# trig3_board_trigger_waveshare_lvds.net
KiCad netlist of a schematic drawn in EAGLE
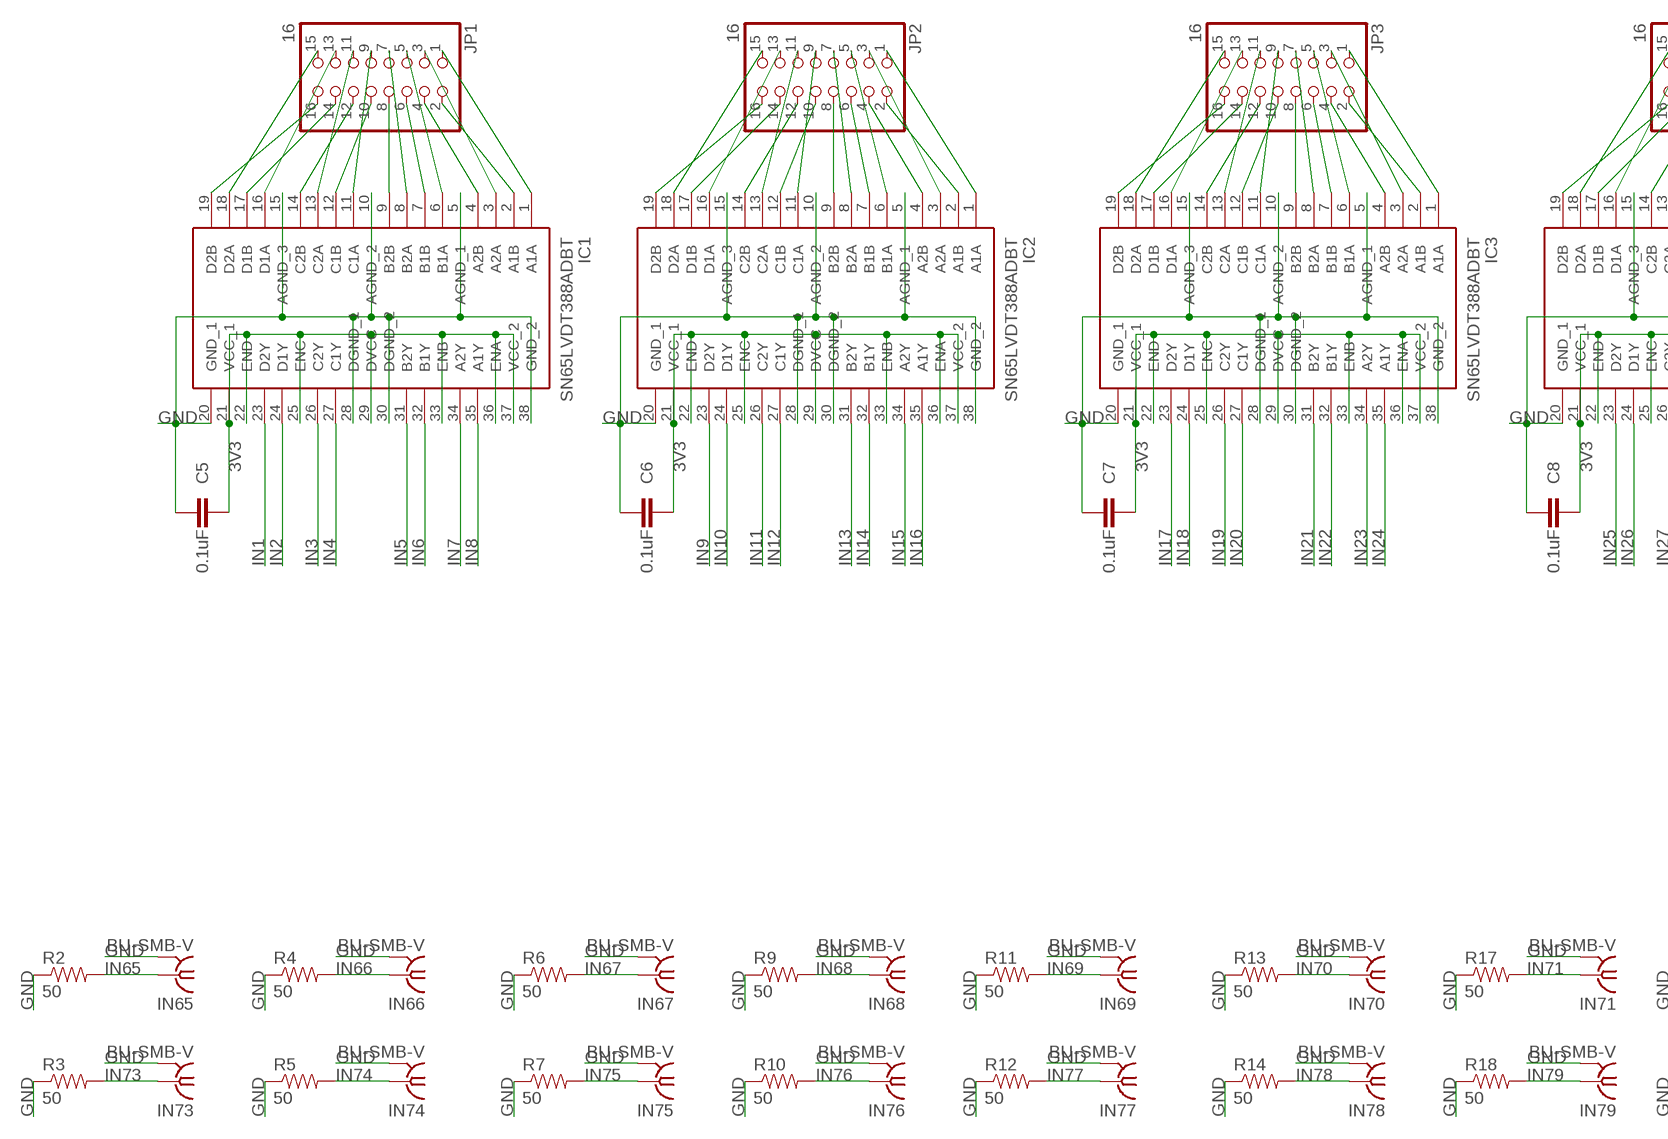
[diagram p0: schematic, sheet 1, part 1 of 3]
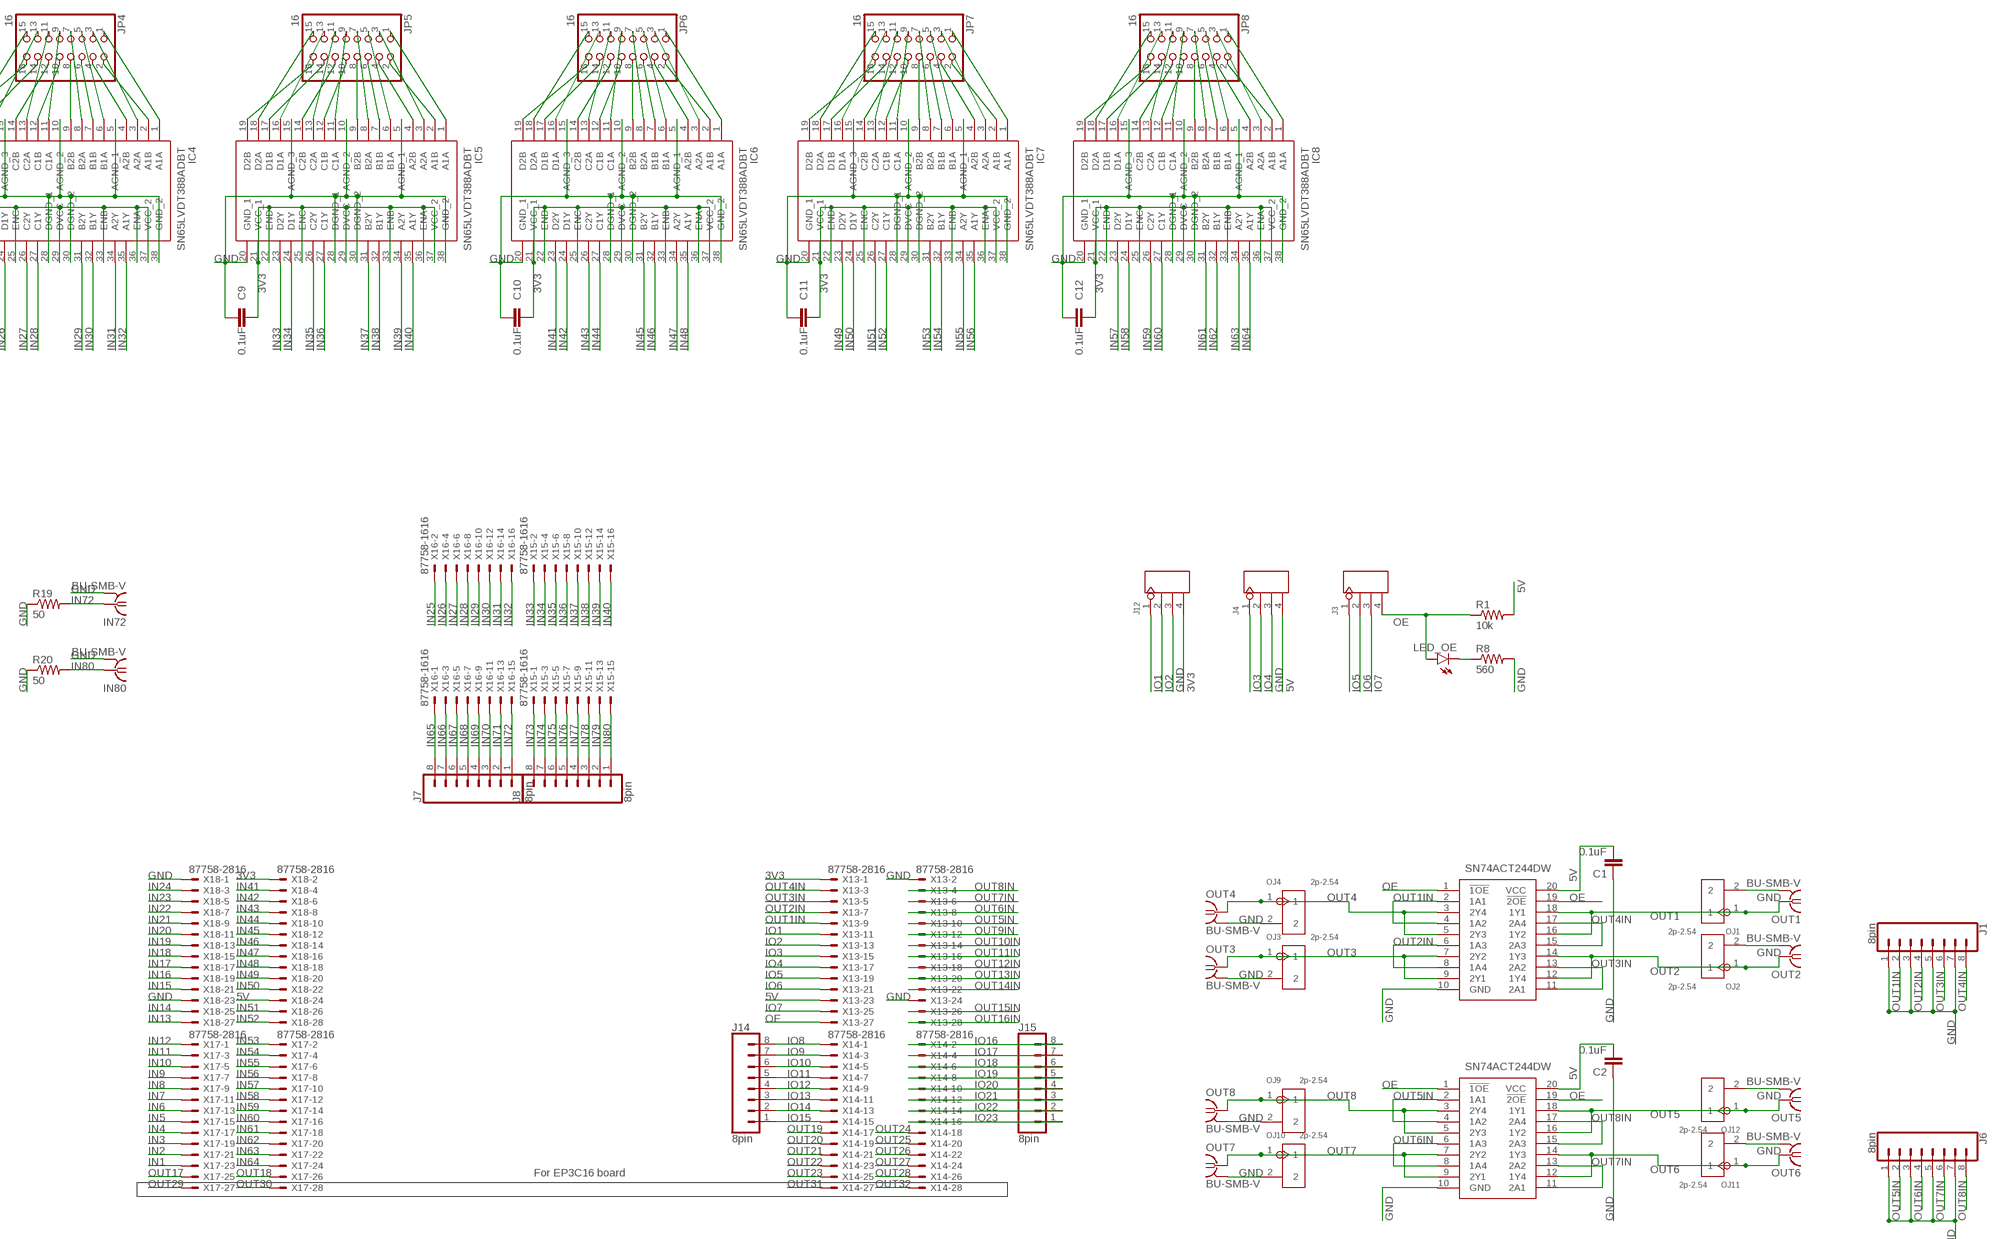
[diagram p1: schematic, sheet 1, part 2 of 3]
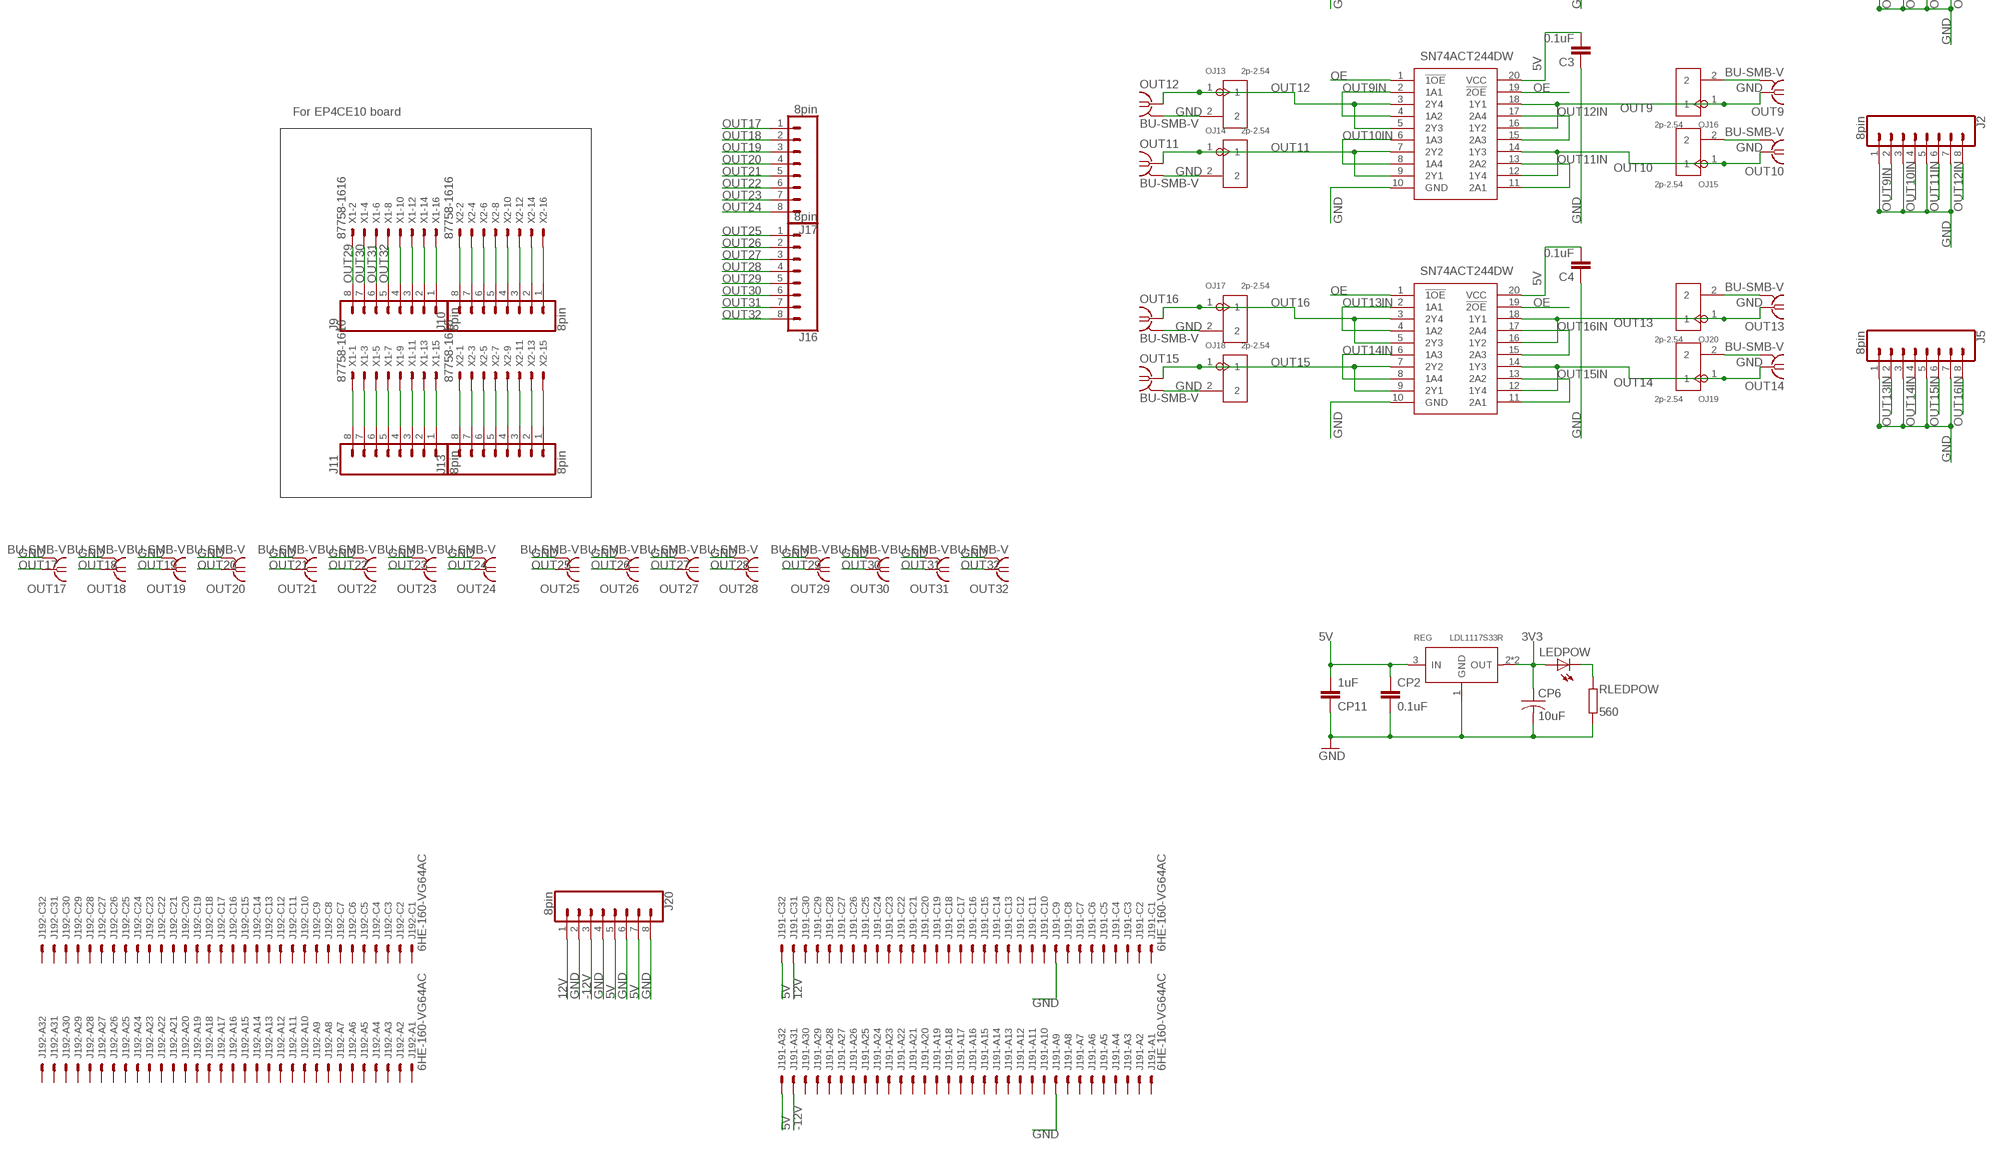
[diagram p2: schematic, sheet 1, part 3 of 3]

(export (version "E")
  (design (tool "Eeschema 10.0.6"))
  (components
    (comp (ref "C1")
      (value "0.1uF")
      (footprint "eagle-import:0805")
      (libsource (lib "eagle-import") (part "CAP0805"))
    )
    (comp (ref "C2")
      (value "0.1uF")
      (footprint "eagle-import:0805")
      (libsource (lib "eagle-import") (part "CAP0805"))
    )
    (comp (ref "C3")
      (value "0.1uF")
      (footprint "eagle-import:0805")
      (libsource (lib "eagle-import") (part "CAP0805"))
    )
    (comp (ref "C4")
      (value "0.1uF")
      (footprint "eagle-import:0805")
      (libsource (lib "eagle-import") (part "CAP0805"))
    )
    (comp (ref "C5")
      (value "0.1uF")
      (footprint "eagle-import:0805")
      (libsource (lib "eagle-import") (part "CAP0805"))
    )
    (comp (ref "C6")
      (value "0.1uF")
      (footprint "eagle-import:0805")
      (libsource (lib "eagle-import") (part "CAP0805"))
    )
    (comp (ref "C7")
      (value "0.1uF")
      (footprint "eagle-import:0805")
      (libsource (lib "eagle-import") (part "CAP0805"))
    )
    (comp (ref "C8")
      (value "0.1uF")
      (footprint "eagle-import:0805")
      (libsource (lib "eagle-import") (part "CAP0805"))
    )
    (comp (ref "C9")
      (value "0.1uF")
      (footprint "eagle-import:0805")
      (libsource (lib "eagle-import") (part "CAP0805"))
    )
    (comp (ref "C10")
      (value "0.1uF")
      (footprint "eagle-import:0805")
      (libsource (lib "eagle-import") (part "CAP0805"))
    )
    (comp (ref "C11")
      (value "0.1uF")
      (footprint "eagle-import:0805")
      (libsource (lib "eagle-import") (part "CAP0805"))
    )
    (comp (ref "C12")
      (value "0.1uF")
      (footprint "eagle-import:0805")
      (libsource (lib "eagle-import") (part "CAP0805"))
    )
    (comp (ref "CP2")
      (value "0.1uF")
      (footprint "eagle-import:C0805K")
      (fields (field (name "MPN") "MF-CAP-0805-0.1uF"))
      (libsource (lib "eagle-import") (part "C-EUC0805K"))
    )
    (comp (ref "CP6")
      (value "10uF")
      (footprint "eagle-import:C1206")
      (fields (field (name "MPN") "MF-CAP-1206-10uF"))
      (libsource (lib "eagle-import") (part "C-USC1206"))
    )
    (comp (ref "CP11")
      (value "1uF")
      (footprint "eagle-import:C0805K")
      (fields (field (name "MPN") "MF-CAP-0805-1uF"))
      (libsource (lib "eagle-import") (part "C-EUC0805K"))
    )
    (comp (ref "IC1")
      (value "SN65LVDT388ADBT")
      (footprint "eagle-import:SOP50P640X120-38N")
      (fields (field (name "MOUSER_PART_NUMBER") "595-SN65LVDT388ADBT"))
      (libsource (lib "eagle-import") (part "SN65LVDT388ADBT"))
    )
    (comp (ref "IC2")
      (value "SN65LVDT388ADBT")
      (footprint "eagle-import:SOP50P640X120-38N")
      (fields (field (name "MOUSER_PART_NUMBER") "595-SN65LVDT388ADBT"))
      (libsource (lib "eagle-import") (part "SN65LVDT388ADBT"))
    )
    (comp (ref "IC3")
      (value "SN65LVDT388ADBT")
      (footprint "eagle-import:SOP50P640X120-38N")
      (fields (field (name "MOUSER_PART_NUMBER") "595-SN65LVDT388ADBT"))
      (libsource (lib "eagle-import") (part "SN65LVDT388ADBT"))
    )
    (comp (ref "IC4")
      (value "SN65LVDT388ADBT")
      (footprint "eagle-import:SOP50P640X120-38N")
      (fields (field (name "MOUSER_PART_NUMBER") "595-SN65LVDT388ADBT"))
      (libsource (lib "eagle-import") (part "SN65LVDT388ADBT"))
    )
    (comp (ref "IC5")
      (value "SN65LVDT388ADBT")
      (footprint "eagle-import:SOP50P640X120-38N")
      (fields (field (name "MOUSER_PART_NUMBER") "595-SN65LVDT388ADBT"))
      (libsource (lib "eagle-import") (part "SN65LVDT388ADBT"))
    )
    (comp (ref "IC6")
      (value "SN65LVDT388ADBT")
      (footprint "eagle-import:SOP50P640X120-38N")
      (fields (field (name "MOUSER_PART_NUMBER") "595-SN65LVDT388ADBT"))
      (libsource (lib "eagle-import") (part "SN65LVDT388ADBT"))
    )
    (comp (ref "IC7")
      (value "SN65LVDT388ADBT")
      (footprint "eagle-import:SOP50P640X120-38N")
      (fields (field (name "MOUSER_PART_NUMBER") "595-SN65LVDT388ADBT"))
      (libsource (lib "eagle-import") (part "SN65LVDT388ADBT"))
    )
    (comp (ref "IC8")
      (value "SN65LVDT388ADBT")
      (footprint "eagle-import:SOP50P640X120-38N")
      (fields (field (name "MOUSER_PART_NUMBER") "595-SN65LVDT388ADBT"))
      (libsource (lib "eagle-import") (part "SN65LVDT388ADBT"))
    )
    (comp (ref "IN65")
      (value "BU-SMB-V")
      (footprint "eagle-import:BU-SMB-V")
      (libsource (lib "eagle-import") (part "BU-SMB-V"))
    )
    (comp (ref "IN66")
      (value "BU-SMB-V")
      (footprint "eagle-import:BU-SMB-V")
      (libsource (lib "eagle-import") (part "BU-SMB-V"))
    )
    (comp (ref "IN67")
      (value "BU-SMB-V")
      (footprint "eagle-import:BU-SMB-V")
      (libsource (lib "eagle-import") (part "BU-SMB-V"))
    )
    (comp (ref "IN68")
      (value "BU-SMB-V")
      (footprint "eagle-import:BU-SMB-V")
      (libsource (lib "eagle-import") (part "BU-SMB-V"))
    )
    (comp (ref "IN69")
      (value "BU-SMB-V")
      (footprint "eagle-import:BU-SMB-V")
      (libsource (lib "eagle-import") (part "BU-SMB-V"))
    )
    (comp (ref "IN70")
      (value "BU-SMB-V")
      (footprint "eagle-import:BU-SMB-V")
      (libsource (lib "eagle-import") (part "BU-SMB-V"))
    )
    (comp (ref "IN71")
      (value "BU-SMB-V")
      (footprint "eagle-import:BU-SMB-V")
      (libsource (lib "eagle-import") (part "BU-SMB-V"))
    )
    (comp (ref "IN72")
      (value "BU-SMB-V")
      (footprint "eagle-import:BU-SMB-V")
      (libsource (lib "eagle-import") (part "BU-SMB-V"))
    )
    (comp (ref "IN73")
      (value "BU-SMB-V")
      (footprint "eagle-import:BU-SMB-V")
      (libsource (lib "eagle-import") (part "BU-SMB-V"))
    )
    (comp (ref "IN74")
      (value "BU-SMB-V")
      (footprint "eagle-import:BU-SMB-V")
      (libsource (lib "eagle-import") (part "BU-SMB-V"))
    )
    (comp (ref "IN75")
      (value "BU-SMB-V")
      (footprint "eagle-import:BU-SMB-V")
      (libsource (lib "eagle-import") (part "BU-SMB-V"))
    )
    (comp (ref "IN76")
      (value "BU-SMB-V")
      (footprint "eagle-import:BU-SMB-V")
      (libsource (lib "eagle-import") (part "BU-SMB-V"))
    )
    (comp (ref "IN77")
      (value "BU-SMB-V")
      (footprint "eagle-import:BU-SMB-V")
      (libsource (lib "eagle-import") (part "BU-SMB-V"))
    )
    (comp (ref "IN78")
      (value "BU-SMB-V")
      (footprint "eagle-import:BU-SMB-V")
      (libsource (lib "eagle-import") (part "BU-SMB-V"))
    )
    (comp (ref "IN79")
      (value "BU-SMB-V")
      (footprint "eagle-import:BU-SMB-V")
      (libsource (lib "eagle-import") (part "BU-SMB-V"))
    )
    (comp (ref "IN80")
      (value "BU-SMB-V")
      (footprint "eagle-import:BU-SMB-V")
      (libsource (lib "eagle-import") (part "BU-SMB-V"))
    )
    (comp (ref "J1")
      (value "8pin")
      (footprint "eagle-import:1X08")
      (libsource (lib "eagle-import") (part "CONN_08{dblquote}"))
    )
    (comp (ref "J2")
      (value "8pin")
      (footprint "eagle-import:1X08")
      (libsource (lib "eagle-import") (part "CONN_08{dblquote}"))
    )
    (comp (ref "J3")
      (value "4p-2.54")
      (footprint "eagle-import:H4-2.54")
      (fields (field (name "MPN") "F185-1104A1BSYA1"))
      (libsource (lib "eagle-import") (part "DIP-BLACK-FEMALE-HEADER-VERT(4P-2.54)"))
    )
    (comp (ref "J4")
      (value "4p-2.54")
      (footprint "eagle-import:H4-2.54")
      (fields (field (name "MPN") "F185-1104A1BSYA1"))
      (libsource (lib "eagle-import") (part "DIP-BLACK-FEMALE-HEADER-VERT(4P-2.54)"))
    )
    (comp (ref "J5")
      (value "8pin")
      (footprint "eagle-import:1X08")
      (libsource (lib "eagle-import") (part "CONN_08{dblquote}"))
    )
    (comp (ref "J6")
      (value "8pin")
      (footprint "eagle-import:1X08")
      (libsource (lib "eagle-import") (part "CONN_08{dblquote}"))
    )
    (comp (ref "J7")
      (value "8pin")
      (footprint "eagle-import:1X08")
      (libsource (lib "eagle-import") (part "CONN_08{dblquote}"))
    )
    (comp (ref "J8")
      (value "8pin")
      (footprint "eagle-import:1X08")
      (libsource (lib "eagle-import") (part "CONN_08{dblquote}"))
    )
    (comp (ref "J9")
      (value "8pin")
      (footprint "eagle-import:1X08")
      (libsource (lib "eagle-import") (part "CONN_08{dblquote}"))
    )
    (comp (ref "J10")
      (value "8pin")
      (footprint "eagle-import:1X08")
      (libsource (lib "eagle-import") (part "CONN_08{dblquote}"))
    )
    (comp (ref "J11")
      (value "8pin")
      (footprint "eagle-import:1X08")
      (libsource (lib "eagle-import") (part "CONN_08{dblquote}"))
    )
    (comp (ref "J12")
      (value "4p-2.54")
      (footprint "eagle-import:H4-2.54")
      (fields (field (name "MPN") "F185-1104A1BSYA1"))
      (libsource (lib "eagle-import") (part "DIP-BLACK-FEMALE-HEADER-VERT(4P-2.54)"))
    )
    (comp (ref "J13")
      (value "8pin")
      (footprint "eagle-import:1X08")
      (libsource (lib "eagle-import") (part "CONN_08{dblquote}"))
    )
    (comp (ref "J14")
      (value "8pin")
      (footprint "eagle-import:1X08")
      (libsource (lib "eagle-import") (part "CONN_08{dblquote}"))
    )
    (comp (ref "J15")
      (value "8pin")
      (footprint "eagle-import:1X08")
      (libsource (lib "eagle-import") (part "CONN_08{dblquote}"))
    )
    (comp (ref "J16")
      (value "8pin")
      (footprint "eagle-import:1X08")
      (libsource (lib "eagle-import") (part "CONN_08{dblquote}"))
    )
    (comp (ref "J17")
      (value "8pin")
      (footprint "eagle-import:1X08")
      (libsource (lib "eagle-import") (part "CONN_08{dblquote}"))
    )
    (comp (ref "J19")
      (value "6HE-160-VG64AC")
      (footprint "eagle-import:6HE_160-VG64AC")
      (libsource (lib "eagle-import") (part "6HE-?-VG64AC160"))
    )
    (comp (ref "J20")
      (value "8pin")
      (footprint "eagle-import:1X08")
      (libsource (lib "eagle-import") (part "CONN_08{dblquote}"))
    )
    (comp (ref "JP1")
      (value "16")
      (footprint "eagle-import:2X08_90")
      (libsource (lib "eagle-import") (part "PINHD-2X8/90"))
    )
    (comp (ref "JP2")
      (value "16")
      (footprint "eagle-import:2X08_90")
      (libsource (lib "eagle-import") (part "PINHD-2X8/90"))
    )
    (comp (ref "JP3")
      (value "16")
      (footprint "eagle-import:2X08_90")
      (libsource (lib "eagle-import") (part "PINHD-2X8/90"))
    )
    (comp (ref "JP4")
      (value "16")
      (footprint "eagle-import:2X08_90")
      (libsource (lib "eagle-import") (part "PINHD-2X8/90"))
    )
    (comp (ref "JP5")
      (value "16")
      (footprint "eagle-import:2X08_90")
      (libsource (lib "eagle-import") (part "PINHD-2X8/90"))
    )
    (comp (ref "JP6")
      (value "16")
      (footprint "eagle-import:2X08_90")
      (libsource (lib "eagle-import") (part "PINHD-2X8/90"))
    )
    (comp (ref "JP7")
      (value "16")
      (footprint "eagle-import:2X08_90")
      (libsource (lib "eagle-import") (part "PINHD-2X8/90"))
    )
    (comp (ref "JP8")
      (value "16")
      (footprint "eagle-import:2X08_90")
      (libsource (lib "eagle-import") (part "PINHD-2X8/90"))
    )
    (comp (ref "LEDPOW")
      (value "MF-LED-0805-RED")
      (footprint "eagle-import:SML0805")
      (libsource (lib "eagle-import") (part "LEDSML0805"))
    )
    (comp (ref "LED_OE")
      (value "OutputEn")
      (footprint "eagle-import:CHIP-LED0805")
      (libsource (lib "eagle-import") (part "led_259_LEDCHIP-LED0805"))
    )
    (comp (ref "OJ1")
      (value "2p-2.54")
      (footprint "eagle-import:H2-2.54")
      (fields (field (name "MPN") "P125-1102A0BS116A1"))
      (libsource (lib "eagle-import") (part "DIP-BLACK-MALE-HEADER-VERT(2P-2.54)"))
    )
    (comp (ref "OJ2")
      (value "2p-2.54")
      (footprint "eagle-import:H2-2.54")
      (fields (field (name "MPN") "P125-1102A0BS116A1"))
      (libsource (lib "eagle-import") (part "DIP-BLACK-MALE-HEADER-VERT(2P-2.54)"))
    )
    (comp (ref "OJ3")
      (value "2p-2.54")
      (footprint "eagle-import:H2-2.54")
      (fields (field (name "MPN") "P125-1102A0BS116A1"))
      (libsource (lib "eagle-import") (part "DIP-BLACK-MALE-HEADER-VERT(2P-2.54)"))
    )
    (comp (ref "OJ4")
      (value "2p-2.54")
      (footprint "eagle-import:H2-2.54")
      (fields (field (name "MPN") "P125-1102A0BS116A1"))
      (libsource (lib "eagle-import") (part "DIP-BLACK-MALE-HEADER-VERT(2P-2.54)"))
    )
    (comp (ref "OJ9")
      (value "2p-2.54")
      (footprint "eagle-import:H2-2.54")
      (fields (field (name "MPN") "P125-1102A0BS116A1"))
      (libsource (lib "eagle-import") (part "DIP-BLACK-MALE-HEADER-VERT(2P-2.54)"))
    )
    (comp (ref "OJ10")
      (value "2p-2.54")
      (footprint "eagle-import:H2-2.54")
      (fields (field (name "MPN") "P125-1102A0BS116A1"))
      (libsource (lib "eagle-import") (part "DIP-BLACK-MALE-HEADER-VERT(2P-2.54)"))
    )
    (comp (ref "OJ11")
      (value "2p-2.54")
      (footprint "eagle-import:H2-2.54")
      (fields (field (name "MPN") "P125-1102A0BS116A1"))
      (libsource (lib "eagle-import") (part "DIP-BLACK-MALE-HEADER-VERT(2P-2.54)"))
    )
    (comp (ref "OJ12")
      (value "2p-2.54")
      (footprint "eagle-import:H2-2.54")
      (fields (field (name "MPN") "P125-1102A0BS116A1"))
      (libsource (lib "eagle-import") (part "DIP-BLACK-MALE-HEADER-VERT(2P-2.54)"))
    )
    (comp (ref "OJ13")
      (value "2p-2.54")
      (footprint "eagle-import:H2-2.54")
      (fields (field (name "MPN") "P125-1102A0BS116A1"))
      (libsource (lib "eagle-import") (part "DIP-BLACK-MALE-HEADER-VERT(2P-2.54)"))
    )
    (comp (ref "OJ14")
      (value "2p-2.54")
      (footprint "eagle-import:H2-2.54")
      (fields (field (name "MPN") "P125-1102A0BS116A1"))
      (libsource (lib "eagle-import") (part "DIP-BLACK-MALE-HEADER-VERT(2P-2.54)"))
    )
    (comp (ref "OJ15")
      (value "2p-2.54")
      (footprint "eagle-import:H2-2.54")
      (fields (field (name "MPN") "P125-1102A0BS116A1"))
      (libsource (lib "eagle-import") (part "DIP-BLACK-MALE-HEADER-VERT(2P-2.54)"))
    )
    (comp (ref "OJ16")
      (value "2p-2.54")
      (footprint "eagle-import:H2-2.54")
      (fields (field (name "MPN") "P125-1102A0BS116A1"))
      (libsource (lib "eagle-import") (part "DIP-BLACK-MALE-HEADER-VERT(2P-2.54)"))
    )
    (comp (ref "OJ17")
      (value "2p-2.54")
      (footprint "eagle-import:H2-2.54")
      (fields (field (name "MPN") "P125-1102A0BS116A1"))
      (libsource (lib "eagle-import") (part "DIP-BLACK-MALE-HEADER-VERT(2P-2.54)"))
    )
    (comp (ref "OJ18")
      (value "2p-2.54")
      (footprint "eagle-import:H2-2.54")
      (fields (field (name "MPN") "P125-1102A0BS116A1"))
      (libsource (lib "eagle-import") (part "DIP-BLACK-MALE-HEADER-VERT(2P-2.54)"))
    )
    (comp (ref "OJ19")
      (value "2p-2.54")
      (footprint "eagle-import:H2-2.54")
      (fields (field (name "MPN") "P125-1102A0BS116A1"))
      (libsource (lib "eagle-import") (part "DIP-BLACK-MALE-HEADER-VERT(2P-2.54)"))
    )
    (comp (ref "OJ20")
      (value "2p-2.54")
      (footprint "eagle-import:H2-2.54")
      (fields (field (name "MPN") "P125-1102A0BS116A1"))
      (libsource (lib "eagle-import") (part "DIP-BLACK-MALE-HEADER-VERT(2P-2.54)"))
    )
    (comp (ref "OUT1")
      (value "BU-SMB-V")
      (footprint "eagle-import:BU-SMB-V")
      (libsource (lib "eagle-import") (part "BU-SMB-V"))
    )
    (comp (ref "OUT2")
      (value "BU-SMB-V")
      (footprint "eagle-import:BU-SMB-V")
      (libsource (lib "eagle-import") (part "BU-SMB-V"))
    )
    (comp (ref "OUT3")
      (value "BU-SMB-V")
      (footprint "eagle-import:BU-SMB-V")
      (libsource (lib "eagle-import") (part "BU-SMB-V"))
    )
    (comp (ref "OUT4")
      (value "BU-SMB-V")
      (footprint "eagle-import:BU-SMB-V")
      (libsource (lib "eagle-import") (part "BU-SMB-V"))
    )
    (comp (ref "OUT5")
      (value "BU-SMB-V")
      (footprint "eagle-import:BU-SMB-V")
      (libsource (lib "eagle-import") (part "BU-SMB-V"))
    )
    (comp (ref "OUT6")
      (value "BU-SMB-V")
      (footprint "eagle-import:BU-SMB-V")
      (libsource (lib "eagle-import") (part "BU-SMB-V"))
    )
    (comp (ref "OUT7")
      (value "BU-SMB-V")
      (footprint "eagle-import:BU-SMB-V")
      (libsource (lib "eagle-import") (part "BU-SMB-V"))
    )
    (comp (ref "OUT8")
      (value "BU-SMB-V")
      (footprint "eagle-import:BU-SMB-V")
      (libsource (lib "eagle-import") (part "BU-SMB-V"))
    )
    (comp (ref "OUT9")
      (value "BU-SMB-V")
      (footprint "eagle-import:BU-SMB-V")
      (libsource (lib "eagle-import") (part "BU-SMB-V"))
    )
    (comp (ref "OUT10")
      (value "BU-SMB-V")
      (footprint "eagle-import:BU-SMB-V")
      (libsource (lib "eagle-import") (part "BU-SMB-V"))
    )
    (comp (ref "OUT11")
      (value "BU-SMB-V")
      (footprint "eagle-import:BU-SMB-V")
      (libsource (lib "eagle-import") (part "BU-SMB-V"))
    )
    (comp (ref "OUT12")
      (value "BU-SMB-V")
      (footprint "eagle-import:BU-SMB-V")
      (libsource (lib "eagle-import") (part "BU-SMB-V"))
    )
    (comp (ref "OUT13")
      (value "BU-SMB-V")
      (footprint "eagle-import:BU-SMB-V")
      (libsource (lib "eagle-import") (part "BU-SMB-V"))
    )
    (comp (ref "OUT14")
      (value "BU-SMB-V")
      (footprint "eagle-import:BU-SMB-V")
      (libsource (lib "eagle-import") (part "BU-SMB-V"))
    )
    (comp (ref "OUT15")
      (value "BU-SMB-V")
      (footprint "eagle-import:BU-SMB-V")
      (libsource (lib "eagle-import") (part "BU-SMB-V"))
    )
    (comp (ref "OUT16")
      (value "BU-SMB-V")
      (footprint "eagle-import:BU-SMB-V")
      (libsource (lib "eagle-import") (part "BU-SMB-V"))
    )
    (comp (ref "OUT17")
      (value "BU-SMB-V")
      (footprint "eagle-import:BU-SMB-V")
      (libsource (lib "eagle-import") (part "BU-SMB-V"))
    )
    (comp (ref "OUT18")
      (value "BU-SMB-V")
      (footprint "eagle-import:BU-SMB-V")
      (libsource (lib "eagle-import") (part "BU-SMB-V"))
    )
    (comp (ref "OUT19")
      (value "BU-SMB-V")
      (footprint "eagle-import:BU-SMB-V")
      (libsource (lib "eagle-import") (part "BU-SMB-V"))
    )
    (comp (ref "OUT20")
      (value "BU-SMB-V")
      (footprint "eagle-import:BU-SMB-V")
      (libsource (lib "eagle-import") (part "BU-SMB-V"))
    )
    (comp (ref "OUT21")
      (value "BU-SMB-V")
      (footprint "eagle-import:BU-SMB-V")
      (libsource (lib "eagle-import") (part "BU-SMB-V"))
    )
    (comp (ref "OUT22")
      (value "BU-SMB-V")
      (footprint "eagle-import:BU-SMB-V")
      (libsource (lib "eagle-import") (part "BU-SMB-V"))
    )
    (comp (ref "OUT23")
      (value "BU-SMB-V")
      (footprint "eagle-import:BU-SMB-V")
      (libsource (lib "eagle-import") (part "BU-SMB-V"))
    )
    (comp (ref "OUT24")
      (value "BU-SMB-V")
      (footprint "eagle-import:BU-SMB-V")
      (libsource (lib "eagle-import") (part "BU-SMB-V"))
    )
    (comp (ref "OUT25")
      (value "BU-SMB-V")
      (footprint "eagle-import:BU-SMB-V")
      (libsource (lib "eagle-import") (part "BU-SMB-V"))
    )
    (comp (ref "OUT26")
      (value "BU-SMB-V")
      (footprint "eagle-import:BU-SMB-V")
      (libsource (lib "eagle-import") (part "BU-SMB-V"))
    )
    (comp (ref "OUT27")
      (value "BU-SMB-V")
      (footprint "eagle-import:BU-SMB-V")
      (libsource (lib "eagle-import") (part "BU-SMB-V"))
    )
    (comp (ref "OUT28")
      (value "BU-SMB-V")
      (footprint "eagle-import:BU-SMB-V")
      (libsource (lib "eagle-import") (part "BU-SMB-V"))
    )
    (comp (ref "OUT29")
      (value "BU-SMB-V")
      (footprint "eagle-import:BU-SMB-V")
      (libsource (lib "eagle-import") (part "BU-SMB-V"))
    )
    (comp (ref "OUT30")
      (value "BU-SMB-V")
      (footprint "eagle-import:BU-SMB-V")
      (libsource (lib "eagle-import") (part "BU-SMB-V"))
    )
    (comp (ref "OUT31")
      (value "BU-SMB-V")
      (footprint "eagle-import:BU-SMB-V")
      (libsource (lib "eagle-import") (part "BU-SMB-V"))
    )
    (comp (ref "OUT32")
      (value "BU-SMB-V")
      (footprint "eagle-import:BU-SMB-V")
      (libsource (lib "eagle-import") (part "BU-SMB-V"))
    )
    (comp (ref "R1")
      (value "10k")
      (footprint "eagle-import:R0805")
      (libsource (lib "eagle-import") (part "R-US_R0805"))
    )
    (comp (ref "R2")
      (value "50")
      (footprint "eagle-import:AXIAL-0.3")
      (libsource (lib "eagle-import") (part "RESISTORAXIAL-0.3"))
    )
    (comp (ref "R3")
      (value "50")
      (footprint "eagle-import:AXIAL-0.3")
      (libsource (lib "eagle-import") (part "RESISTORAXIAL-0.3"))
    )
    (comp (ref "R4")
      (value "50")
      (footprint "eagle-import:AXIAL-0.3")
      (libsource (lib "eagle-import") (part "RESISTORAXIAL-0.3"))
    )
    (comp (ref "R5")
      (value "50")
      (footprint "eagle-import:AXIAL-0.3")
      (libsource (lib "eagle-import") (part "RESISTORAXIAL-0.3"))
    )
    (comp (ref "R6")
      (value "50")
      (footprint "eagle-import:AXIAL-0.3")
      (libsource (lib "eagle-import") (part "RESISTORAXIAL-0.3"))
    )
    (comp (ref "R7")
      (value "50")
      (footprint "eagle-import:AXIAL-0.3")
      (libsource (lib "eagle-import") (part "RESISTORAXIAL-0.3"))
    )
    (comp (ref "R8")
      (value "560")
      (footprint "eagle-import:R0805")
      (libsource (lib "eagle-import") (part "R-US_R0805"))
    )
    (comp (ref "R9")
      (value "50")
      (footprint "eagle-import:AXIAL-0.3")
      (libsource (lib "eagle-import") (part "RESISTORAXIAL-0.3"))
    )
    (comp (ref "R10")
      (value "50")
      (footprint "eagle-import:AXIAL-0.3")
      (libsource (lib "eagle-import") (part "RESISTORAXIAL-0.3"))
    )
    (comp (ref "R11")
      (value "50")
      (footprint "eagle-import:AXIAL-0.3")
      (libsource (lib "eagle-import") (part "RESISTORAXIAL-0.3"))
    )
    (comp (ref "R12")
      (value "50")
      (footprint "eagle-import:AXIAL-0.3")
      (libsource (lib "eagle-import") (part "RESISTORAXIAL-0.3"))
    )
    (comp (ref "R13")
      (value "50")
      (footprint "eagle-import:AXIAL-0.3")
      (libsource (lib "eagle-import") (part "RESISTORAXIAL-0.3"))
    )
    (comp (ref "R14")
      (value "50")
      (footprint "eagle-import:AXIAL-0.3")
      (libsource (lib "eagle-import") (part "RESISTORAXIAL-0.3"))
    )
    (comp (ref "R17")
      (value "50")
      (footprint "eagle-import:AXIAL-0.3")
      (libsource (lib "eagle-import") (part "RESISTORAXIAL-0.3"))
    )
    (comp (ref "R18")
      (value "50")
      (footprint "eagle-import:AXIAL-0.3")
      (libsource (lib "eagle-import") (part "RESISTORAXIAL-0.3"))
    )
    (comp (ref "R19")
      (value "50")
      (footprint "eagle-import:AXIAL-0.3")
      (libsource (lib "eagle-import") (part "RESISTORAXIAL-0.3"))
    )
    (comp (ref "R20")
      (value "50")
      (footprint "eagle-import:AXIAL-0.3")
      (libsource (lib "eagle-import") (part "RESISTORAXIAL-0.3"))
    )
    (comp (ref "REG")
      (value "LDL1117S33R")
      (footprint "eagle-import:SOT-223")
      (fields (field (name "MPN") "CJT1117-3.3") (field (name "MPN_1") "LDL1117S33R"))
      (libsource (lib "eagle-import") (part "PMIC-CJT1117-3.3(SOT223)"))
    )
    (comp (ref "RLEDPOW")
      (value "560")
      (footprint "eagle-import:R0805")
      (fields (field (name "MPN") "MF-RES-0805-560"))
      (libsource (lib "eagle-import") (part "R-EU_R0805"))
    )
    (comp (ref "VSLUE")
      (value "SN74ACT244DW")
      (footprint "eagle-import:SOIC127P1030X265-20N")
      (fields (field (name "RS_PART_NUMBER") "4363169"))
      (libsource (lib "eagle-import") (part "SN74ACT244DW"))
    )
    (comp (ref "VSLUE2")
      (value "SN74ACT244DW")
      (footprint "eagle-import:SOIC127P1030X265-20N")
      (fields (field (name "RS_PART_NUMBER") "4363169"))
      (libsource (lib "eagle-import") (part "SN74ACT244DW"))
    )
    (comp (ref "VSLUE3")
      (value "SN74ACT244DW")
      (footprint "eagle-import:SOIC127P1030X265-20N")
      (fields (field (name "RS_PART_NUMBER") "4363169"))
      (libsource (lib "eagle-import") (part "SN74ACT244DW"))
    )
    (comp (ref "VSLUE4")
      (value "SN74ACT244DW")
      (footprint "eagle-import:SOIC127P1030X265-20N")
      (fields (field (name "RS_PART_NUMBER") "4363169"))
      (libsource (lib "eagle-import") (part "SN74ACT244DW"))
    )
    (comp (ref "X1")
      (value "87758-1616")
      (footprint "eagle-import:87758-1616")
      (fields (field (name "MF") "MOLEX"))
      (libsource (lib "eagle-import") (part "87758-1616"))
    )
    (comp (ref "X2")
      (value "87758-1616")
      (footprint "eagle-import:87758-1616")
      (fields (field (name "MF") "MOLEX"))
      (libsource (lib "eagle-import") (part "87758-1616"))
    )
    (comp (ref "X13")
      (value "87758-2816")
      (footprint "eagle-import:87758-2816")
      (fields (field (name "MF") "MOLEX"))
      (libsource (lib "eagle-import") (part "87758-2816"))
    )
    (comp (ref "X14")
      (value "87758-2816")
      (footprint "eagle-import:87758-2816")
      (fields (field (name "MF") "MOLEX"))
      (libsource (lib "eagle-import") (part "87758-2816"))
    )
    (comp (ref "X15")
      (value "87758-1616")
      (footprint "eagle-import:87758-1616")
      (fields (field (name "MF") "MOLEX"))
      (libsource (lib "eagle-import") (part "87758-1616"))
    )
    (comp (ref "X16")
      (value "87758-1616")
      (footprint "eagle-import:87758-1616")
      (fields (field (name "MF") "MOLEX"))
      (libsource (lib "eagle-import") (part "87758-1616"))
    )
    (comp (ref "X17")
      (value "87758-2816")
      (footprint "eagle-import:87758-2816")
      (fields (field (name "MF") "MOLEX"))
      (libsource (lib "eagle-import") (part "87758-2816"))
    )
    (comp (ref "X18")
      (value "87758-2816")
      (footprint "eagle-import:87758-2816")
      (fields (field (name "MF") "MOLEX"))
      (libsource (lib "eagle-import") (part "87758-2816"))
    )
  )
  (nets
    (net (code "1") (name "/-12V") (class "Default")
      (node (ref "J19") (pin "1-A31") (pinfunction "MS_1-A31") (pintype "passive"))
      (node (ref "J20") (pin "3") (pinfunction "3_3") (pintype "passive"))
    )
    (net (code "2") (name "/3V3") (class "Default")
      (node (ref "C10") (pin "2") (pinfunction "2_2") (pintype "passive"))
      (node (ref "C11") (pin "2") (pinfunction "2_2") (pintype "passive"))
      (node (ref "C12") (pin "2") (pinfunction "2_2") (pintype "passive"))
      (node (ref "C5") (pin "2") (pinfunction "2_2") (pintype "passive"))
      (node (ref "C6") (pin "2") (pinfunction "2_2") (pintype "passive"))
      (node (ref "C7") (pin "2") (pinfunction "2_2") (pintype "passive"))
      (node (ref "C8") (pin "2") (pinfunction "2_2") (pintype "passive"))
      (node (ref "C9") (pin "2") (pinfunction "2_2") (pintype "passive"))
      (node (ref "CP6") (pin "1") (pinfunction "1_1") (pintype "passive"))
      (node (ref "IC1") (pin "21") (pinfunction "VCC_1_21") (pintype "bidirectional"))
      (node (ref "IC1") (pin "22") (pinfunction "END_22") (pintype "bidirectional"))
      (node (ref "IC1") (pin "25") (pinfunction "ENC_25") (pintype "bidirectional"))
      (node (ref "IC1") (pin "29") (pinfunction "DVCC_29") (pintype "bidirectional"))
      (node (ref "IC1") (pin "33") (pinfunction "ENB_33") (pintype "bidirectional"))
      (node (ref "IC1") (pin "36") (pinfunction "ENA_36") (pintype "bidirectional"))
      (node (ref "IC1") (pin "37") (pinfunction "VCC_2_37") (pintype "bidirectional"))
      (node (ref "IC2") (pin "21") (pinfunction "VCC_1_21") (pintype "bidirectional"))
      (node (ref "IC2") (pin "22") (pinfunction "END_22") (pintype "bidirectional"))
      (node (ref "IC2") (pin "25") (pinfunction "ENC_25") (pintype "bidirectional"))
      (node (ref "IC2") (pin "29") (pinfunction "DVCC_29") (pintype "bidirectional"))
      (node (ref "IC2") (pin "33") (pinfunction "ENB_33") (pintype "bidirectional"))
      (node (ref "IC2") (pin "36") (pinfunction "ENA_36") (pintype "bidirectional"))
      (node (ref "IC2") (pin "37") (pinfunction "VCC_2_37") (pintype "bidirectional"))
      (node (ref "IC3") (pin "21") (pinfunction "VCC_1_21") (pintype "bidirectional"))
      (node (ref "IC3") (pin "22") (pinfunction "END_22") (pintype "bidirectional"))
      (node (ref "IC3") (pin "25") (pinfunction "ENC_25") (pintype "bidirectional"))
      (node (ref "IC3") (pin "29") (pinfunction "DVCC_29") (pintype "bidirectional"))
      (node (ref "IC3") (pin "33") (pinfunction "ENB_33") (pintype "bidirectional"))
      (node (ref "IC3") (pin "36") (pinfunction "ENA_36") (pintype "bidirectional"))
      (node (ref "IC3") (pin "37") (pinfunction "VCC_2_37") (pintype "bidirectional"))
      (node (ref "IC4") (pin "21") (pinfunction "VCC_1_21") (pintype "bidirectional"))
      (node (ref "IC4") (pin "22") (pinfunction "END_22") (pintype "bidirectional"))
      (node (ref "IC4") (pin "25") (pinfunction "ENC_25") (pintype "bidirectional"))
      (node (ref "IC4") (pin "29") (pinfunction "DVCC_29") (pintype "bidirectional"))
      (node (ref "IC4") (pin "33") (pinfunction "ENB_33") (pintype "bidirectional"))
      (node (ref "IC4") (pin "36") (pinfunction "ENA_36") (pintype "bidirectional"))
      (node (ref "IC4") (pin "37") (pinfunction "VCC_2_37") (pintype "bidirectional"))
      (node (ref "IC5") (pin "21") (pinfunction "VCC_1_21") (pintype "bidirectional"))
      (node (ref "IC5") (pin "22") (pinfunction "END_22") (pintype "bidirectional"))
      (node (ref "IC5") (pin "25") (pinfunction "ENC_25") (pintype "bidirectional"))
      (node (ref "IC5") (pin "29") (pinfunction "DVCC_29") (pintype "bidirectional"))
      (node (ref "IC5") (pin "33") (pinfunction "ENB_33") (pintype "bidirectional"))
      (node (ref "IC5") (pin "36") (pinfunction "ENA_36") (pintype "bidirectional"))
      (node (ref "IC5") (pin "37") (pinfunction "VCC_2_37") (pintype "bidirectional"))
      (node (ref "IC6") (pin "21") (pinfunction "VCC_1_21") (pintype "bidirectional"))
      (node (ref "IC6") (pin "22") (pinfunction "END_22") (pintype "bidirectional"))
      (node (ref "IC6") (pin "25") (pinfunction "ENC_25") (pintype "bidirectional"))
      (node (ref "IC6") (pin "29") (pinfunction "DVCC_29") (pintype "bidirectional"))
      (node (ref "IC6") (pin "33") (pinfunction "ENB_33") (pintype "bidirectional"))
      (node (ref "IC6") (pin "36") (pinfunction "ENA_36") (pintype "bidirectional"))
      (node (ref "IC6") (pin "37") (pinfunction "VCC_2_37") (pintype "bidirectional"))
      (node (ref "IC7") (pin "21") (pinfunction "VCC_1_21") (pintype "bidirectional"))
      (node (ref "IC7") (pin "22") (pinfunction "END_22") (pintype "bidirectional"))
      (node (ref "IC7") (pin "25") (pinfunction "ENC_25") (pintype "bidirectional"))
      (node (ref "IC7") (pin "29") (pinfunction "DVCC_29") (pintype "bidirectional"))
      (node (ref "IC7") (pin "33") (pinfunction "ENB_33") (pintype "bidirectional"))
      (node (ref "IC7") (pin "36") (pinfunction "ENA_36") (pintype "bidirectional"))
      (node (ref "IC7") (pin "37") (pinfunction "VCC_2_37") (pintype "bidirectional"))
      (node (ref "IC8") (pin "21") (pinfunction "VCC_1_21") (pintype "bidirectional"))
      (node (ref "IC8") (pin "22") (pinfunction "END_22") (pintype "bidirectional"))
      (node (ref "IC8") (pin "25") (pinfunction "ENC_25") (pintype "bidirectional"))
      (node (ref "IC8") (pin "29") (pinfunction "DVCC_29") (pintype "bidirectional"))
      (node (ref "IC8") (pin "33") (pinfunction "ENB_33") (pintype "bidirectional"))
      (node (ref "IC8") (pin "36") (pinfunction "ENA_36") (pintype "bidirectional"))
      (node (ref "IC8") (pin "37") (pinfunction "VCC_2_37") (pintype "bidirectional"))
      (node (ref "J12") (pin "4") (pinfunction "P$4_4") (pintype "bidirectional"))
      (node (ref "LEDPOW") (pin "A") (pinfunction "A_A") (pintype "passive"))
      (node (ref "REG") (pin "2") (pinfunction "OUT_2") (pintype "bidirectional"))
      (node (ref "REG") (pin "TER") (pinfunction "OUT_TER") (pintype "bidirectional"))
      (node (ref "X13") (pin "1") (pinfunction "S_1") (pintype "passive"))
      (node (ref "X18") (pin "2") (pinfunction "S_2") (pintype "passive"))
    )
    (net (code "3") (name "/5V") (class "Default")
      (node (ref "C1") (pin "2") (pinfunction "2_2") (pintype "passive"))
      (node (ref "C2") (pin "2") (pinfunction "2_2") (pintype "passive"))
      (node (ref "C3") (pin "2") (pinfunction "2_2") (pintype "passive"))
      (node (ref "C4") (pin "2") (pinfunction "2_2") (pintype "passive"))
      (node (ref "CP11") (pin "2") (pinfunction "2_2") (pintype "passive"))
      (node (ref "CP2") (pin "1") (pinfunction "1_1") (pintype "passive"))
      (node (ref "J19") (pin "1-A32") (pinfunction "MS_1-A32") (pintype "passive"))
      (node (ref "J19") (pin "1-C32") (pinfunction "MS_1-C32") (pintype "passive"))
      (node (ref "J20") (pin "5") (pinfunction "5_5") (pintype "passive"))
      (node (ref "J20") (pin "7") (pinfunction "7_7") (pintype "passive"))
      (node (ref "J4") (pin "4") (pinfunction "P$4_4") (pintype "bidirectional"))
      (node (ref "R1") (pin "2") (pinfunction "2_2") (pintype "passive"))
      (node (ref "REG") (pin "3") (pinfunction "IN_3") (pintype "bidirectional"))
      (node (ref "VSLUE") (pin "20") (pinfunction "VCC_20") (pintype "power_in"))
      (node (ref "VSLUE2") (pin "20") (pinfunction "VCC_20") (pintype "power_in"))
      (node (ref "VSLUE3") (pin "20") (pinfunction "VCC_20") (pintype "power_in"))
      (node (ref "VSLUE4") (pin "20") (pinfunction "VCC_20") (pintype "power_in"))
      (node (ref "X13") (pin "23") (pinfunction "S_23") (pintype "passive"))
      (node (ref "X18") (pin "24") (pinfunction "S_24") (pintype "passive"))
    )
    (net (code "4") (name "/12V") (class "Default")
      (node (ref "J19") (pin "1-C31") (pinfunction "MS_1-C31") (pintype "passive"))
      (node (ref "J20") (pin "1") (pinfunction "1_1") (pintype "passive"))
    )
    (net (code "5") (name "/IN1") (class "Default")
      (node (ref "IC1") (pin "23") (pinfunction "D2Y_23") (pintype "bidirectional"))
      (node (ref "X17") (pin "23") (pinfunction "S_23") (pintype "passive"))
    )
    (net (code "6") (name "/IN2") (class "Default")
      (node (ref "IC1") (pin "24") (pinfunction "D1Y_24") (pintype "bidirectional"))
      (node (ref "X17") (pin "21") (pinfunction "S_21") (pintype "passive"))
    )
    (net (code "7") (name "/IN3") (class "Default")
      (node (ref "IC1") (pin "26") (pinfunction "C2Y_26") (pintype "bidirectional"))
      (node (ref "X17") (pin "19") (pinfunction "S_19") (pintype "passive"))
    )
    (net (code "8") (name "/IN4") (class "Default")
      (node (ref "IC1") (pin "27") (pinfunction "C1Y_27") (pintype "bidirectional"))
      (node (ref "X17") (pin "17") (pinfunction "S_17") (pintype "passive"))
    )
    (net (code "9") (name "/IN5") (class "Default")
      (node (ref "IC1") (pin "31") (pinfunction "B2Y_31") (pintype "bidirectional"))
      (node (ref "X17") (pin "15") (pinfunction "S_15") (pintype "passive"))
    )
    (net (code "10") (name "/IN6") (class "Default")
      (node (ref "IC1") (pin "32") (pinfunction "B1Y_32") (pintype "bidirectional"))
      (node (ref "X17") (pin "13") (pinfunction "S_13") (pintype "passive"))
    )
    (net (code "11") (name "/IN7") (class "Default")
      (node (ref "IC1") (pin "34") (pinfunction "A2Y_34") (pintype "bidirectional"))
      (node (ref "X17") (pin "11") (pinfunction "S_11") (pintype "passive"))
    )
    (net (code "12") (name "/IN8") (class "Default")
      (node (ref "IC1") (pin "35") (pinfunction "A1Y_35") (pintype "bidirectional"))
      (node (ref "X17") (pin "9") (pinfunction "S_9") (pintype "passive"))
    )
    (net (code "13") (name "/IN9") (class "Default")
      (node (ref "IC2") (pin "23") (pinfunction "D2Y_23") (pintype "bidirectional"))
      (node (ref "X17") (pin "7") (pinfunction "S_7") (pintype "passive"))
    )
    (net (code "14") (name "/IN10") (class "Default")
      (node (ref "IC2") (pin "24") (pinfunction "D1Y_24") (pintype "bidirectional"))
      (node (ref "X17") (pin "5") (pinfunction "S_5") (pintype "passive"))
    )
    (net (code "15") (name "/IN11") (class "Default")
      (node (ref "IC2") (pin "26") (pinfunction "C2Y_26") (pintype "bidirectional"))
      (node (ref "X17") (pin "3") (pinfunction "S_3") (pintype "passive"))
    )
    (net (code "16") (name "/IN12") (class "Default")
      (node (ref "IC2") (pin "27") (pinfunction "C1Y_27") (pintype "bidirectional"))
      (node (ref "X17") (pin "1") (pinfunction "S_1") (pintype "passive"))
    )
    (net (code "17") (name "/IN13") (class "Default")
      (node (ref "IC2") (pin "31") (pinfunction "B2Y_31") (pintype "bidirectional"))
      (node (ref "X18") (pin "27") (pinfunction "S_27") (pintype "passive"))
    )
    (net (code "18") (name "/IN14") (class "Default")
      (node (ref "IC2") (pin "32") (pinfunction "B1Y_32") (pintype "bidirectional"))
      (node (ref "X18") (pin "25") (pinfunction "S_25") (pintype "passive"))
    )
    (net (code "19") (name "/IN15") (class "Default")
      (node (ref "IC2") (pin "34") (pinfunction "A2Y_34") (pintype "bidirectional"))
      (node (ref "X18") (pin "21") (pinfunction "S_21") (pintype "passive"))
    )
    (net (code "20") (name "/IN16") (class "Default")
      (node (ref "IC2") (pin "35") (pinfunction "A1Y_35") (pintype "bidirectional"))
      (node (ref "X18") (pin "19") (pinfunction "S_19") (pintype "passive"))
    )
    (net (code "21") (name "/IN17") (class "Default")
      (node (ref "IC3") (pin "23") (pinfunction "D2Y_23") (pintype "bidirectional"))
      (node (ref "X18") (pin "17") (pinfunction "S_17") (pintype "passive"))
    )
    (net (code "22") (name "/IN18") (class "Default")
      (node (ref "IC3") (pin "24") (pinfunction "D1Y_24") (pintype "bidirectional"))
      (node (ref "X18") (pin "15") (pinfunction "S_15") (pintype "passive"))
    )
    (net (code "23") (name "/IN19") (class "Default")
      (node (ref "IC3") (pin "26") (pinfunction "C2Y_26") (pintype "bidirectional"))
      (node (ref "X18") (pin "13") (pinfunction "S_13") (pintype "passive"))
    )
    (net (code "24") (name "/IN20") (class "Default")
      (node (ref "IC3") (pin "27") (pinfunction "C1Y_27") (pintype "bidirectional"))
      (node (ref "X18") (pin "11") (pinfunction "S_11") (pintype "passive"))
    )
    (net (code "25") (name "/IN21") (class "Default")
      (node (ref "IC3") (pin "31") (pinfunction "B2Y_31") (pintype "bidirectional"))
      (node (ref "X18") (pin "9") (pinfunction "S_9") (pintype "passive"))
    )
    (net (code "26") (name "/IN22") (class "Default")
      (node (ref "IC3") (pin "32") (pinfunction "B1Y_32") (pintype "bidirectional"))
      (node (ref "X18") (pin "7") (pinfunction "S_7") (pintype "passive"))
    )
    (net (code "27") (name "/IN23") (class "Default")
      (node (ref "IC3") (pin "34") (pinfunction "A2Y_34") (pintype "bidirectional"))
      (node (ref "X18") (pin "5") (pinfunction "S_5") (pintype "passive"))
    )
    (net (code "28") (name "/IN24") (class "Default")
      (node (ref "IC3") (pin "35") (pinfunction "A1Y_35") (pintype "bidirectional"))
      (node (ref "X18") (pin "3") (pinfunction "S_3") (pintype "passive"))
    )
    (net (code "29") (name "/IN25") (class "Default")
      (node (ref "IC4") (pin "23") (pinfunction "D2Y_23") (pintype "bidirectional"))
      (node (ref "X16") (pin "2") (pinfunction "S_2") (pintype "passive"))
    )
    (net (code "30") (name "/IN26") (class "Default")
      (node (ref "IC4") (pin "24") (pinfunction "D1Y_24") (pintype "bidirectional"))
      (node (ref "X16") (pin "4") (pinfunction "S_4") (pintype "passive"))
    )
    (net (code "31") (name "/IN27") (class "Default")
      (node (ref "IC4") (pin "26") (pinfunction "C2Y_26") (pintype "bidirectional"))
      (node (ref "X16") (pin "6") (pinfunction "S_6") (pintype "passive"))
    )
    (net (code "32") (name "/IN28") (class "Default")
      (node (ref "IC4") (pin "27") (pinfunction "C1Y_27") (pintype "bidirectional"))
      (node (ref "X16") (pin "8") (pinfunction "S_8") (pintype "passive"))
    )
    (net (code "33") (name "/IN29") (class "Default")
      (node (ref "IC4") (pin "31") (pinfunction "B2Y_31") (pintype "bidirectional"))
      (node (ref "X16") (pin "10") (pinfunction "S_10") (pintype "passive"))
    )
    (net (code "34") (name "/IN30") (class "Default")
      (node (ref "IC4") (pin "32") (pinfunction "B1Y_32") (pintype "bidirectional"))
      (node (ref "X16") (pin "12") (pinfunction "S_12") (pintype "passive"))
    )
    (net (code "35") (name "/IN31") (class "Default")
      (node (ref "IC4") (pin "34") (pinfunction "A2Y_34") (pintype "bidirectional"))
      (node (ref "X16") (pin "14") (pinfunction "S_14") (pintype "passive"))
    )
    (net (code "36") (name "/IN32") (class "Default")
      (node (ref "IC4") (pin "35") (pinfunction "A1Y_35") (pintype "bidirectional"))
      (node (ref "X16") (pin "16") (pinfunction "S_16") (pintype "passive"))
    )
    (net (code "37") (name "/IN33") (class "Default")
      (node (ref "IC5") (pin "23") (pinfunction "D2Y_23") (pintype "bidirectional"))
      (node (ref "X15") (pin "2") (pinfunction "S_2") (pintype "passive"))
    )
    (net (code "38") (name "/IN34") (class "Default")
      (node (ref "IC5") (pin "24") (pinfunction "D1Y_24") (pintype "bidirectional"))
      (node (ref "X15") (pin "4") (pinfunction "S_4") (pintype "passive"))
    )
    (net (code "39") (name "/IN35") (class "Default")
      (node (ref "IC5") (pin "26") (pinfunction "C2Y_26") (pintype "bidirectional"))
      (node (ref "X15") (pin "6") (pinfunction "S_6") (pintype "passive"))
    )
    (net (code "40") (name "/IN36") (class "Default")
      (node (ref "IC5") (pin "27") (pinfunction "C1Y_27") (pintype "bidirectional"))
      (node (ref "X15") (pin "8") (pinfunction "S_8") (pintype "passive"))
    )
    (net (code "41") (name "/IN37") (class "Default")
      (node (ref "IC5") (pin "31") (pinfunction "B2Y_31") (pintype "bidirectional"))
      (node (ref "X15") (pin "10") (pinfunction "S_10") (pintype "passive"))
    )
    (net (code "42") (name "/IN38") (class "Default")
      (node (ref "IC5") (pin "32") (pinfunction "B1Y_32") (pintype "bidirectional"))
      (node (ref "X15") (pin "12") (pinfunction "S_12") (pintype "passive"))
    )
    (net (code "43") (name "/IN39") (class "Default")
      (node (ref "IC5") (pin "34") (pinfunction "A2Y_34") (pintype "bidirectional"))
      (node (ref "X15") (pin "14") (pinfunction "S_14") (pintype "passive"))
    )
    (net (code "44") (name "/IN40") (class "Default")
      (node (ref "IC5") (pin "35") (pinfunction "A1Y_35") (pintype "bidirectional"))
      (node (ref "X15") (pin "16") (pinfunction "S_16") (pintype "passive"))
    )
    (net (code "45") (name "/IN41") (class "Default")
      (node (ref "IC6") (pin "23") (pinfunction "D2Y_23") (pintype "bidirectional"))
      (node (ref "X18") (pin "4") (pinfunction "S_4") (pintype "passive"))
    )
    (net (code "46") (name "/IN42") (class "Default")
      (node (ref "IC6") (pin "24") (pinfunction "D1Y_24") (pintype "bidirectional"))
      (node (ref "X18") (pin "6") (pinfunction "S_6") (pintype "passive"))
    )
    (net (code "47") (name "/IN43") (class "Default")
      (node (ref "IC6") (pin "26") (pinfunction "C2Y_26") (pintype "bidirectional"))
      (node (ref "X18") (pin "8") (pinfunction "S_8") (pintype "passive"))
    )
    (net (code "48") (name "/IN44") (class "Default")
      (node (ref "IC6") (pin "27") (pinfunction "C1Y_27") (pintype "bidirectional"))
      (node (ref "X18") (pin "10") (pinfunction "S_10") (pintype "passive"))
    )
    (net (code "49") (name "/IN45") (class "Default")
      (node (ref "IC6") (pin "31") (pinfunction "B2Y_31") (pintype "bidirectional"))
      (node (ref "X18") (pin "12") (pinfunction "S_12") (pintype "passive"))
    )
    (net (code "50") (name "/IN46") (class "Default")
      (node (ref "IC6") (pin "32") (pinfunction "B1Y_32") (pintype "bidirectional"))
      (node (ref "X18") (pin "14") (pinfunction "S_14") (pintype "passive"))
    )
    (net (code "51") (name "/IN47") (class "Default")
      (node (ref "IC6") (pin "34") (pinfunction "A2Y_34") (pintype "bidirectional"))
      (node (ref "X18") (pin "16") (pinfunction "S_16") (pintype "passive"))
    )
    (net (code "52") (name "/IN48") (class "Default")
      (node (ref "IC6") (pin "35") (pinfunction "A1Y_35") (pintype "bidirectional"))
      (node (ref "X18") (pin "18") (pinfunction "S_18") (pintype "passive"))
    )
    (net (code "53") (name "/IN49") (class "Default")
      (node (ref "IC7") (pin "23") (pinfunction "D2Y_23") (pintype "bidirectional"))
      (node (ref "X18") (pin "20") (pinfunction "S_20") (pintype "passive"))
    )
    (net (code "54") (name "/IN50") (class "Default")
      (node (ref "IC7") (pin "24") (pinfunction "D1Y_24") (pintype "bidirectional"))
      (node (ref "X18") (pin "22") (pinfunction "S_22") (pintype "passive"))
    )
    (net (code "55") (name "/IN51") (class "Default")
      (node (ref "IC7") (pin "26") (pinfunction "C2Y_26") (pintype "bidirectional"))
      (node (ref "X18") (pin "26") (pinfunction "S_26") (pintype "passive"))
    )
    (net (code "56") (name "/IN52") (class "Default")
      (node (ref "IC7") (pin "27") (pinfunction "C1Y_27") (pintype "bidirectional"))
      (node (ref "X18") (pin "28") (pinfunction "S_28") (pintype "passive"))
    )
    (net (code "57") (name "/IN53") (class "Default")
      (node (ref "IC7") (pin "31") (pinfunction "B2Y_31") (pintype "bidirectional"))
      (node (ref "X17") (pin "2") (pinfunction "S_2") (pintype "passive"))
    )
    (net (code "58") (name "/IN54") (class "Default")
      (node (ref "IC7") (pin "32") (pinfunction "B1Y_32") (pintype "bidirectional"))
      (node (ref "X17") (pin "4") (pinfunction "S_4") (pintype "passive"))
    )
    (net (code "59") (name "/IN55") (class "Default")
      (node (ref "IC7") (pin "34") (pinfunction "A2Y_34") (pintype "bidirectional"))
      (node (ref "X17") (pin "6") (pinfunction "S_6") (pintype "passive"))
    )
    (net (code "60") (name "/IN56") (class "Default")
      (node (ref "IC7") (pin "35") (pinfunction "A1Y_35") (pintype "bidirectional"))
      (node (ref "X17") (pin "8") (pinfunction "S_8") (pintype "passive"))
    )
    (net (code "61") (name "/IN57") (class "Default")
      (node (ref "IC8") (pin "23") (pinfunction "D2Y_23") (pintype "bidirectional"))
      (node (ref "X17") (pin "10") (pinfunction "S_10") (pintype "passive"))
    )
    (net (code "62") (name "/IN58") (class "Default")
      (node (ref "IC8") (pin "24") (pinfunction "D1Y_24") (pintype "bidirectional"))
      (node (ref "X17") (pin "12") (pinfunction "S_12") (pintype "passive"))
    )
    (net (code "63") (name "/IN59") (class "Default")
      (node (ref "IC8") (pin "26") (pinfunction "C2Y_26") (pintype "bidirectional"))
      (node (ref "X17") (pin "14") (pinfunction "S_14") (pintype "passive"))
    )
    (net (code "64") (name "/IN60") (class "Default")
      (node (ref "IC8") (pin "27") (pinfunction "C1Y_27") (pintype "bidirectional"))
      (node (ref "X17") (pin "16") (pinfunction "S_16") (pintype "passive"))
    )
    (net (code "65") (name "/IN61") (class "Default")
      (node (ref "IC8") (pin "31") (pinfunction "B2Y_31") (pintype "bidirectional"))
      (node (ref "X17") (pin "18") (pinfunction "S_18") (pintype "passive"))
    )
    (net (code "66") (name "/IN62") (class "Default")
      (node (ref "IC8") (pin "32") (pinfunction "B1Y_32") (pintype "bidirectional"))
      (node (ref "X17") (pin "20") (pinfunction "S_20") (pintype "passive"))
    )
    (net (code "67") (name "/IN63") (class "Default")
      (node (ref "IC8") (pin "34") (pinfunction "A2Y_34") (pintype "bidirectional"))
      (node (ref "X17") (pin "22") (pinfunction "S_22") (pintype "passive"))
    )
    (net (code "68") (name "/IN64") (class "Default")
      (node (ref "IC8") (pin "35") (pinfunction "A1Y_35") (pintype "bidirectional"))
      (node (ref "X17") (pin "24") (pinfunction "S_24") (pintype "passive"))
    )
    (net (code "69") (name "/IN65") (class "Default")
      (node (ref "IN65") (pin "1") (pinfunction "1_1") (pintype "passive"))
      (node (ref "J7") (pin "8") (pinfunction "8_8") (pintype "passive"))
      (node (ref "R2") (pin "P$2") (pinfunction "2_P$2") (pintype "passive"))
      (node (ref "X16") (pin "1") (pinfunction "S_1") (pintype "passive"))
    )
    (net (code "70") (name "/IN66") (class "Default")
      (node (ref "IN66") (pin "1") (pinfunction "1_1") (pintype "passive"))
      (node (ref "J7") (pin "7") (pinfunction "7_7") (pintype "passive"))
      (node (ref "R4") (pin "P$2") (pinfunction "2_P$2") (pintype "passive"))
      (node (ref "X16") (pin "3") (pinfunction "S_3") (pintype "passive"))
    )
    (net (code "71") (name "/IN67") (class "Default")
      (node (ref "IN67") (pin "1") (pinfunction "1_1") (pintype "passive"))
      (node (ref "J7") (pin "6") (pinfunction "6_6") (pintype "passive"))
      (node (ref "R6") (pin "P$2") (pinfunction "2_P$2") (pintype "passive"))
      (node (ref "X16") (pin "5") (pinfunction "S_5") (pintype "passive"))
    )
    (net (code "72") (name "/IN68") (class "Default")
      (node (ref "IN68") (pin "1") (pinfunction "1_1") (pintype "passive"))
      (node (ref "J7") (pin "5") (pinfunction "5_5") (pintype "passive"))
      (node (ref "R9") (pin "P$2") (pinfunction "2_P$2") (pintype "passive"))
      (node (ref "X16") (pin "7") (pinfunction "S_7") (pintype "passive"))
    )
    (net (code "73") (name "/IN69") (class "Default")
      (node (ref "IN69") (pin "1") (pinfunction "1_1") (pintype "passive"))
      (node (ref "J7") (pin "4") (pinfunction "4_4") (pintype "passive"))
      (node (ref "R11") (pin "P$2") (pinfunction "2_P$2") (pintype "passive"))
      (node (ref "X16") (pin "9") (pinfunction "S_9") (pintype "passive"))
    )
    (net (code "74") (name "/IN70") (class "Default")
      (node (ref "IN70") (pin "1") (pinfunction "1_1") (pintype "passive"))
      (node (ref "J7") (pin "3") (pinfunction "3_3") (pintype "passive"))
      (node (ref "R13") (pin "P$2") (pinfunction "2_P$2") (pintype "passive"))
      (node (ref "X16") (pin "11") (pinfunction "S_11") (pintype "passive"))
    )
    (net (code "75") (name "/IN71") (class "Default")
      (node (ref "IN71") (pin "1") (pinfunction "1_1") (pintype "passive"))
      (node (ref "J7") (pin "2") (pinfunction "2_2") (pintype "passive"))
      (node (ref "R17") (pin "P$2") (pinfunction "2_P$2") (pintype "passive"))
      (node (ref "X16") (pin "13") (pinfunction "S_13") (pintype "passive"))
    )
    (net (code "76") (name "/IN72") (class "Default")
      (node (ref "IN72") (pin "1") (pinfunction "1_1") (pintype "passive"))
      (node (ref "J7") (pin "1") (pinfunction "1_1") (pintype "passive"))
      (node (ref "R19") (pin "P$2") (pinfunction "2_P$2") (pintype "passive"))
      (node (ref "X16") (pin "15") (pinfunction "S_15") (pintype "passive"))
    )
    (net (code "77") (name "/IN73") (class "Default")
      (node (ref "IN73") (pin "1") (pinfunction "1_1") (pintype "passive"))
      (node (ref "J8") (pin "8") (pinfunction "8_8") (pintype "passive"))
      (node (ref "R3") (pin "P$2") (pinfunction "2_P$2") (pintype "passive"))
      (node (ref "X15") (pin "1") (pinfunction "S_1") (pintype "passive"))
    )
    (net (code "78") (name "/IN74") (class "Default")
      (node (ref "IN74") (pin "1") (pinfunction "1_1") (pintype "passive"))
      (node (ref "J8") (pin "7") (pinfunction "7_7") (pintype "passive"))
      (node (ref "R5") (pin "P$2") (pinfunction "2_P$2") (pintype "passive"))
      (node (ref "X15") (pin "3") (pinfunction "S_3") (pintype "passive"))
    )
    (net (code "79") (name "/IN75") (class "Default")
      (node (ref "IN75") (pin "1") (pinfunction "1_1") (pintype "passive"))
      (node (ref "J8") (pin "6") (pinfunction "6_6") (pintype "passive"))
      (node (ref "R7") (pin "P$2") (pinfunction "2_P$2") (pintype "passive"))
      (node (ref "X15") (pin "5") (pinfunction "S_5") (pintype "passive"))
    )
    (net (code "80") (name "/IN76") (class "Default")
      (node (ref "IN76") (pin "1") (pinfunction "1_1") (pintype "passive"))
      (node (ref "J8") (pin "5") (pinfunction "5_5") (pintype "passive"))
      (node (ref "R10") (pin "P$2") (pinfunction "2_P$2") (pintype "passive"))
      (node (ref "X15") (pin "7") (pinfunction "S_7") (pintype "passive"))
    )
    (net (code "81") (name "/IN77") (class "Default")
      (node (ref "IN77") (pin "1") (pinfunction "1_1") (pintype "passive"))
      (node (ref "J8") (pin "4") (pinfunction "4_4") (pintype "passive"))
      (node (ref "R12") (pin "P$2") (pinfunction "2_P$2") (pintype "passive"))
      (node (ref "X15") (pin "9") (pinfunction "S_9") (pintype "passive"))
    )
    (net (code "82") (name "/IN78") (class "Default")
      (node (ref "IN78") (pin "1") (pinfunction "1_1") (pintype "passive"))
      (node (ref "J8") (pin "3") (pinfunction "3_3") (pintype "passive"))
      (node (ref "R14") (pin "P$2") (pinfunction "2_P$2") (pintype "passive"))
      (node (ref "X15") (pin "11") (pinfunction "S_11") (pintype "passive"))
    )
    (net (code "83") (name "/IN79") (class "Default")
      (node (ref "IN79") (pin "1") (pinfunction "1_1") (pintype "passive"))
      (node (ref "J8") (pin "2") (pinfunction "2_2") (pintype "passive"))
      (node (ref "R18") (pin "P$2") (pinfunction "2_P$2") (pintype "passive"))
      (node (ref "X15") (pin "13") (pinfunction "S_13") (pintype "passive"))
    )
    (net (code "84") (name "/IN80") (class "Default")
      (node (ref "IN80") (pin "1") (pinfunction "1_1") (pintype "passive"))
      (node (ref "J8") (pin "1") (pinfunction "1_1") (pintype "passive"))
      (node (ref "R20") (pin "P$2") (pinfunction "2_P$2") (pintype "passive"))
      (node (ref "X15") (pin "15") (pinfunction "S_15") (pintype "passive"))
    )
    (net (code "85") (name "/IO1") (class "Default")
      (node (ref "J12") (pin "1") (pinfunction "P$1_1") (pintype "bidirectional"))
      (node (ref "X13") (pin "11") (pinfunction "S_11") (pintype "passive"))
    )
    (net (code "86") (name "/IO2") (class "Default")
      (node (ref "J12") (pin "2") (pinfunction "P$2_2") (pintype "bidirectional"))
      (node (ref "X13") (pin "13") (pinfunction "S_13") (pintype "passive"))
    )
    (net (code "87") (name "/IO3") (class "Default")
      (node (ref "J4") (pin "1") (pinfunction "P$1_1") (pintype "bidirectional"))
      (node (ref "X13") (pin "15") (pinfunction "S_15") (pintype "passive"))
    )
    (net (code "88") (name "/IO4") (class "Default")
      (node (ref "J4") (pin "2") (pinfunction "P$2_2") (pintype "bidirectional"))
      (node (ref "X13") (pin "17") (pinfunction "S_17") (pintype "passive"))
    )
    (net (code "89") (name "/IO5") (class "Default")
      (node (ref "J3") (pin "1") (pinfunction "P$1_1") (pintype "bidirectional"))
      (node (ref "X13") (pin "19") (pinfunction "S_19") (pintype "passive"))
    )
    (net (code "90") (name "/IO6") (class "Default")
      (node (ref "J3") (pin "2") (pinfunction "P$2_2") (pintype "bidirectional"))
      (node (ref "X13") (pin "21") (pinfunction "S_21") (pintype "passive"))
    )
    (net (code "91") (name "/IO7") (class "Default")
      (node (ref "J3") (pin "3") (pinfunction "P$3_3") (pintype "bidirectional"))
      (node (ref "X13") (pin "25") (pinfunction "S_25") (pintype "passive"))
    )
    (net (code "92") (name "/IO8") (class "Default")
      (node (ref "J14") (pin "8") (pinfunction "8_8") (pintype "passive"))
      (node (ref "X14") (pin "1") (pinfunction "S_1") (pintype "passive"))
    )
    (net (code "93") (name "/IO9") (class "Default")
      (node (ref "J14") (pin "7") (pinfunction "7_7") (pintype "passive"))
      (node (ref "X14") (pin "3") (pinfunction "S_3") (pintype "passive"))
    )
    (net (code "94") (name "/IO10") (class "Default")
      (node (ref "J14") (pin "6") (pinfunction "6_6") (pintype "passive"))
      (node (ref "X14") (pin "5") (pinfunction "S_5") (pintype "passive"))
    )
    (net (code "95") (name "/IO11") (class "Default")
      (node (ref "J14") (pin "5") (pinfunction "5_5") (pintype "passive"))
      (node (ref "X14") (pin "7") (pinfunction "S_7") (pintype "passive"))
    )
    (net (code "96") (name "/IO12") (class "Default")
      (node (ref "J14") (pin "4") (pinfunction "4_4") (pintype "passive"))
      (node (ref "X14") (pin "9") (pinfunction "S_9") (pintype "passive"))
    )
    (net (code "97") (name "/IO13") (class "Default")
      (node (ref "J14") (pin "3") (pinfunction "3_3") (pintype "passive"))
      (node (ref "X14") (pin "11") (pinfunction "S_11") (pintype "passive"))
    )
    (net (code "98") (name "/IO14") (class "Default")
      (node (ref "J14") (pin "2") (pinfunction "2_2") (pintype "passive"))
      (node (ref "X14") (pin "13") (pinfunction "S_13") (pintype "passive"))
    )
    (net (code "99") (name "/IO15") (class "Default")
      (node (ref "J14") (pin "1") (pinfunction "1_1") (pintype "passive"))
      (node (ref "X14") (pin "15") (pinfunction "S_15") (pintype "passive"))
    )
    (net (code "100") (name "/IO16") (class "Default")
      (node (ref "J15") (pin "8") (pinfunction "8_8") (pintype "passive"))
      (node (ref "X14") (pin "2") (pinfunction "S_2") (pintype "passive"))
    )
    (net (code "101") (name "/IO17") (class "Default")
      (node (ref "J15") (pin "7") (pinfunction "7_7") (pintype "passive"))
      (node (ref "X14") (pin "4") (pinfunction "S_4") (pintype "passive"))
    )
    (net (code "102") (name "/IO18") (class "Default")
      (node (ref "J15") (pin "6") (pinfunction "6_6") (pintype "passive"))
      (node (ref "X14") (pin "6") (pinfunction "S_6") (pintype "passive"))
    )
    (net (code "103") (name "/IO19") (class "Default")
      (node (ref "J15") (pin "5") (pinfunction "5_5") (pintype "passive"))
      (node (ref "X14") (pin "8") (pinfunction "S_8") (pintype "passive"))
    )
    (net (code "104") (name "/IO20") (class "Default")
      (node (ref "J15") (pin "4") (pinfunction "4_4") (pintype "passive"))
      (node (ref "X14") (pin "10") (pinfunction "S_10") (pintype "passive"))
    )
    (net (code "105") (name "/IO21") (class "Default")
      (node (ref "J15") (pin "3") (pinfunction "3_3") (pintype "passive"))
      (node (ref "X14") (pin "12") (pinfunction "S_12") (pintype "passive"))
    )
    (net (code "106") (name "/IO22") (class "Default")
      (node (ref "J15") (pin "2") (pinfunction "2_2") (pintype "passive"))
      (node (ref "X14") (pin "14") (pinfunction "S_14") (pintype "passive"))
    )
    (net (code "107") (name "/IO23") (class "Default")
      (node (ref "J15") (pin "1") (pinfunction "1_1") (pintype "passive"))
      (node (ref "X14") (pin "16") (pinfunction "S_16") (pintype "passive"))
    )
    (net (code "108") (name "/OE") (class "Default")
      (node (ref "J3") (pin "4") (pinfunction "P$4_4") (pintype "bidirectional"))
      (node (ref "LED_OE") (pin "A") (pinfunction "A_A") (pintype "passive"))
      (node (ref "R1") (pin "1") (pinfunction "1_1") (pintype "passive"))
      (node (ref "VSLUE") (pin "1") (pinfunction "~{1OE}_1") (pintype "input"))
      (node (ref "VSLUE") (pin "19") (pinfunction "~{2OE}_19") (pintype "input"))
      (node (ref "VSLUE2") (pin "1") (pinfunction "~{1OE}_1") (pintype "input"))
      (node (ref "VSLUE2") (pin "19") (pinfunction "~{2OE}_19") (pintype "input"))
      (node (ref "VSLUE3") (pin "1") (pinfunction "~{1OE}_1") (pintype "input"))
      (node (ref "VSLUE3") (pin "19") (pinfunction "~{2OE}_19") (pintype "input"))
      (node (ref "VSLUE4") (pin "1") (pinfunction "~{1OE}_1") (pintype "input"))
      (node (ref "VSLUE4") (pin "19") (pinfunction "~{2OE}_19") (pintype "input"))
      (node (ref "X13") (pin "27") (pinfunction "S_27") (pintype "passive"))
    )
    (net (code "109") (name "/OUT1") (class "Default")
      (node (ref "OJ1") (pin "1") (pinfunction "1_1") (pintype "bidirectional"))
      (node (ref "OUT1") (pin "1") (pinfunction "1_1") (pintype "passive"))
      (node (ref "VSLUE") (pin "16") (pinfunction "1Y2_16") (pintype "output"))
      (node (ref "VSLUE") (pin "18") (pinfunction "1Y1_18") (pintype "output"))
    )
    (net (code "110") (name "/OUT1IN") (class "Default")
      (node (ref "J1") (pin "2") (pinfunction "2_2") (pintype "passive"))
      (node (ref "VSLUE") (pin "2") (pinfunction "1A1_2") (pintype "input"))
      (node (ref "VSLUE") (pin "4") (pinfunction "1A2_4") (pintype "input"))
      (node (ref "X13") (pin "9") (pinfunction "S_9") (pintype "passive"))
    )
    (net (code "111") (name "/OUT2") (class "Default")
      (node (ref "OJ2") (pin "1") (pinfunction "1_1") (pintype "bidirectional"))
      (node (ref "OUT2") (pin "1") (pinfunction "1_1") (pintype "passive"))
      (node (ref "VSLUE") (pin "12") (pinfunction "1Y4_12") (pintype "output"))
      (node (ref "VSLUE") (pin "14") (pinfunction "1Y3_14") (pintype "output"))
    )
    (net (code "112") (name "/OUT2IN") (class "Default")
      (node (ref "J1") (pin "4") (pinfunction "4_4") (pintype "passive"))
      (node (ref "VSLUE") (pin "6") (pinfunction "1A3_6") (pintype "input"))
      (node (ref "VSLUE") (pin "8") (pinfunction "1A4_8") (pintype "input"))
      (node (ref "X13") (pin "7") (pinfunction "S_7") (pintype "passive"))
    )
    (net (code "113") (name "/OUT3") (class "Default")
      (node (ref "OJ3") (pin "1") (pinfunction "1_1") (pintype "bidirectional"))
      (node (ref "OUT3") (pin "1") (pinfunction "1_1") (pintype "passive"))
      (node (ref "VSLUE") (pin "7") (pinfunction "2Y2_7") (pintype "output"))
      (node (ref "VSLUE") (pin "9") (pinfunction "2Y1_9") (pintype "output"))
    )
    (net (code "114") (name "/OUT3IN") (class "Default")
      (node (ref "J1") (pin "6") (pinfunction "6_6") (pintype "passive"))
      (node (ref "VSLUE") (pin "11") (pinfunction "2A1_11") (pintype "input"))
      (node (ref "VSLUE") (pin "13") (pinfunction "2A2_13") (pintype "input"))
      (node (ref "X13") (pin "5") (pinfunction "S_5") (pintype "passive"))
    )
    (net (code "115") (name "/OUT4") (class "Default")
      (node (ref "OJ4") (pin "1") (pinfunction "1_1") (pintype "bidirectional"))
      (node (ref "OUT4") (pin "1") (pinfunction "1_1") (pintype "passive"))
      (node (ref "VSLUE") (pin "3") (pinfunction "2Y4_3") (pintype "output"))
      (node (ref "VSLUE") (pin "5") (pinfunction "2Y3_5") (pintype "output"))
    )
    (net (code "116") (name "/OUT4IN") (class "Default")
      (node (ref "J1") (pin "8") (pinfunction "8_8") (pintype "passive"))
      (node (ref "VSLUE") (pin "15") (pinfunction "2A3_15") (pintype "input"))
      (node (ref "VSLUE") (pin "17") (pinfunction "2A4_17") (pintype "input"))
      (node (ref "X13") (pin "3") (pinfunction "S_3") (pintype "passive"))
    )
    (net (code "117") (name "/OUT5") (class "Default")
      (node (ref "OJ12") (pin "1") (pinfunction "1_1") (pintype "bidirectional"))
      (node (ref "OUT5") (pin "1") (pinfunction "1_1") (pintype "passive"))
      (node (ref "VSLUE2") (pin "16") (pinfunction "1Y2_16") (pintype "output"))
      (node (ref "VSLUE2") (pin "18") (pinfunction "1Y1_18") (pintype "output"))
    )
    (net (code "118") (name "/OUT5IN") (class "Default")
      (node (ref "J6") (pin "2") (pinfunction "2_2") (pintype "passive"))
      (node (ref "VSLUE2") (pin "2") (pinfunction "1A1_2") (pintype "input"))
      (node (ref "VSLUE2") (pin "4") (pinfunction "1A2_4") (pintype "input"))
      (node (ref "X13") (pin "10") (pinfunction "S_10") (pintype "passive"))
    )
    (net (code "119") (name "/OUT6") (class "Default")
      (node (ref "OJ11") (pin "1") (pinfunction "1_1") (pintype "bidirectional"))
      (node (ref "OUT6") (pin "1") (pinfunction "1_1") (pintype "passive"))
      (node (ref "VSLUE2") (pin "12") (pinfunction "1Y4_12") (pintype "output"))
      (node (ref "VSLUE2") (pin "14") (pinfunction "1Y3_14") (pintype "output"))
    )
    (net (code "120") (name "/OUT6IN") (class "Default")
      (node (ref "J6") (pin "4") (pinfunction "4_4") (pintype "passive"))
      (node (ref "VSLUE2") (pin "6") (pinfunction "1A3_6") (pintype "input"))
      (node (ref "VSLUE2") (pin "8") (pinfunction "1A4_8") (pintype "input"))
      (node (ref "X13") (pin "8") (pinfunction "S_8") (pintype "passive"))
    )
    (net (code "121") (name "/OUT7") (class "Default")
      (node (ref "OJ10") (pin "1") (pinfunction "1_1") (pintype "bidirectional"))
      (node (ref "OUT7") (pin "1") (pinfunction "1_1") (pintype "passive"))
      (node (ref "VSLUE2") (pin "7") (pinfunction "2Y2_7") (pintype "output"))
      (node (ref "VSLUE2") (pin "9") (pinfunction "2Y1_9") (pintype "output"))
    )
    (net (code "122") (name "/OUT7IN") (class "Default")
      (node (ref "J6") (pin "6") (pinfunction "6_6") (pintype "passive"))
      (node (ref "VSLUE2") (pin "11") (pinfunction "2A1_11") (pintype "input"))
      (node (ref "VSLUE2") (pin "13") (pinfunction "2A2_13") (pintype "input"))
      (node (ref "X13") (pin "6") (pinfunction "S_6") (pintype "passive"))
    )
    (net (code "123") (name "/OUT8") (class "Default")
      (node (ref "OJ9") (pin "1") (pinfunction "1_1") (pintype "bidirectional"))
      (node (ref "OUT8") (pin "1") (pinfunction "1_1") (pintype "passive"))
      (node (ref "VSLUE2") (pin "3") (pinfunction "2Y4_3") (pintype "output"))
      (node (ref "VSLUE2") (pin "5") (pinfunction "2Y3_5") (pintype "output"))
    )
    (net (code "124") (name "/OUT8IN") (class "Default")
      (node (ref "J6") (pin "8") (pinfunction "8_8") (pintype "passive"))
      (node (ref "VSLUE2") (pin "15") (pinfunction "2A3_15") (pintype "input"))
      (node (ref "VSLUE2") (pin "17") (pinfunction "2A4_17") (pintype "input"))
      (node (ref "X13") (pin "4") (pinfunction "S_4") (pintype "passive"))
    )
    (net (code "125") (name "/OUT9") (class "Default")
      (node (ref "OJ16") (pin "1") (pinfunction "1_1") (pintype "bidirectional"))
      (node (ref "OUT9") (pin "1") (pinfunction "1_1") (pintype "passive"))
      (node (ref "VSLUE3") (pin "16") (pinfunction "1Y2_16") (pintype "output"))
      (node (ref "VSLUE3") (pin "18") (pinfunction "1Y1_18") (pintype "output"))
    )
    (net (code "126") (name "/OUT9IN") (class "Default")
      (node (ref "J2") (pin "2") (pinfunction "2_2") (pintype "passive"))
      (node (ref "VSLUE3") (pin "2") (pinfunction "1A1_2") (pintype "input"))
      (node (ref "VSLUE3") (pin "4") (pinfunction "1A2_4") (pintype "input"))
      (node (ref "X13") (pin "12") (pinfunction "S_12") (pintype "passive"))
    )
    (net (code "127") (name "/OUT10") (class "Default")
      (node (ref "OJ15") (pin "1") (pinfunction "1_1") (pintype "bidirectional"))
      (node (ref "OUT10") (pin "1") (pinfunction "1_1") (pintype "passive"))
      (node (ref "VSLUE3") (pin "12") (pinfunction "1Y4_12") (pintype "output"))
      (node (ref "VSLUE3") (pin "14") (pinfunction "1Y3_14") (pintype "output"))
    )
    (net (code "128") (name "/OUT10IN") (class "Default")
      (node (ref "J2") (pin "4") (pinfunction "4_4") (pintype "passive"))
      (node (ref "VSLUE3") (pin "6") (pinfunction "1A3_6") (pintype "input"))
      (node (ref "VSLUE3") (pin "8") (pinfunction "1A4_8") (pintype "input"))
      (node (ref "X13") (pin "14") (pinfunction "S_14") (pintype "passive"))
    )
    (net (code "129") (name "/OUT11") (class "Default")
      (node (ref "OJ14") (pin "1") (pinfunction "1_1") (pintype "bidirectional"))
      (node (ref "OUT11") (pin "1") (pinfunction "1_1") (pintype "passive"))
      (node (ref "VSLUE3") (pin "7") (pinfunction "2Y2_7") (pintype "output"))
      (node (ref "VSLUE3") (pin "9") (pinfunction "2Y1_9") (pintype "output"))
    )
    (net (code "130") (name "/OUT11IN") (class "Default")
      (node (ref "J2") (pin "6") (pinfunction "6_6") (pintype "passive"))
      (node (ref "VSLUE3") (pin "11") (pinfunction "2A1_11") (pintype "input"))
      (node (ref "VSLUE3") (pin "13") (pinfunction "2A2_13") (pintype "input"))
      (node (ref "X13") (pin "16") (pinfunction "S_16") (pintype "passive"))
    )
    (net (code "131") (name "/OUT12") (class "Default")
      (node (ref "OJ13") (pin "1") (pinfunction "1_1") (pintype "bidirectional"))
      (node (ref "OUT12") (pin "1") (pinfunction "1_1") (pintype "passive"))
      (node (ref "VSLUE3") (pin "3") (pinfunction "2Y4_3") (pintype "output"))
      (node (ref "VSLUE3") (pin "5") (pinfunction "2Y3_5") (pintype "output"))
    )
    (net (code "132") (name "/OUT12IN") (class "Default")
      (node (ref "J2") (pin "8") (pinfunction "8_8") (pintype "passive"))
      (node (ref "VSLUE3") (pin "15") (pinfunction "2A3_15") (pintype "input"))
      (node (ref "VSLUE3") (pin "17") (pinfunction "2A4_17") (pintype "input"))
      (node (ref "X13") (pin "18") (pinfunction "S_18") (pintype "passive"))
    )
    (net (code "133") (name "/OUT13") (class "Default")
      (node (ref "OJ20") (pin "1") (pinfunction "1_1") (pintype "bidirectional"))
      (node (ref "OUT13") (pin "1") (pinfunction "1_1") (pintype "passive"))
      (node (ref "VSLUE4") (pin "16") (pinfunction "1Y2_16") (pintype "output"))
      (node (ref "VSLUE4") (pin "18") (pinfunction "1Y1_18") (pintype "output"))
    )
    (net (code "134") (name "/OUT13IN") (class "Default")
      (node (ref "J5") (pin "2") (pinfunction "2_2") (pintype "passive"))
      (node (ref "VSLUE4") (pin "2") (pinfunction "1A1_2") (pintype "input"))
      (node (ref "VSLUE4") (pin "4") (pinfunction "1A2_4") (pintype "input"))
      (node (ref "X13") (pin "20") (pinfunction "S_20") (pintype "passive"))
    )
    (net (code "135") (name "/OUT14") (class "Default")
      (node (ref "OJ19") (pin "1") (pinfunction "1_1") (pintype "bidirectional"))
      (node (ref "OUT14") (pin "1") (pinfunction "1_1") (pintype "passive"))
      (node (ref "VSLUE4") (pin "12") (pinfunction "1Y4_12") (pintype "output"))
      (node (ref "VSLUE4") (pin "14") (pinfunction "1Y3_14") (pintype "output"))
    )
    (net (code "136") (name "/OUT14IN") (class "Default")
      (node (ref "J5") (pin "4") (pinfunction "4_4") (pintype "passive"))
      (node (ref "VSLUE4") (pin "6") (pinfunction "1A3_6") (pintype "input"))
      (node (ref "VSLUE4") (pin "8") (pinfunction "1A4_8") (pintype "input"))
      (node (ref "X13") (pin "22") (pinfunction "S_22") (pintype "passive"))
    )
    (net (code "137") (name "/OUT15") (class "Default")
      (node (ref "OJ18") (pin "1") (pinfunction "1_1") (pintype "bidirectional"))
      (node (ref "OUT15") (pin "1") (pinfunction "1_1") (pintype "passive"))
      (node (ref "VSLUE4") (pin "7") (pinfunction "2Y2_7") (pintype "output"))
      (node (ref "VSLUE4") (pin "9") (pinfunction "2Y1_9") (pintype "output"))
    )
    (net (code "138") (name "/OUT15IN") (class "Default")
      (node (ref "J5") (pin "6") (pinfunction "6_6") (pintype "passive"))
      (node (ref "VSLUE4") (pin "11") (pinfunction "2A1_11") (pintype "input"))
      (node (ref "VSLUE4") (pin "13") (pinfunction "2A2_13") (pintype "input"))
      (node (ref "X13") (pin "26") (pinfunction "S_26") (pintype "passive"))
    )
    (net (code "139") (name "/OUT16") (class "Default")
      (node (ref "OJ17") (pin "1") (pinfunction "1_1") (pintype "bidirectional"))
      (node (ref "OUT16") (pin "1") (pinfunction "1_1") (pintype "passive"))
      (node (ref "VSLUE4") (pin "3") (pinfunction "2Y4_3") (pintype "output"))
      (node (ref "VSLUE4") (pin "5") (pinfunction "2Y3_5") (pintype "output"))
    )
    (net (code "140") (name "/OUT16IN") (class "Default")
      (node (ref "J5") (pin "8") (pinfunction "8_8") (pintype "passive"))
      (node (ref "VSLUE4") (pin "15") (pinfunction "2A3_15") (pintype "input"))
      (node (ref "VSLUE4") (pin "17") (pinfunction "2A4_17") (pintype "input"))
      (node (ref "X13") (pin "28") (pinfunction "S_28") (pintype "passive"))
    )
    (net (code "141") (name "/OUT17") (class "Default")
      (node (ref "J17") (pin "1") (pinfunction "1_1") (pintype "passive"))
      (node (ref "OUT17") (pin "1") (pinfunction "1_1") (pintype "passive"))
      (node (ref "X17") (pin "25") (pinfunction "S_25") (pintype "passive"))
    )
    (net (code "142") (name "/OUT18") (class "Default")
      (node (ref "J17") (pin "2") (pinfunction "2_2") (pintype "passive"))
      (node (ref "OUT18") (pin "1") (pinfunction "1_1") (pintype "passive"))
      (node (ref "X17") (pin "26") (pinfunction "S_26") (pintype "passive"))
    )
    (net (code "143") (name "/OUT19") (class "Default")
      (node (ref "J17") (pin "3") (pinfunction "3_3") (pintype "passive"))
      (node (ref "OUT19") (pin "1") (pinfunction "1_1") (pintype "passive"))
      (node (ref "X14") (pin "17") (pinfunction "S_17") (pintype "passive"))
    )
    (net (code "144") (name "/OUT20") (class "Default")
      (node (ref "J17") (pin "4") (pinfunction "4_4") (pintype "passive"))
      (node (ref "OUT20") (pin "1") (pinfunction "1_1") (pintype "passive"))
      (node (ref "X14") (pin "19") (pinfunction "S_19") (pintype "passive"))
    )
    (net (code "145") (name "/OUT21") (class "Default")
      (node (ref "J17") (pin "5") (pinfunction "5_5") (pintype "passive"))
      (node (ref "OUT21") (pin "1") (pinfunction "1_1") (pintype "passive"))
      (node (ref "X14") (pin "21") (pinfunction "S_21") (pintype "passive"))
    )
    (net (code "146") (name "/OUT22") (class "Default")
      (node (ref "J17") (pin "6") (pinfunction "6_6") (pintype "passive"))
      (node (ref "OUT22") (pin "1") (pinfunction "1_1") (pintype "passive"))
      (node (ref "X14") (pin "23") (pinfunction "S_23") (pintype "passive"))
    )
    (net (code "147") (name "/OUT23") (class "Default")
      (node (ref "J17") (pin "7") (pinfunction "7_7") (pintype "passive"))
      (node (ref "OUT23") (pin "1") (pinfunction "1_1") (pintype "passive"))
      (node (ref "X14") (pin "25") (pinfunction "S_25") (pintype "passive"))
    )
    (net (code "148") (name "/OUT24") (class "Default")
      (node (ref "J17") (pin "8") (pinfunction "8_8") (pintype "passive"))
      (node (ref "OUT24") (pin "1") (pinfunction "1_1") (pintype "passive"))
      (node (ref "X14") (pin "18") (pinfunction "S_18") (pintype "passive"))
    )
    (net (code "149") (name "/OUT25") (class "Default")
      (node (ref "J16") (pin "1") (pinfunction "1_1") (pintype "passive"))
      (node (ref "OUT25") (pin "1") (pinfunction "1_1") (pintype "passive"))
      (node (ref "X14") (pin "20") (pinfunction "S_20") (pintype "passive"))
    )
    (net (code "150") (name "/OUT26") (class "Default")
      (node (ref "J16") (pin "2") (pinfunction "2_2") (pintype "passive"))
      (node (ref "OUT26") (pin "1") (pinfunction "1_1") (pintype "passive"))
      (node (ref "X14") (pin "22") (pinfunction "S_22") (pintype "passive"))
    )
    (net (code "151") (name "/OUT27") (class "Default")
      (node (ref "J16") (pin "3") (pinfunction "3_3") (pintype "passive"))
      (node (ref "OUT27") (pin "1") (pinfunction "1_1") (pintype "passive"))
      (node (ref "X14") (pin "24") (pinfunction "S_24") (pintype "passive"))
    )
    (net (code "152") (name "/OUT28") (class "Default")
      (node (ref "J16") (pin "4") (pinfunction "4_4") (pintype "passive"))
      (node (ref "OUT28") (pin "1") (pinfunction "1_1") (pintype "passive"))
      (node (ref "X14") (pin "26") (pinfunction "S_26") (pintype "passive"))
    )
    (net (code "153") (name "/OUT29") (class "Default")
      (node (ref "J16") (pin "5") (pinfunction "5_5") (pintype "passive"))
      (node (ref "J9") (pin "8") (pinfunction "8_8") (pintype "passive"))
      (node (ref "OUT29") (pin "1") (pinfunction "1_1") (pintype "passive"))
      (node (ref "X1") (pin "2") (pinfunction "S_2") (pintype "passive"))
      (node (ref "X17") (pin "27") (pinfunction "S_27") (pintype "passive"))
    )
    (net (code "154") (name "/OUT30") (class "Default")
      (node (ref "J16") (pin "6") (pinfunction "6_6") (pintype "passive"))
      (node (ref "J9") (pin "7") (pinfunction "7_7") (pintype "passive"))
      (node (ref "OUT30") (pin "1") (pinfunction "1_1") (pintype "passive"))
      (node (ref "X1") (pin "4") (pinfunction "S_4") (pintype "passive"))
      (node (ref "X17") (pin "28") (pinfunction "S_28") (pintype "passive"))
    )
    (net (code "155") (name "/OUT31") (class "Default")
      (node (ref "J16") (pin "7") (pinfunction "7_7") (pintype "passive"))
      (node (ref "J9") (pin "6") (pinfunction "6_6") (pintype "passive"))
      (node (ref "OUT31") (pin "1") (pinfunction "1_1") (pintype "passive"))
      (node (ref "X1") (pin "6") (pinfunction "S_6") (pintype "passive"))
      (node (ref "X14") (pin "27") (pinfunction "S_27") (pintype "passive"))
    )
    (net (code "156") (name "/OUT32") (class "Default")
      (node (ref "J16") (pin "8") (pinfunction "8_8") (pintype "passive"))
      (node (ref "J9") (pin "5") (pinfunction "5_5") (pintype "passive"))
      (node (ref "OUT32") (pin "1") (pinfunction "1_1") (pintype "passive"))
      (node (ref "X1") (pin "8") (pinfunction "S_8") (pintype "passive"))
      (node (ref "X14") (pin "28") (pinfunction "S_28") (pintype "passive"))
    )
    (net (code "157") (name "GND") (class "Default")
      (node (ref "C1") (pin "1") (pinfunction "1_1") (pintype "passive"))
      (node (ref "C10") (pin "1") (pinfunction "1_1") (pintype "passive"))
      (node (ref "C11") (pin "1") (pinfunction "1_1") (pintype "passive"))
      (node (ref "C12") (pin "1") (pinfunction "1_1") (pintype "passive"))
      (node (ref "C2") (pin "1") (pinfunction "1_1") (pintype "passive"))
      (node (ref "C3") (pin "1") (pinfunction "1_1") (pintype "passive"))
      (node (ref "C4") (pin "1") (pinfunction "1_1") (pintype "passive"))
      (node (ref "C5") (pin "1") (pinfunction "1_1") (pintype "passive"))
      (node (ref "C6") (pin "1") (pinfunction "1_1") (pintype "passive"))
      (node (ref "C7") (pin "1") (pinfunction "1_1") (pintype "passive"))
      (node (ref "C8") (pin "1") (pinfunction "1_1") (pintype "passive"))
      (node (ref "C9") (pin "1") (pinfunction "1_1") (pintype "passive"))
      (node (ref "CP11") (pin "1") (pinfunction "1_1") (pintype "passive"))
      (node (ref "CP2") (pin "2") (pinfunction "2_2") (pintype "passive"))
      (node (ref "CP6") (pin "2") (pinfunction "2_2") (pintype "passive"))
      (node (ref "IC1") (pin "10") (pinfunction "AGND_2_10") (pintype "bidirectional"))
      (node (ref "IC1") (pin "15") (pinfunction "AGND_3_15") (pintype "bidirectional"))
      (node (ref "IC1") (pin "20") (pinfunction "GND_1_20") (pintype "bidirectional"))
      (node (ref "IC1") (pin "28") (pinfunction "DGND_1_28") (pintype "bidirectional"))
      (node (ref "IC1") (pin "30") (pinfunction "DGND_2_30") (pintype "bidirectional"))
      (node (ref "IC1") (pin "38") (pinfunction "GND_2_38") (pintype "bidirectional"))
      (node (ref "IC1") (pin "5") (pinfunction "AGND_1_5") (pintype "bidirectional"))
      (node (ref "IC2") (pin "10") (pinfunction "AGND_2_10") (pintype "bidirectional"))
      (node (ref "IC2") (pin "15") (pinfunction "AGND_3_15") (pintype "bidirectional"))
      (node (ref "IC2") (pin "20") (pinfunction "GND_1_20") (pintype "bidirectional"))
      (node (ref "IC2") (pin "28") (pinfunction "DGND_1_28") (pintype "bidirectional"))
      (node (ref "IC2") (pin "30") (pinfunction "DGND_2_30") (pintype "bidirectional"))
      (node (ref "IC2") (pin "38") (pinfunction "GND_2_38") (pintype "bidirectional"))
      (node (ref "IC2") (pin "5") (pinfunction "AGND_1_5") (pintype "bidirectional"))
      (node (ref "IC3") (pin "10") (pinfunction "AGND_2_10") (pintype "bidirectional"))
      (node (ref "IC3") (pin "15") (pinfunction "AGND_3_15") (pintype "bidirectional"))
      (node (ref "IC3") (pin "20") (pinfunction "GND_1_20") (pintype "bidirectional"))
      (node (ref "IC3") (pin "28") (pinfunction "DGND_1_28") (pintype "bidirectional"))
      (node (ref "IC3") (pin "30") (pinfunction "DGND_2_30") (pintype "bidirectional"))
      (node (ref "IC3") (pin "38") (pinfunction "GND_2_38") (pintype "bidirectional"))
      (node (ref "IC3") (pin "5") (pinfunction "AGND_1_5") (pintype "bidirectional"))
      (node (ref "IC4") (pin "10") (pinfunction "AGND_2_10") (pintype "bidirectional"))
      (node (ref "IC4") (pin "15") (pinfunction "AGND_3_15") (pintype "bidirectional"))
      (node (ref "IC4") (pin "20") (pinfunction "GND_1_20") (pintype "bidirectional"))
      (node (ref "IC4") (pin "28") (pinfunction "DGND_1_28") (pintype "bidirectional"))
      (node (ref "IC4") (pin "30") (pinfunction "DGND_2_30") (pintype "bidirectional"))
      (node (ref "IC4") (pin "38") (pinfunction "GND_2_38") (pintype "bidirectional"))
      (node (ref "IC4") (pin "5") (pinfunction "AGND_1_5") (pintype "bidirectional"))
      (node (ref "IC5") (pin "10") (pinfunction "AGND_2_10") (pintype "bidirectional"))
      (node (ref "IC5") (pin "15") (pinfunction "AGND_3_15") (pintype "bidirectional"))
      (node (ref "IC5") (pin "20") (pinfunction "GND_1_20") (pintype "bidirectional"))
      (node (ref "IC5") (pin "28") (pinfunction "DGND_1_28") (pintype "bidirectional"))
      (node (ref "IC5") (pin "30") (pinfunction "DGND_2_30") (pintype "bidirectional"))
      (node (ref "IC5") (pin "38") (pinfunction "GND_2_38") (pintype "bidirectional"))
      (node (ref "IC5") (pin "5") (pinfunction "AGND_1_5") (pintype "bidirectional"))
      (node (ref "IC6") (pin "10") (pinfunction "AGND_2_10") (pintype "bidirectional"))
      (node (ref "IC6") (pin "15") (pinfunction "AGND_3_15") (pintype "bidirectional"))
      (node (ref "IC6") (pin "20") (pinfunction "GND_1_20") (pintype "bidirectional"))
      (node (ref "IC6") (pin "28") (pinfunction "DGND_1_28") (pintype "bidirectional"))
      (node (ref "IC6") (pin "30") (pinfunction "DGND_2_30") (pintype "bidirectional"))
      (node (ref "IC6") (pin "38") (pinfunction "GND_2_38") (pintype "bidirectional"))
      (node (ref "IC6") (pin "5") (pinfunction "AGND_1_5") (pintype "bidirectional"))
      (node (ref "IC7") (pin "10") (pinfunction "AGND_2_10") (pintype "bidirectional"))
      (node (ref "IC7") (pin "15") (pinfunction "AGND_3_15") (pintype "bidirectional"))
      (node (ref "IC7") (pin "20") (pinfunction "GND_1_20") (pintype "bidirectional"))
      (node (ref "IC7") (pin "28") (pinfunction "DGND_1_28") (pintype "bidirectional"))
      (node (ref "IC7") (pin "30") (pinfunction "DGND_2_30") (pintype "bidirectional"))
      (node (ref "IC7") (pin "38") (pinfunction "GND_2_38") (pintype "bidirectional"))
      (node (ref "IC7") (pin "5") (pinfunction "AGND_1_5") (pintype "bidirectional"))
      (node (ref "IC8") (pin "10") (pinfunction "AGND_2_10") (pintype "bidirectional"))
      (node (ref "IC8") (pin "15") (pinfunction "AGND_3_15") (pintype "bidirectional"))
      (node (ref "IC8") (pin "20") (pinfunction "GND_1_20") (pintype "bidirectional"))
      (node (ref "IC8") (pin "28") (pinfunction "DGND_1_28") (pintype "bidirectional"))
      (node (ref "IC8") (pin "30") (pinfunction "DGND_2_30") (pintype "bidirectional"))
      (node (ref "IC8") (pin "38") (pinfunction "GND_2_38") (pintype "bidirectional"))
      (node (ref "IC8") (pin "5") (pinfunction "AGND_1_5") (pintype "bidirectional"))
      (node (ref "IN65") (pin "2") (pinfunction "2_2") (pintype "passive"))
      (node (ref "IN65") (pin "3") (pinfunction "2_3") (pintype "passive"))
      (node (ref "IN65") (pin "4") (pinfunction "2_4") (pintype "passive"))
      (node (ref "IN65") (pin "5") (pinfunction "2_5") (pintype "passive"))
      (node (ref "IN66") (pin "2") (pinfunction "2_2") (pintype "passive"))
      (node (ref "IN66") (pin "3") (pinfunction "2_3") (pintype "passive"))
      (node (ref "IN66") (pin "4") (pinfunction "2_4") (pintype "passive"))
      (node (ref "IN66") (pin "5") (pinfunction "2_5") (pintype "passive"))
      (node (ref "IN67") (pin "2") (pinfunction "2_2") (pintype "passive"))
      (node (ref "IN67") (pin "3") (pinfunction "2_3") (pintype "passive"))
      (node (ref "IN67") (pin "4") (pinfunction "2_4") (pintype "passive"))
      (node (ref "IN67") (pin "5") (pinfunction "2_5") (pintype "passive"))
      (node (ref "IN68") (pin "2") (pinfunction "2_2") (pintype "passive"))
      (node (ref "IN68") (pin "3") (pinfunction "2_3") (pintype "passive"))
      (node (ref "IN68") (pin "4") (pinfunction "2_4") (pintype "passive"))
      (node (ref "IN68") (pin "5") (pinfunction "2_5") (pintype "passive"))
      (node (ref "IN69") (pin "2") (pinfunction "2_2") (pintype "passive"))
      (node (ref "IN69") (pin "3") (pinfunction "2_3") (pintype "passive"))
      (node (ref "IN69") (pin "4") (pinfunction "2_4") (pintype "passive"))
      (node (ref "IN69") (pin "5") (pinfunction "2_5") (pintype "passive"))
      (node (ref "IN70") (pin "2") (pinfunction "2_2") (pintype "passive"))
      (node (ref "IN70") (pin "3") (pinfunction "2_3") (pintype "passive"))
      (node (ref "IN70") (pin "4") (pinfunction "2_4") (pintype "passive"))
      (node (ref "IN70") (pin "5") (pinfunction "2_5") (pintype "passive"))
      (node (ref "IN71") (pin "2") (pinfunction "2_2") (pintype "passive"))
      (node (ref "IN71") (pin "3") (pinfunction "2_3") (pintype "passive"))
      (node (ref "IN71") (pin "4") (pinfunction "2_4") (pintype "passive"))
      (node (ref "IN71") (pin "5") (pinfunction "2_5") (pintype "passive"))
      (node (ref "IN72") (pin "2") (pinfunction "2_2") (pintype "passive"))
      (node (ref "IN72") (pin "3") (pinfunction "2_3") (pintype "passive"))
      (node (ref "IN72") (pin "4") (pinfunction "2_4") (pintype "passive"))
      (node (ref "IN72") (pin "5") (pinfunction "2_5") (pintype "passive"))
      (node (ref "IN73") (pin "2") (pinfunction "2_2") (pintype "passive"))
      (node (ref "IN73") (pin "3") (pinfunction "2_3") (pintype "passive"))
      (node (ref "IN73") (pin "4") (pinfunction "2_4") (pintype "passive"))
      (node (ref "IN73") (pin "5") (pinfunction "2_5") (pintype "passive"))
      (node (ref "IN74") (pin "2") (pinfunction "2_2") (pintype "passive"))
      (node (ref "IN74") (pin "3") (pinfunction "2_3") (pintype "passive"))
      (node (ref "IN74") (pin "4") (pinfunction "2_4") (pintype "passive"))
      (node (ref "IN74") (pin "5") (pinfunction "2_5") (pintype "passive"))
      (node (ref "IN75") (pin "2") (pinfunction "2_2") (pintype "passive"))
      (node (ref "IN75") (pin "3") (pinfunction "2_3") (pintype "passive"))
      (node (ref "IN75") (pin "4") (pinfunction "2_4") (pintype "passive"))
      (node (ref "IN75") (pin "5") (pinfunction "2_5") (pintype "passive"))
      (node (ref "IN76") (pin "2") (pinfunction "2_2") (pintype "passive"))
      (node (ref "IN76") (pin "3") (pinfunction "2_3") (pintype "passive"))
      (node (ref "IN76") (pin "4") (pinfunction "2_4") (pintype "passive"))
      (node (ref "IN76") (pin "5") (pinfunction "2_5") (pintype "passive"))
      (node (ref "IN77") (pin "2") (pinfunction "2_2") (pintype "passive"))
      (node (ref "IN77") (pin "3") (pinfunction "2_3") (pintype "passive"))
      (node (ref "IN77") (pin "4") (pinfunction "2_4") (pintype "passive"))
      (node (ref "IN77") (pin "5") (pinfunction "2_5") (pintype "passive"))
      (node (ref "IN78") (pin "2") (pinfunction "2_2") (pintype "passive"))
      (node (ref "IN78") (pin "3") (pinfunction "2_3") (pintype "passive"))
      (node (ref "IN78") (pin "4") (pinfunction "2_4") (pintype "passive"))
      (node (ref "IN78") (pin "5") (pinfunction "2_5") (pintype "passive"))
      (node (ref "IN79") (pin "2") (pinfunction "2_2") (pintype "passive"))
      (node (ref "IN79") (pin "3") (pinfunction "2_3") (pintype "passive"))
      (node (ref "IN79") (pin "4") (pinfunction "2_4") (pintype "passive"))
      (node (ref "IN79") (pin "5") (pinfunction "2_5") (pintype "passive"))
      (node (ref "IN80") (pin "2") (pinfunction "2_2") (pintype "passive"))
      (node (ref "IN80") (pin "3") (pinfunction "2_3") (pintype "passive"))
      (node (ref "IN80") (pin "4") (pinfunction "2_4") (pintype "passive"))
      (node (ref "IN80") (pin "5") (pinfunction "2_5") (pintype "passive"))
      (node (ref "J1") (pin "1") (pinfunction "1_1") (pintype "passive"))
      (node (ref "J1") (pin "3") (pinfunction "3_3") (pintype "passive"))
      (node (ref "J1") (pin "5") (pinfunction "5_5") (pintype "passive"))
      (node (ref "J1") (pin "7") (pinfunction "7_7") (pintype "passive"))
      (node (ref "J12") (pin "3") (pinfunction "P$3_3") (pintype "bidirectional"))
      (node (ref "J19") (pin "1-A9") (pinfunction "MS_1-A9") (pintype "passive"))
      (node (ref "J19") (pin "1-C9") (pinfunction "MS_1-C9") (pintype "passive"))
      (node (ref "J2") (pin "1") (pinfunction "1_1") (pintype "passive"))
      (node (ref "J2") (pin "3") (pinfunction "3_3") (pintype "passive"))
      (node (ref "J2") (pin "5") (pinfunction "5_5") (pintype "passive"))
      (node (ref "J2") (pin "7") (pinfunction "7_7") (pintype "passive"))
      (node (ref "J20") (pin "2") (pinfunction "2_2") (pintype "passive"))
      (node (ref "J20") (pin "4") (pinfunction "4_4") (pintype "passive"))
      (node (ref "J20") (pin "6") (pinfunction "6_6") (pintype "passive"))
      (node (ref "J20") (pin "8") (pinfunction "8_8") (pintype "passive"))
      (node (ref "J4") (pin "3") (pinfunction "P$3_3") (pintype "bidirectional"))
      (node (ref "J5") (pin "1") (pinfunction "1_1") (pintype "passive"))
      (node (ref "J5") (pin "3") (pinfunction "3_3") (pintype "passive"))
      (node (ref "J5") (pin "5") (pinfunction "5_5") (pintype "passive"))
      (node (ref "J5") (pin "7") (pinfunction "7_7") (pintype "passive"))
      (node (ref "J6") (pin "1") (pinfunction "1_1") (pintype "passive"))
      (node (ref "J6") (pin "3") (pinfunction "3_3") (pintype "passive"))
      (node (ref "J6") (pin "5") (pinfunction "5_5") (pintype "passive"))
      (node (ref "J6") (pin "7") (pinfunction "7_7") (pintype "passive"))
      (node (ref "OJ1") (pin "2") (pinfunction "2_2") (pintype "bidirectional"))
      (node (ref "OJ10") (pin "2") (pinfunction "2_2") (pintype "bidirectional"))
      (node (ref "OJ11") (pin "2") (pinfunction "2_2") (pintype "bidirectional"))
      (node (ref "OJ12") (pin "2") (pinfunction "2_2") (pintype "bidirectional"))
      (node (ref "OJ13") (pin "2") (pinfunction "2_2") (pintype "bidirectional"))
      (node (ref "OJ14") (pin "2") (pinfunction "2_2") (pintype "bidirectional"))
      (node (ref "OJ15") (pin "2") (pinfunction "2_2") (pintype "bidirectional"))
      (node (ref "OJ16") (pin "2") (pinfunction "2_2") (pintype "bidirectional"))
      (node (ref "OJ17") (pin "2") (pinfunction "2_2") (pintype "bidirectional"))
      (node (ref "OJ18") (pin "2") (pinfunction "2_2") (pintype "bidirectional"))
      (node (ref "OJ19") (pin "2") (pinfunction "2_2") (pintype "bidirectional"))
      (node (ref "OJ2") (pin "2") (pinfunction "2_2") (pintype "bidirectional"))
      (node (ref "OJ20") (pin "2") (pinfunction "2_2") (pintype "bidirectional"))
      (node (ref "OJ3") (pin "2") (pinfunction "2_2") (pintype "bidirectional"))
      (node (ref "OJ4") (pin "2") (pinfunction "2_2") (pintype "bidirectional"))
      (node (ref "OJ9") (pin "2") (pinfunction "2_2") (pintype "bidirectional"))
      (node (ref "OUT1") (pin "2") (pinfunction "2_2") (pintype "passive"))
      (node (ref "OUT1") (pin "3") (pinfunction "2_3") (pintype "passive"))
      (node (ref "OUT1") (pin "4") (pinfunction "2_4") (pintype "passive"))
      (node (ref "OUT1") (pin "5") (pinfunction "2_5") (pintype "passive"))
      (node (ref "OUT10") (pin "2") (pinfunction "2_2") (pintype "passive"))
      (node (ref "OUT10") (pin "3") (pinfunction "2_3") (pintype "passive"))
      (node (ref "OUT10") (pin "4") (pinfunction "2_4") (pintype "passive"))
      (node (ref "OUT10") (pin "5") (pinfunction "2_5") (pintype "passive"))
      (node (ref "OUT11") (pin "2") (pinfunction "2_2") (pintype "passive"))
      (node (ref "OUT11") (pin "3") (pinfunction "2_3") (pintype "passive"))
      (node (ref "OUT11") (pin "4") (pinfunction "2_4") (pintype "passive"))
      (node (ref "OUT11") (pin "5") (pinfunction "2_5") (pintype "passive"))
      (node (ref "OUT12") (pin "2") (pinfunction "2_2") (pintype "passive"))
      (node (ref "OUT12") (pin "3") (pinfunction "2_3") (pintype "passive"))
      (node (ref "OUT12") (pin "4") (pinfunction "2_4") (pintype "passive"))
      (node (ref "OUT12") (pin "5") (pinfunction "2_5") (pintype "passive"))
      (node (ref "OUT13") (pin "2") (pinfunction "2_2") (pintype "passive"))
      (node (ref "OUT13") (pin "3") (pinfunction "2_3") (pintype "passive"))
      (node (ref "OUT13") (pin "4") (pinfunction "2_4") (pintype "passive"))
      (node (ref "OUT13") (pin "5") (pinfunction "2_5") (pintype "passive"))
      (node (ref "OUT14") (pin "2") (pinfunction "2_2") (pintype "passive"))
      (node (ref "OUT14") (pin "3") (pinfunction "2_3") (pintype "passive"))
      (node (ref "OUT14") (pin "4") (pinfunction "2_4") (pintype "passive"))
      (node (ref "OUT14") (pin "5") (pinfunction "2_5") (pintype "passive"))
      (node (ref "OUT15") (pin "2") (pinfunction "2_2") (pintype "passive"))
      (node (ref "OUT15") (pin "3") (pinfunction "2_3") (pintype "passive"))
      (node (ref "OUT15") (pin "4") (pinfunction "2_4") (pintype "passive"))
      (node (ref "OUT15") (pin "5") (pinfunction "2_5") (pintype "passive"))
      (node (ref "OUT16") (pin "2") (pinfunction "2_2") (pintype "passive"))
      (node (ref "OUT16") (pin "3") (pinfunction "2_3") (pintype "passive"))
      (node (ref "OUT16") (pin "4") (pinfunction "2_4") (pintype "passive"))
      (node (ref "OUT16") (pin "5") (pinfunction "2_5") (pintype "passive"))
      (node (ref "OUT17") (pin "2") (pinfunction "2_2") (pintype "passive"))
      (node (ref "OUT17") (pin "3") (pinfunction "2_3") (pintype "passive"))
      (node (ref "OUT17") (pin "4") (pinfunction "2_4") (pintype "passive"))
      (node (ref "OUT17") (pin "5") (pinfunction "2_5") (pintype "passive"))
      (node (ref "OUT18") (pin "2") (pinfunction "2_2") (pintype "passive"))
      (node (ref "OUT18") (pin "3") (pinfunction "2_3") (pintype "passive"))
      (node (ref "OUT18") (pin "4") (pinfunction "2_4") (pintype "passive"))
      (node (ref "OUT18") (pin "5") (pinfunction "2_5") (pintype "passive"))
      (node (ref "OUT19") (pin "2") (pinfunction "2_2") (pintype "passive"))
      (node (ref "OUT19") (pin "3") (pinfunction "2_3") (pintype "passive"))
      (node (ref "OUT19") (pin "4") (pinfunction "2_4") (pintype "passive"))
      (node (ref "OUT19") (pin "5") (pinfunction "2_5") (pintype "passive"))
      (node (ref "OUT2") (pin "2") (pinfunction "2_2") (pintype "passive"))
      (node (ref "OUT2") (pin "3") (pinfunction "2_3") (pintype "passive"))
      (node (ref "OUT2") (pin "4") (pinfunction "2_4") (pintype "passive"))
      (node (ref "OUT2") (pin "5") (pinfunction "2_5") (pintype "passive"))
      (node (ref "OUT20") (pin "2") (pinfunction "2_2") (pintype "passive"))
      (node (ref "OUT20") (pin "3") (pinfunction "2_3") (pintype "passive"))
      (node (ref "OUT20") (pin "4") (pinfunction "2_4") (pintype "passive"))
      (node (ref "OUT20") (pin "5") (pinfunction "2_5") (pintype "passive"))
      (node (ref "OUT21") (pin "2") (pinfunction "2_2") (pintype "passive"))
      (node (ref "OUT21") (pin "3") (pinfunction "2_3") (pintype "passive"))
      (node (ref "OUT21") (pin "4") (pinfunction "2_4") (pintype "passive"))
      (node (ref "OUT21") (pin "5") (pinfunction "2_5") (pintype "passive"))
      (node (ref "OUT22") (pin "2") (pinfunction "2_2") (pintype "passive"))
      (node (ref "OUT22") (pin "3") (pinfunction "2_3") (pintype "passive"))
      (node (ref "OUT22") (pin "4") (pinfunction "2_4") (pintype "passive"))
      (node (ref "OUT22") (pin "5") (pinfunction "2_5") (pintype "passive"))
      (node (ref "OUT23") (pin "2") (pinfunction "2_2") (pintype "passive"))
      (node (ref "OUT23") (pin "3") (pinfunction "2_3") (pintype "passive"))
      (node (ref "OUT23") (pin "4") (pinfunction "2_4") (pintype "passive"))
      (node (ref "OUT23") (pin "5") (pinfunction "2_5") (pintype "passive"))
      (node (ref "OUT24") (pin "2") (pinfunction "2_2") (pintype "passive"))
      (node (ref "OUT24") (pin "3") (pinfunction "2_3") (pintype "passive"))
      (node (ref "OUT24") (pin "4") (pinfunction "2_4") (pintype "passive"))
      (node (ref "OUT24") (pin "5") (pinfunction "2_5") (pintype "passive"))
      (node (ref "OUT25") (pin "2") (pinfunction "2_2") (pintype "passive"))
      (node (ref "OUT25") (pin "3") (pinfunction "2_3") (pintype "passive"))
      (node (ref "OUT25") (pin "4") (pinfunction "2_4") (pintype "passive"))
      (node (ref "OUT25") (pin "5") (pinfunction "2_5") (pintype "passive"))
      (node (ref "OUT26") (pin "2") (pinfunction "2_2") (pintype "passive"))
      (node (ref "OUT26") (pin "3") (pinfunction "2_3") (pintype "passive"))
      (node (ref "OUT26") (pin "4") (pinfunction "2_4") (pintype "passive"))
      (node (ref "OUT26") (pin "5") (pinfunction "2_5") (pintype "passive"))
      (node (ref "OUT27") (pin "2") (pinfunction "2_2") (pintype "passive"))
      (node (ref "OUT27") (pin "3") (pinfunction "2_3") (pintype "passive"))
      (node (ref "OUT27") (pin "4") (pinfunction "2_4") (pintype "passive"))
      (node (ref "OUT27") (pin "5") (pinfunction "2_5") (pintype "passive"))
      (node (ref "OUT28") (pin "2") (pinfunction "2_2") (pintype "passive"))
      (node (ref "OUT28") (pin "3") (pinfunction "2_3") (pintype "passive"))
      (node (ref "OUT28") (pin "4") (pinfunction "2_4") (pintype "passive"))
      (node (ref "OUT28") (pin "5") (pinfunction "2_5") (pintype "passive"))
      (node (ref "OUT29") (pin "2") (pinfunction "2_2") (pintype "passive"))
      (node (ref "OUT29") (pin "3") (pinfunction "2_3") (pintype "passive"))
      (node (ref "OUT29") (pin "4") (pinfunction "2_4") (pintype "passive"))
      (node (ref "OUT29") (pin "5") (pinfunction "2_5") (pintype "passive"))
      (node (ref "OUT3") (pin "2") (pinfunction "2_2") (pintype "passive"))
      (node (ref "OUT3") (pin "3") (pinfunction "2_3") (pintype "passive"))
      (node (ref "OUT3") (pin "4") (pinfunction "2_4") (pintype "passive"))
      (node (ref "OUT3") (pin "5") (pinfunction "2_5") (pintype "passive"))
      (node (ref "OUT30") (pin "2") (pinfunction "2_2") (pintype "passive"))
      (node (ref "OUT30") (pin "3") (pinfunction "2_3") (pintype "passive"))
      (node (ref "OUT30") (pin "4") (pinfunction "2_4") (pintype "passive"))
      (node (ref "OUT30") (pin "5") (pinfunction "2_5") (pintype "passive"))
      (node (ref "OUT31") (pin "2") (pinfunction "2_2") (pintype "passive"))
      (node (ref "OUT31") (pin "3") (pinfunction "2_3") (pintype "passive"))
      (node (ref "OUT31") (pin "4") (pinfunction "2_4") (pintype "passive"))
      (node (ref "OUT31") (pin "5") (pinfunction "2_5") (pintype "passive"))
      (node (ref "OUT32") (pin "2") (pinfunction "2_2") (pintype "passive"))
      (node (ref "OUT32") (pin "3") (pinfunction "2_3") (pintype "passive"))
      (node (ref "OUT32") (pin "4") (pinfunction "2_4") (pintype "passive"))
      (node (ref "OUT32") (pin "5") (pinfunction "2_5") (pintype "passive"))
      (node (ref "OUT4") (pin "2") (pinfunction "2_2") (pintype "passive"))
      (node (ref "OUT4") (pin "3") (pinfunction "2_3") (pintype "passive"))
      (node (ref "OUT4") (pin "4") (pinfunction "2_4") (pintype "passive"))
      (node (ref "OUT4") (pin "5") (pinfunction "2_5") (pintype "passive"))
      (node (ref "OUT5") (pin "2") (pinfunction "2_2") (pintype "passive"))
      (node (ref "OUT5") (pin "3") (pinfunction "2_3") (pintype "passive"))
      (node (ref "OUT5") (pin "4") (pinfunction "2_4") (pintype "passive"))
      (node (ref "OUT5") (pin "5") (pinfunction "2_5") (pintype "passive"))
      (node (ref "OUT6") (pin "2") (pinfunction "2_2") (pintype "passive"))
      (node (ref "OUT6") (pin "3") (pinfunction "2_3") (pintype "passive"))
      (node (ref "OUT6") (pin "4") (pinfunction "2_4") (pintype "passive"))
      (node (ref "OUT6") (pin "5") (pinfunction "2_5") (pintype "passive"))
      (node (ref "OUT7") (pin "2") (pinfunction "2_2") (pintype "passive"))
      (node (ref "OUT7") (pin "3") (pinfunction "2_3") (pintype "passive"))
      (node (ref "OUT7") (pin "4") (pinfunction "2_4") (pintype "passive"))
      (node (ref "OUT7") (pin "5") (pinfunction "2_5") (pintype "passive"))
      (node (ref "OUT8") (pin "2") (pinfunction "2_2") (pintype "passive"))
      (node (ref "OUT8") (pin "3") (pinfunction "2_3") (pintype "passive"))
      (node (ref "OUT8") (pin "4") (pinfunction "2_4") (pintype "passive"))
      (node (ref "OUT8") (pin "5") (pinfunction "2_5") (pintype "passive"))
      (node (ref "OUT9") (pin "2") (pinfunction "2_2") (pintype "passive"))
      (node (ref "OUT9") (pin "3") (pinfunction "2_3") (pintype "passive"))
      (node (ref "OUT9") (pin "4") (pinfunction "2_4") (pintype "passive"))
      (node (ref "OUT9") (pin "5") (pinfunction "2_5") (pintype "passive"))
      (node (ref "R10") (pin "P$1") (pinfunction "1_P$1") (pintype "passive"))
      (node (ref "R11") (pin "P$1") (pinfunction "1_P$1") (pintype "passive"))
      (node (ref "R12") (pin "P$1") (pinfunction "1_P$1") (pintype "passive"))
      (node (ref "R13") (pin "P$1") (pinfunction "1_P$1") (pintype "passive"))
      (node (ref "R14") (pin "P$1") (pinfunction "1_P$1") (pintype "passive"))
      (node (ref "R17") (pin "P$1") (pinfunction "1_P$1") (pintype "passive"))
      (node (ref "R18") (pin "P$1") (pinfunction "1_P$1") (pintype "passive"))
      (node (ref "R19") (pin "P$1") (pinfunction "1_P$1") (pintype "passive"))
      (node (ref "R2") (pin "P$1") (pinfunction "1_P$1") (pintype "passive"))
      (node (ref "R20") (pin "P$1") (pinfunction "1_P$1") (pintype "passive"))
      (node (ref "R3") (pin "P$1") (pinfunction "1_P$1") (pintype "passive"))
      (node (ref "R4") (pin "P$1") (pinfunction "1_P$1") (pintype "passive"))
      (node (ref "R5") (pin "P$1") (pinfunction "1_P$1") (pintype "passive"))
      (node (ref "R6") (pin "P$1") (pinfunction "1_P$1") (pintype "passive"))
      (node (ref "R7") (pin "P$1") (pinfunction "1_P$1") (pintype "passive"))
      (node (ref "R8") (pin "2") (pinfunction "2_2") (pintype "passive"))
      (node (ref "R9") (pin "P$1") (pinfunction "1_P$1") (pintype "passive"))
      (node (ref "REG") (pin "1") (pinfunction "GND_1") (pintype "bidirectional"))
      (node (ref "RLEDPOW") (pin "2") (pinfunction "2_2") (pintype "passive"))
      (node (ref "VSLUE") (pin "10") (pinfunction "GND_10") (pintype "power_in"))
      (node (ref "VSLUE2") (pin "10") (pinfunction "GND_10") (pintype "power_in"))
      (node (ref "VSLUE3") (pin "10") (pinfunction "GND_10") (pintype "power_in"))
      (node (ref "VSLUE4") (pin "10") (pinfunction "GND_10") (pintype "power_in"))
      (node (ref "X13") (pin "2") (pinfunction "S_2") (pintype "passive"))
      (node (ref "X13") (pin "24") (pinfunction "S_24") (pintype "passive"))
      (node (ref "X18") (pin "1") (pinfunction "S_1") (pintype "passive"))
      (node (ref "X18") (pin "23") (pinfunction "S_23") (pintype "passive"))
    )
    (net (code "158") (name "Net-(IC1-A1A)") (class "Default")
      (node (ref "IC1") (pin "1") (pinfunction "A1A_1") (pintype "bidirectional"))
      (node (ref "JP1") (pin "1") (pinfunction "1_1") (pintype "passive"))
    )
    (net (code "159") (name "Net-(IC1-A1B)") (class "Default")
      (node (ref "IC1") (pin "2") (pinfunction "A1B_2") (pintype "bidirectional"))
      (node (ref "JP1") (pin "2") (pinfunction "2_2") (pintype "passive"))
    )
    (net (code "160") (name "Net-(IC1-A2A)") (class "Default")
      (node (ref "IC1") (pin "3") (pinfunction "A2A_3") (pintype "bidirectional"))
      (node (ref "JP1") (pin "3") (pinfunction "3_3") (pintype "passive"))
    )
    (net (code "161") (name "Net-(IC1-A2B)") (class "Default")
      (node (ref "IC1") (pin "4") (pinfunction "A2B_4") (pintype "bidirectional"))
      (node (ref "JP1") (pin "4") (pinfunction "4_4") (pintype "passive"))
    )
    (net (code "162") (name "Net-(IC1-B1A)") (class "Default")
      (node (ref "IC1") (pin "6") (pinfunction "B1A_6") (pintype "bidirectional"))
      (node (ref "JP1") (pin "5") (pinfunction "5_5") (pintype "passive"))
    )
    (net (code "163") (name "Net-(IC1-B1B)") (class "Default")
      (node (ref "IC1") (pin "7") (pinfunction "B1B_7") (pintype "bidirectional"))
      (node (ref "JP1") (pin "6") (pinfunction "6_6") (pintype "passive"))
    )
    (net (code "164") (name "Net-(IC1-B2A)") (class "Default")
      (node (ref "IC1") (pin "8") (pinfunction "B2A_8") (pintype "bidirectional"))
      (node (ref "JP1") (pin "7") (pinfunction "7_7") (pintype "passive"))
    )
    (net (code "165") (name "Net-(IC1-B2B)") (class "Default")
      (node (ref "IC1") (pin "9") (pinfunction "B2B_9") (pintype "bidirectional"))
      (node (ref "JP1") (pin "8") (pinfunction "8_8") (pintype "passive"))
    )
    (net (code "166") (name "Net-(IC1-C1A)") (class "Default")
      (node (ref "IC1") (pin "11") (pinfunction "C1A_11") (pintype "bidirectional"))
      (node (ref "JP1") (pin "9") (pinfunction "9_9") (pintype "passive"))
    )
    (net (code "167") (name "Net-(IC1-C1B)") (class "Default")
      (node (ref "IC1") (pin "12") (pinfunction "C1B_12") (pintype "bidirectional"))
      (node (ref "JP1") (pin "10") (pinfunction "10_10") (pintype "passive"))
    )
    (net (code "168") (name "Net-(IC1-C2A)") (class "Default")
      (node (ref "IC1") (pin "13") (pinfunction "C2A_13") (pintype "bidirectional"))
      (node (ref "JP1") (pin "11") (pinfunction "11_11") (pintype "passive"))
    )
    (net (code "169") (name "Net-(IC1-C2B)") (class "Default")
      (node (ref "IC1") (pin "14") (pinfunction "C2B_14") (pintype "bidirectional"))
      (node (ref "JP1") (pin "12") (pinfunction "12_12") (pintype "passive"))
    )
    (net (code "170") (name "Net-(IC1-D1A)") (class "Default")
      (node (ref "IC1") (pin "16") (pinfunction "D1A_16") (pintype "bidirectional"))
      (node (ref "JP1") (pin "13") (pinfunction "13_13") (pintype "passive"))
    )
    (net (code "171") (name "Net-(IC1-D1B)") (class "Default")
      (node (ref "IC1") (pin "17") (pinfunction "D1B_17") (pintype "bidirectional"))
      (node (ref "JP1") (pin "14") (pinfunction "14_14") (pintype "passive"))
    )
    (net (code "172") (name "Net-(IC1-D2A)") (class "Default")
      (node (ref "IC1") (pin "18") (pinfunction "D2A_18") (pintype "bidirectional"))
      (node (ref "JP1") (pin "15") (pinfunction "15_15") (pintype "passive"))
    )
    (net (code "173") (name "Net-(IC1-D2B)") (class "Default")
      (node (ref "IC1") (pin "19") (pinfunction "D2B_19") (pintype "bidirectional"))
      (node (ref "JP1") (pin "16") (pinfunction "16_16") (pintype "passive"))
    )
    (net (code "174") (name "Net-(IC2-A1A)") (class "Default")
      (node (ref "IC2") (pin "1") (pinfunction "A1A_1") (pintype "bidirectional"))
      (node (ref "JP2") (pin "1") (pinfunction "1_1") (pintype "passive"))
    )
    (net (code "175") (name "Net-(IC2-A1B)") (class "Default")
      (node (ref "IC2") (pin "2") (pinfunction "A1B_2") (pintype "bidirectional"))
      (node (ref "JP2") (pin "2") (pinfunction "2_2") (pintype "passive"))
    )
    (net (code "176") (name "Net-(IC2-A2A)") (class "Default")
      (node (ref "IC2") (pin "3") (pinfunction "A2A_3") (pintype "bidirectional"))
      (node (ref "JP2") (pin "3") (pinfunction "3_3") (pintype "passive"))
    )
    (net (code "177") (name "Net-(IC2-A2B)") (class "Default")
      (node (ref "IC2") (pin "4") (pinfunction "A2B_4") (pintype "bidirectional"))
      (node (ref "JP2") (pin "4") (pinfunction "4_4") (pintype "passive"))
    )
    (net (code "178") (name "Net-(IC2-B1A)") (class "Default")
      (node (ref "IC2") (pin "6") (pinfunction "B1A_6") (pintype "bidirectional"))
      (node (ref "JP2") (pin "5") (pinfunction "5_5") (pintype "passive"))
    )
    (net (code "179") (name "Net-(IC2-B1B)") (class "Default")
      (node (ref "IC2") (pin "7") (pinfunction "B1B_7") (pintype "bidirectional"))
      (node (ref "JP2") (pin "6") (pinfunction "6_6") (pintype "passive"))
    )
    (net (code "180") (name "Net-(IC2-B2A)") (class "Default")
      (node (ref "IC2") (pin "8") (pinfunction "B2A_8") (pintype "bidirectional"))
      (node (ref "JP2") (pin "7") (pinfunction "7_7") (pintype "passive"))
    )
    (net (code "181") (name "Net-(IC2-B2B)") (class "Default")
      (node (ref "IC2") (pin "9") (pinfunction "B2B_9") (pintype "bidirectional"))
      (node (ref "JP2") (pin "8") (pinfunction "8_8") (pintype "passive"))
    )
    (net (code "182") (name "Net-(IC2-C1A)") (class "Default")
      (node (ref "IC2") (pin "11") (pinfunction "C1A_11") (pintype "bidirectional"))
      (node (ref "JP2") (pin "9") (pinfunction "9_9") (pintype "passive"))
    )
    (net (code "183") (name "Net-(IC2-C1B)") (class "Default")
      (node (ref "IC2") (pin "12") (pinfunction "C1B_12") (pintype "bidirectional"))
      (node (ref "JP2") (pin "10") (pinfunction "10_10") (pintype "passive"))
    )
    (net (code "184") (name "Net-(IC2-C2A)") (class "Default")
      (node (ref "IC2") (pin "13") (pinfunction "C2A_13") (pintype "bidirectional"))
      (node (ref "JP2") (pin "11") (pinfunction "11_11") (pintype "passive"))
    )
    (net (code "185") (name "Net-(IC2-C2B)") (class "Default")
      (node (ref "IC2") (pin "14") (pinfunction "C2B_14") (pintype "bidirectional"))
      (node (ref "JP2") (pin "12") (pinfunction "12_12") (pintype "passive"))
    )
    (net (code "186") (name "Net-(IC2-D1A)") (class "Default")
      (node (ref "IC2") (pin "16") (pinfunction "D1A_16") (pintype "bidirectional"))
      (node (ref "JP2") (pin "13") (pinfunction "13_13") (pintype "passive"))
    )
    (net (code "187") (name "Net-(IC2-D1B)") (class "Default")
      (node (ref "IC2") (pin "17") (pinfunction "D1B_17") (pintype "bidirectional"))
      (node (ref "JP2") (pin "14") (pinfunction "14_14") (pintype "passive"))
    )
    (net (code "188") (name "Net-(IC2-D2A)") (class "Default")
      (node (ref "IC2") (pin "18") (pinfunction "D2A_18") (pintype "bidirectional"))
      (node (ref "JP2") (pin "15") (pinfunction "15_15") (pintype "passive"))
    )
    (net (code "189") (name "Net-(IC2-D2B)") (class "Default")
      (node (ref "IC2") (pin "19") (pinfunction "D2B_19") (pintype "bidirectional"))
      (node (ref "JP2") (pin "16") (pinfunction "16_16") (pintype "passive"))
    )
    (net (code "190") (name "Net-(IC3-A1A)") (class "Default")
      (node (ref "IC3") (pin "1") (pinfunction "A1A_1") (pintype "bidirectional"))
      (node (ref "JP3") (pin "1") (pinfunction "1_1") (pintype "passive"))
    )
    (net (code "191") (name "Net-(IC3-A1B)") (class "Default")
      (node (ref "IC3") (pin "2") (pinfunction "A1B_2") (pintype "bidirectional"))
      (node (ref "JP3") (pin "2") (pinfunction "2_2") (pintype "passive"))
    )
    (net (code "192") (name "Net-(IC3-A2A)") (class "Default")
      (node (ref "IC3") (pin "3") (pinfunction "A2A_3") (pintype "bidirectional"))
      (node (ref "JP3") (pin "3") (pinfunction "3_3") (pintype "passive"))
    )
    (net (code "193") (name "Net-(IC3-A2B)") (class "Default")
      (node (ref "IC3") (pin "4") (pinfunction "A2B_4") (pintype "bidirectional"))
      (node (ref "JP3") (pin "4") (pinfunction "4_4") (pintype "passive"))
    )
    (net (code "194") (name "Net-(IC3-B1A)") (class "Default")
      (node (ref "IC3") (pin "6") (pinfunction "B1A_6") (pintype "bidirectional"))
      (node (ref "JP3") (pin "5") (pinfunction "5_5") (pintype "passive"))
    )
    (net (code "195") (name "Net-(IC3-B1B)") (class "Default")
      (node (ref "IC3") (pin "7") (pinfunction "B1B_7") (pintype "bidirectional"))
      (node (ref "JP3") (pin "6") (pinfunction "6_6") (pintype "passive"))
    )
    (net (code "196") (name "Net-(IC3-B2A)") (class "Default")
      (node (ref "IC3") (pin "8") (pinfunction "B2A_8") (pintype "bidirectional"))
      (node (ref "JP3") (pin "7") (pinfunction "7_7") (pintype "passive"))
    )
    (net (code "197") (name "Net-(IC3-B2B)") (class "Default")
      (node (ref "IC3") (pin "9") (pinfunction "B2B_9") (pintype "bidirectional"))
      (node (ref "JP3") (pin "8") (pinfunction "8_8") (pintype "passive"))
    )
    (net (code "198") (name "Net-(IC3-C1A)") (class "Default")
      (node (ref "IC3") (pin "11") (pinfunction "C1A_11") (pintype "bidirectional"))
      (node (ref "JP3") (pin "9") (pinfunction "9_9") (pintype "passive"))
    )
    (net (code "199") (name "Net-(IC3-C1B)") (class "Default")
      (node (ref "IC3") (pin "12") (pinfunction "C1B_12") (pintype "bidirectional"))
      (node (ref "JP3") (pin "10") (pinfunction "10_10") (pintype "passive"))
    )
    (net (code "200") (name "Net-(IC3-C2A)") (class "Default")
      (node (ref "IC3") (pin "13") (pinfunction "C2A_13") (pintype "bidirectional"))
      (node (ref "JP3") (pin "11") (pinfunction "11_11") (pintype "passive"))
    )
    (net (code "201") (name "Net-(IC3-C2B)") (class "Default")
      (node (ref "IC3") (pin "14") (pinfunction "C2B_14") (pintype "bidirectional"))
      (node (ref "JP3") (pin "12") (pinfunction "12_12") (pintype "passive"))
    )
    (net (code "202") (name "Net-(IC3-D1A)") (class "Default")
      (node (ref "IC3") (pin "16") (pinfunction "D1A_16") (pintype "bidirectional"))
      (node (ref "JP3") (pin "13") (pinfunction "13_13") (pintype "passive"))
    )
    (net (code "203") (name "Net-(IC3-D1B)") (class "Default")
      (node (ref "IC3") (pin "17") (pinfunction "D1B_17") (pintype "bidirectional"))
      (node (ref "JP3") (pin "14") (pinfunction "14_14") (pintype "passive"))
    )
    (net (code "204") (name "Net-(IC3-D2A)") (class "Default")
      (node (ref "IC3") (pin "18") (pinfunction "D2A_18") (pintype "bidirectional"))
      (node (ref "JP3") (pin "15") (pinfunction "15_15") (pintype "passive"))
    )
    (net (code "205") (name "Net-(IC3-D2B)") (class "Default")
      (node (ref "IC3") (pin "19") (pinfunction "D2B_19") (pintype "bidirectional"))
      (node (ref "JP3") (pin "16") (pinfunction "16_16") (pintype "passive"))
    )
    (net (code "206") (name "Net-(IC4-A1A)") (class "Default")
      (node (ref "IC4") (pin "1") (pinfunction "A1A_1") (pintype "bidirectional"))
      (node (ref "JP4") (pin "1") (pinfunction "1_1") (pintype "passive"))
    )
    (net (code "207") (name "Net-(IC4-A1B)") (class "Default")
      (node (ref "IC4") (pin "2") (pinfunction "A1B_2") (pintype "bidirectional"))
      (node (ref "JP4") (pin "2") (pinfunction "2_2") (pintype "passive"))
    )
    (net (code "208") (name "Net-(IC4-A2A)") (class "Default")
      (node (ref "IC4") (pin "3") (pinfunction "A2A_3") (pintype "bidirectional"))
      (node (ref "JP4") (pin "3") (pinfunction "3_3") (pintype "passive"))
    )
    (net (code "209") (name "Net-(IC4-A2B)") (class "Default")
      (node (ref "IC4") (pin "4") (pinfunction "A2B_4") (pintype "bidirectional"))
      (node (ref "JP4") (pin "4") (pinfunction "4_4") (pintype "passive"))
    )
    (net (code "210") (name "Net-(IC4-B1A)") (class "Default")
      (node (ref "IC4") (pin "6") (pinfunction "B1A_6") (pintype "bidirectional"))
      (node (ref "JP4") (pin "5") (pinfunction "5_5") (pintype "passive"))
    )
    (net (code "211") (name "Net-(IC4-B1B)") (class "Default")
      (node (ref "IC4") (pin "7") (pinfunction "B1B_7") (pintype "bidirectional"))
      (node (ref "JP4") (pin "6") (pinfunction "6_6") (pintype "passive"))
    )
    (net (code "212") (name "Net-(IC4-B2A)") (class "Default")
      (node (ref "IC4") (pin "8") (pinfunction "B2A_8") (pintype "bidirectional"))
      (node (ref "JP4") (pin "7") (pinfunction "7_7") (pintype "passive"))
    )
    (net (code "213") (name "Net-(IC4-B2B)") (class "Default")
      (node (ref "IC4") (pin "9") (pinfunction "B2B_9") (pintype "bidirectional"))
      (node (ref "JP4") (pin "8") (pinfunction "8_8") (pintype "passive"))
    )
    (net (code "214") (name "Net-(IC4-C1A)") (class "Default")
      (node (ref "IC4") (pin "11") (pinfunction "C1A_11") (pintype "bidirectional"))
      (node (ref "JP4") (pin "9") (pinfunction "9_9") (pintype "passive"))
    )
    (net (code "215") (name "Net-(IC4-C1B)") (class "Default")
      (node (ref "IC4") (pin "12") (pinfunction "C1B_12") (pintype "bidirectional"))
      (node (ref "JP4") (pin "10") (pinfunction "10_10") (pintype "passive"))
    )
    (net (code "216") (name "Net-(IC4-C2A)") (class "Default")
      (node (ref "IC4") (pin "13") (pinfunction "C2A_13") (pintype "bidirectional"))
      (node (ref "JP4") (pin "11") (pinfunction "11_11") (pintype "passive"))
    )
    (net (code "217") (name "Net-(IC4-C2B)") (class "Default")
      (node (ref "IC4") (pin "14") (pinfunction "C2B_14") (pintype "bidirectional"))
      (node (ref "JP4") (pin "12") (pinfunction "12_12") (pintype "passive"))
    )
    (net (code "218") (name "Net-(IC4-D1A)") (class "Default")
      (node (ref "IC4") (pin "16") (pinfunction "D1A_16") (pintype "bidirectional"))
      (node (ref "JP4") (pin "13") (pinfunction "13_13") (pintype "passive"))
    )
    (net (code "219") (name "Net-(IC4-D1B)") (class "Default")
      (node (ref "IC4") (pin "17") (pinfunction "D1B_17") (pintype "bidirectional"))
      (node (ref "JP4") (pin "14") (pinfunction "14_14") (pintype "passive"))
    )
    (net (code "220") (name "Net-(IC4-D2A)") (class "Default")
      (node (ref "IC4") (pin "18") (pinfunction "D2A_18") (pintype "bidirectional"))
      (node (ref "JP4") (pin "15") (pinfunction "15_15") (pintype "passive"))
    )
    (net (code "221") (name "Net-(IC4-D2B)") (class "Default")
      (node (ref "IC4") (pin "19") (pinfunction "D2B_19") (pintype "bidirectional"))
      (node (ref "JP4") (pin "16") (pinfunction "16_16") (pintype "passive"))
    )
    (net (code "222") (name "Net-(IC5-A1A)") (class "Default")
      (node (ref "IC5") (pin "1") (pinfunction "A1A_1") (pintype "bidirectional"))
      (node (ref "JP5") (pin "1") (pinfunction "1_1") (pintype "passive"))
    )
    (net (code "223") (name "Net-(IC5-A1B)") (class "Default")
      (node (ref "IC5") (pin "2") (pinfunction "A1B_2") (pintype "bidirectional"))
      (node (ref "JP5") (pin "2") (pinfunction "2_2") (pintype "passive"))
    )
    (net (code "224") (name "Net-(IC5-A2A)") (class "Default")
      (node (ref "IC5") (pin "3") (pinfunction "A2A_3") (pintype "bidirectional"))
      (node (ref "JP5") (pin "3") (pinfunction "3_3") (pintype "passive"))
    )
    (net (code "225") (name "Net-(IC5-A2B)") (class "Default")
      (node (ref "IC5") (pin "4") (pinfunction "A2B_4") (pintype "bidirectional"))
      (node (ref "JP5") (pin "4") (pinfunction "4_4") (pintype "passive"))
    )
    (net (code "226") (name "Net-(IC5-B1A)") (class "Default")
      (node (ref "IC5") (pin "6") (pinfunction "B1A_6") (pintype "bidirectional"))
      (node (ref "JP5") (pin "5") (pinfunction "5_5") (pintype "passive"))
    )
    (net (code "227") (name "Net-(IC5-B1B)") (class "Default")
      (node (ref "IC5") (pin "7") (pinfunction "B1B_7") (pintype "bidirectional"))
      (node (ref "JP5") (pin "6") (pinfunction "6_6") (pintype "passive"))
    )
    (net (code "228") (name "Net-(IC5-B2A)") (class "Default")
      (node (ref "IC5") (pin "8") (pinfunction "B2A_8") (pintype "bidirectional"))
      (node (ref "JP5") (pin "7") (pinfunction "7_7") (pintype "passive"))
    )
    (net (code "229") (name "Net-(IC5-B2B)") (class "Default")
      (node (ref "IC5") (pin "9") (pinfunction "B2B_9") (pintype "bidirectional"))
      (node (ref "JP5") (pin "8") (pinfunction "8_8") (pintype "passive"))
    )
    (net (code "230") (name "Net-(IC5-C1A)") (class "Default")
      (node (ref "IC5") (pin "11") (pinfunction "C1A_11") (pintype "bidirectional"))
      (node (ref "JP5") (pin "9") (pinfunction "9_9") (pintype "passive"))
    )
    (net (code "231") (name "Net-(IC5-C1B)") (class "Default")
      (node (ref "IC5") (pin "12") (pinfunction "C1B_12") (pintype "bidirectional"))
      (node (ref "JP5") (pin "10") (pinfunction "10_10") (pintype "passive"))
    )
    (net (code "232") (name "Net-(IC5-C2A)") (class "Default")
      (node (ref "IC5") (pin "13") (pinfunction "C2A_13") (pintype "bidirectional"))
      (node (ref "JP5") (pin "11") (pinfunction "11_11") (pintype "passive"))
    )
    (net (code "233") (name "Net-(IC5-C2B)") (class "Default")
      (node (ref "IC5") (pin "14") (pinfunction "C2B_14") (pintype "bidirectional"))
      (node (ref "JP5") (pin "12") (pinfunction "12_12") (pintype "passive"))
    )
    (net (code "234") (name "Net-(IC5-D1A)") (class "Default")
      (node (ref "IC5") (pin "16") (pinfunction "D1A_16") (pintype "bidirectional"))
      (node (ref "JP5") (pin "13") (pinfunction "13_13") (pintype "passive"))
    )
    (net (code "235") (name "Net-(IC5-D1B)") (class "Default")
      (node (ref "IC5") (pin "17") (pinfunction "D1B_17") (pintype "bidirectional"))
      (node (ref "JP5") (pin "14") (pinfunction "14_14") (pintype "passive"))
    )
    (net (code "236") (name "Net-(IC5-D2A)") (class "Default")
      (node (ref "IC5") (pin "18") (pinfunction "D2A_18") (pintype "bidirectional"))
      (node (ref "JP5") (pin "15") (pinfunction "15_15") (pintype "passive"))
    )
    (net (code "237") (name "Net-(IC5-D2B)") (class "Default")
      (node (ref "IC5") (pin "19") (pinfunction "D2B_19") (pintype "bidirectional"))
      (node (ref "JP5") (pin "16") (pinfunction "16_16") (pintype "passive"))
    )
    (net (code "238") (name "Net-(IC6-A1A)") (class "Default")
      (node (ref "IC6") (pin "1") (pinfunction "A1A_1") (pintype "bidirectional"))
      (node (ref "JP6") (pin "1") (pinfunction "1_1") (pintype "passive"))
    )
    (net (code "239") (name "Net-(IC6-A1B)") (class "Default")
      (node (ref "IC6") (pin "2") (pinfunction "A1B_2") (pintype "bidirectional"))
      (node (ref "JP6") (pin "2") (pinfunction "2_2") (pintype "passive"))
    )
    (net (code "240") (name "Net-(IC6-A2A)") (class "Default")
      (node (ref "IC6") (pin "3") (pinfunction "A2A_3") (pintype "bidirectional"))
      (node (ref "JP6") (pin "3") (pinfunction "3_3") (pintype "passive"))
    )
    (net (code "241") (name "Net-(IC6-A2B)") (class "Default")
      (node (ref "IC6") (pin "4") (pinfunction "A2B_4") (pintype "bidirectional"))
      (node (ref "JP6") (pin "4") (pinfunction "4_4") (pintype "passive"))
    )
    (net (code "242") (name "Net-(IC6-B1A)") (class "Default")
      (node (ref "IC6") (pin "6") (pinfunction "B1A_6") (pintype "bidirectional"))
      (node (ref "JP6") (pin "5") (pinfunction "5_5") (pintype "passive"))
    )
    (net (code "243") (name "Net-(IC6-B1B)") (class "Default")
      (node (ref "IC6") (pin "7") (pinfunction "B1B_7") (pintype "bidirectional"))
      (node (ref "JP6") (pin "6") (pinfunction "6_6") (pintype "passive"))
    )
    (net (code "244") (name "Net-(IC6-B2A)") (class "Default")
      (node (ref "IC6") (pin "8") (pinfunction "B2A_8") (pintype "bidirectional"))
      (node (ref "JP6") (pin "7") (pinfunction "7_7") (pintype "passive"))
    )
    (net (code "245") (name "Net-(IC6-B2B)") (class "Default")
      (node (ref "IC6") (pin "9") (pinfunction "B2B_9") (pintype "bidirectional"))
      (node (ref "JP6") (pin "8") (pinfunction "8_8") (pintype "passive"))
    )
    (net (code "246") (name "Net-(IC6-C1A)") (class "Default")
      (node (ref "IC6") (pin "11") (pinfunction "C1A_11") (pintype "bidirectional"))
      (node (ref "JP6") (pin "9") (pinfunction "9_9") (pintype "passive"))
    )
    (net (code "247") (name "Net-(IC6-C1B)") (class "Default")
      (node (ref "IC6") (pin "12") (pinfunction "C1B_12") (pintype "bidirectional"))
      (node (ref "JP6") (pin "10") (pinfunction "10_10") (pintype "passive"))
    )
    (net (code "248") (name "Net-(IC6-C2A)") (class "Default")
      (node (ref "IC6") (pin "13") (pinfunction "C2A_13") (pintype "bidirectional"))
      (node (ref "JP6") (pin "11") (pinfunction "11_11") (pintype "passive"))
    )
    (net (code "249") (name "Net-(IC6-C2B)") (class "Default")
      (node (ref "IC6") (pin "14") (pinfunction "C2B_14") (pintype "bidirectional"))
      (node (ref "JP6") (pin "12") (pinfunction "12_12") (pintype "passive"))
    )
    (net (code "250") (name "Net-(IC6-D1A)") (class "Default")
      (node (ref "IC6") (pin "16") (pinfunction "D1A_16") (pintype "bidirectional"))
      (node (ref "JP6") (pin "13") (pinfunction "13_13") (pintype "passive"))
    )
    (net (code "251") (name "Net-(IC6-D1B)") (class "Default")
      (node (ref "IC6") (pin "17") (pinfunction "D1B_17") (pintype "bidirectional"))
      (node (ref "JP6") (pin "14") (pinfunction "14_14") (pintype "passive"))
    )
    (net (code "252") (name "Net-(IC6-D2A)") (class "Default")
      (node (ref "IC6") (pin "18") (pinfunction "D2A_18") (pintype "bidirectional"))
      (node (ref "JP6") (pin "15") (pinfunction "15_15") (pintype "passive"))
    )
    (net (code "253") (name "Net-(IC6-D2B)") (class "Default")
      (node (ref "IC6") (pin "19") (pinfunction "D2B_19") (pintype "bidirectional"))
      (node (ref "JP6") (pin "16") (pinfunction "16_16") (pintype "passive"))
    )
    (net (code "254") (name "Net-(IC7-A1A)") (class "Default")
      (node (ref "IC7") (pin "1") (pinfunction "A1A_1") (pintype "bidirectional"))
      (node (ref "JP7") (pin "1") (pinfunction "1_1") (pintype "passive"))
    )
    (net (code "255") (name "Net-(IC7-A1B)") (class "Default")
      (node (ref "IC7") (pin "2") (pinfunction "A1B_2") (pintype "bidirectional"))
      (node (ref "JP7") (pin "2") (pinfunction "2_2") (pintype "passive"))
    )
    (net (code "256") (name "Net-(IC7-A2A)") (class "Default")
      (node (ref "IC7") (pin "3") (pinfunction "A2A_3") (pintype "bidirectional"))
      (node (ref "JP7") (pin "3") (pinfunction "3_3") (pintype "passive"))
    )
    (net (code "257") (name "Net-(IC7-A2B)") (class "Default")
      (node (ref "IC7") (pin "4") (pinfunction "A2B_4") (pintype "bidirectional"))
      (node (ref "JP7") (pin "4") (pinfunction "4_4") (pintype "passive"))
    )
    (net (code "258") (name "Net-(IC7-B1A)") (class "Default")
      (node (ref "IC7") (pin "6") (pinfunction "B1A_6") (pintype "bidirectional"))
      (node (ref "JP7") (pin "5") (pinfunction "5_5") (pintype "passive"))
    )
    (net (code "259") (name "Net-(IC7-B1B)") (class "Default")
      (node (ref "IC7") (pin "7") (pinfunction "B1B_7") (pintype "bidirectional"))
      (node (ref "JP7") (pin "6") (pinfunction "6_6") (pintype "passive"))
    )
    (net (code "260") (name "Net-(IC7-B2A)") (class "Default")
      (node (ref "IC7") (pin "8") (pinfunction "B2A_8") (pintype "bidirectional"))
      (node (ref "JP7") (pin "7") (pinfunction "7_7") (pintype "passive"))
    )
    (net (code "261") (name "Net-(IC7-B2B)") (class "Default")
      (node (ref "IC7") (pin "9") (pinfunction "B2B_9") (pintype "bidirectional"))
      (node (ref "JP7") (pin "8") (pinfunction "8_8") (pintype "passive"))
    )
    (net (code "262") (name "Net-(IC7-C1A)") (class "Default")
      (node (ref "IC7") (pin "11") (pinfunction "C1A_11") (pintype "bidirectional"))
      (node (ref "JP7") (pin "9") (pinfunction "9_9") (pintype "passive"))
    )
    (net (code "263") (name "Net-(IC7-C1B)") (class "Default")
      (node (ref "IC7") (pin "12") (pinfunction "C1B_12") (pintype "bidirectional"))
      (node (ref "JP7") (pin "10") (pinfunction "10_10") (pintype "passive"))
    )
    (net (code "264") (name "Net-(IC7-C2A)") (class "Default")
      (node (ref "IC7") (pin "13") (pinfunction "C2A_13") (pintype "bidirectional"))
      (node (ref "JP7") (pin "11") (pinfunction "11_11") (pintype "passive"))
    )
    (net (code "265") (name "Net-(IC7-C2B)") (class "Default")
      (node (ref "IC7") (pin "14") (pinfunction "C2B_14") (pintype "bidirectional"))
      (node (ref "JP7") (pin "12") (pinfunction "12_12") (pintype "passive"))
    )
    (net (code "266") (name "Net-(IC7-D1A)") (class "Default")
      (node (ref "IC7") (pin "16") (pinfunction "D1A_16") (pintype "bidirectional"))
      (node (ref "JP7") (pin "13") (pinfunction "13_13") (pintype "passive"))
    )
    (net (code "267") (name "Net-(IC7-D1B)") (class "Default")
      (node (ref "IC7") (pin "17") (pinfunction "D1B_17") (pintype "bidirectional"))
      (node (ref "JP7") (pin "14") (pinfunction "14_14") (pintype "passive"))
    )
    (net (code "268") (name "Net-(IC7-D2A)") (class "Default")
      (node (ref "IC7") (pin "18") (pinfunction "D2A_18") (pintype "bidirectional"))
      (node (ref "JP7") (pin "15") (pinfunction "15_15") (pintype "passive"))
    )
    (net (code "269") (name "Net-(IC7-D2B)") (class "Default")
      (node (ref "IC7") (pin "19") (pinfunction "D2B_19") (pintype "bidirectional"))
      (node (ref "JP7") (pin "16") (pinfunction "16_16") (pintype "passive"))
    )
    (net (code "270") (name "Net-(IC8-A1A)") (class "Default")
      (node (ref "IC8") (pin "1") (pinfunction "A1A_1") (pintype "bidirectional"))
      (node (ref "JP8") (pin "1") (pinfunction "1_1") (pintype "passive"))
    )
    (net (code "271") (name "Net-(IC8-A1B)") (class "Default")
      (node (ref "IC8") (pin "2") (pinfunction "A1B_2") (pintype "bidirectional"))
      (node (ref "JP8") (pin "2") (pinfunction "2_2") (pintype "passive"))
    )
    (net (code "272") (name "Net-(IC8-A2A)") (class "Default")
      (node (ref "IC8") (pin "3") (pinfunction "A2A_3") (pintype "bidirectional"))
      (node (ref "JP8") (pin "3") (pinfunction "3_3") (pintype "passive"))
    )
    (net (code "273") (name "Net-(IC8-A2B)") (class "Default")
      (node (ref "IC8") (pin "4") (pinfunction "A2B_4") (pintype "bidirectional"))
      (node (ref "JP8") (pin "4") (pinfunction "4_4") (pintype "passive"))
    )
    (net (code "274") (name "Net-(IC8-B1A)") (class "Default")
      (node (ref "IC8") (pin "6") (pinfunction "B1A_6") (pintype "bidirectional"))
      (node (ref "JP8") (pin "5") (pinfunction "5_5") (pintype "passive"))
    )
    (net (code "275") (name "Net-(IC8-B1B)") (class "Default")
      (node (ref "IC8") (pin "7") (pinfunction "B1B_7") (pintype "bidirectional"))
      (node (ref "JP8") (pin "6") (pinfunction "6_6") (pintype "passive"))
    )
    (net (code "276") (name "Net-(IC8-B2A)") (class "Default")
      (node (ref "IC8") (pin "8") (pinfunction "B2A_8") (pintype "bidirectional"))
      (node (ref "JP8") (pin "7") (pinfunction "7_7") (pintype "passive"))
    )
    (net (code "277") (name "Net-(IC8-B2B)") (class "Default")
      (node (ref "IC8") (pin "9") (pinfunction "B2B_9") (pintype "bidirectional"))
      (node (ref "JP8") (pin "8") (pinfunction "8_8") (pintype "passive"))
    )
    (net (code "278") (name "Net-(IC8-C1A)") (class "Default")
      (node (ref "IC8") (pin "11") (pinfunction "C1A_11") (pintype "bidirectional"))
      (node (ref "JP8") (pin "9") (pinfunction "9_9") (pintype "passive"))
    )
    (net (code "279") (name "Net-(IC8-C1B)") (class "Default")
      (node (ref "IC8") (pin "12") (pinfunction "C1B_12") (pintype "bidirectional"))
      (node (ref "JP8") (pin "10") (pinfunction "10_10") (pintype "passive"))
    )
    (net (code "280") (name "Net-(IC8-C2A)") (class "Default")
      (node (ref "IC8") (pin "13") (pinfunction "C2A_13") (pintype "bidirectional"))
      (node (ref "JP8") (pin "11") (pinfunction "11_11") (pintype "passive"))
    )
    (net (code "281") (name "Net-(IC8-C2B)") (class "Default")
      (node (ref "IC8") (pin "14") (pinfunction "C2B_14") (pintype "bidirectional"))
      (node (ref "JP8") (pin "12") (pinfunction "12_12") (pintype "passive"))
    )
    (net (code "282") (name "Net-(IC8-D1A)") (class "Default")
      (node (ref "IC8") (pin "16") (pinfunction "D1A_16") (pintype "bidirectional"))
      (node (ref "JP8") (pin "13") (pinfunction "13_13") (pintype "passive"))
    )
    (net (code "283") (name "Net-(IC8-D1B)") (class "Default")
      (node (ref "IC8") (pin "17") (pinfunction "D1B_17") (pintype "bidirectional"))
      (node (ref "JP8") (pin "14") (pinfunction "14_14") (pintype "passive"))
    )
    (net (code "284") (name "Net-(IC8-D2A)") (class "Default")
      (node (ref "IC8") (pin "18") (pinfunction "D2A_18") (pintype "bidirectional"))
      (node (ref "JP8") (pin "15") (pinfunction "15_15") (pintype "passive"))
    )
    (net (code "285") (name "Net-(IC8-D2B)") (class "Default")
      (node (ref "IC8") (pin "19") (pinfunction "D2B_19") (pintype "bidirectional"))
      (node (ref "JP8") (pin "16") (pinfunction "16_16") (pintype "passive"))
    )
    (net (code "286") (name "Net-(LEDPOW-PadC)") (class "Default")
      (node (ref "LEDPOW") (pin "C") (pinfunction "C_C") (pintype "passive"))
      (node (ref "RLEDPOW") (pin "1") (pinfunction "1_1") (pintype "passive"))
    )
    (net (code "287") (name "Net-(LED_OE-PadC)") (class "Default")
      (node (ref "LED_OE") (pin "C") (pinfunction "C_C") (pintype "passive"))
      (node (ref "R8") (pin "1") (pinfunction "1_1") (pintype "passive"))
    )
    (net (code "288") (name "Net-(X1A-S)") (class "Default")
      (node (ref "J11") (pin "8") (pinfunction "8_8") (pintype "passive"))
      (node (ref "X1") (pin "1") (pinfunction "S_1") (pintype "passive"))
    )
    (net (code "289") (name "Net-(X1B-S)") (class "Default")
      (node (ref "J9") (pin "4") (pinfunction "4_4") (pintype "passive"))
      (node (ref "X1") (pin "10") (pinfunction "S_10") (pintype "passive"))
    )
    (net (code "290") (name "Net-(X1C-S)") (class "Default")
      (node (ref "J11") (pin "3") (pinfunction "3_3") (pintype "passive"))
      (node (ref "X1") (pin "11") (pinfunction "S_11") (pintype "passive"))
    )
    (net (code "291") (name "Net-(X1D-S)") (class "Default")
      (node (ref "J9") (pin "3") (pinfunction "3_3") (pintype "passive"))
      (node (ref "X1") (pin "12") (pinfunction "S_12") (pintype "passive"))
    )
    (net (code "292") (name "Net-(X1E-S)") (class "Default")
      (node (ref "J11") (pin "2") (pinfunction "2_2") (pintype "passive"))
      (node (ref "X1") (pin "13") (pinfunction "S_13") (pintype "passive"))
    )
    (net (code "293") (name "Net-(X1F-S)") (class "Default")
      (node (ref "J9") (pin "2") (pinfunction "2_2") (pintype "passive"))
      (node (ref "X1") (pin "14") (pinfunction "S_14") (pintype "passive"))
    )
    (net (code "294") (name "Net-(X1G-S)") (class "Default")
      (node (ref "J11") (pin "1") (pinfunction "1_1") (pintype "passive"))
      (node (ref "X1") (pin "15") (pinfunction "S_15") (pintype "passive"))
    )
    (net (code "295") (name "Net-(X1H-S)") (class "Default")
      (node (ref "J9") (pin "1") (pinfunction "1_1") (pintype "passive"))
      (node (ref "X1") (pin "16") (pinfunction "S_16") (pintype "passive"))
    )
    (net (code "296") (name "Net-(X1J-S)") (class "Default")
      (node (ref "J11") (pin "7") (pinfunction "7_7") (pintype "passive"))
      (node (ref "X1") (pin "3") (pinfunction "S_3") (pintype "passive"))
    )
    (net (code "297") (name "Net-(X1L-S)") (class "Default")
      (node (ref "J11") (pin "6") (pinfunction "6_6") (pintype "passive"))
      (node (ref "X1") (pin "5") (pinfunction "S_5") (pintype "passive"))
    )
    (net (code "298") (name "Net-(X1N-S)") (class "Default")
      (node (ref "J11") (pin "5") (pinfunction "5_5") (pintype "passive"))
      (node (ref "X1") (pin "7") (pinfunction "S_7") (pintype "passive"))
    )
    (net (code "299") (name "Net-(X1P-S)") (class "Default")
      (node (ref "J11") (pin "4") (pinfunction "4_4") (pintype "passive"))
      (node (ref "X1") (pin "9") (pinfunction "S_9") (pintype "passive"))
    )
    (net (code "300") (name "Net-(X2A-S)") (class "Default")
      (node (ref "J13") (pin "8") (pinfunction "8_8") (pintype "passive"))
      (node (ref "X2") (pin "1") (pinfunction "S_1") (pintype "passive"))
    )
    (net (code "301") (name "Net-(X2B-S)") (class "Default")
      (node (ref "J10") (pin "4") (pinfunction "4_4") (pintype "passive"))
      (node (ref "X2") (pin "10") (pinfunction "S_10") (pintype "passive"))
    )
    (net (code "302") (name "Net-(X2C-S)") (class "Default")
      (node (ref "J13") (pin "3") (pinfunction "3_3") (pintype "passive"))
      (node (ref "X2") (pin "11") (pinfunction "S_11") (pintype "passive"))
    )
    (net (code "303") (name "Net-(X2D-S)") (class "Default")
      (node (ref "J10") (pin "3") (pinfunction "3_3") (pintype "passive"))
      (node (ref "X2") (pin "12") (pinfunction "S_12") (pintype "passive"))
    )
    (net (code "304") (name "Net-(X2E-S)") (class "Default")
      (node (ref "J13") (pin "2") (pinfunction "2_2") (pintype "passive"))
      (node (ref "X2") (pin "13") (pinfunction "S_13") (pintype "passive"))
    )
    (net (code "305") (name "Net-(X2F-S)") (class "Default")
      (node (ref "J10") (pin "2") (pinfunction "2_2") (pintype "passive"))
      (node (ref "X2") (pin "14") (pinfunction "S_14") (pintype "passive"))
    )
    (net (code "306") (name "Net-(X2G-S)") (class "Default")
      (node (ref "J13") (pin "1") (pinfunction "1_1") (pintype "passive"))
      (node (ref "X2") (pin "15") (pinfunction "S_15") (pintype "passive"))
    )
    (net (code "307") (name "Net-(X2H-S)") (class "Default")
      (node (ref "J10") (pin "1") (pinfunction "1_1") (pintype "passive"))
      (node (ref "X2") (pin "16") (pinfunction "S_16") (pintype "passive"))
    )
    (net (code "308") (name "Net-(X2I-S)") (class "Default")
      (node (ref "J10") (pin "8") (pinfunction "8_8") (pintype "passive"))
      (node (ref "X2") (pin "2") (pinfunction "S_2") (pintype "passive"))
    )
    (net (code "309") (name "Net-(X2J-S)") (class "Default")
      (node (ref "J13") (pin "7") (pinfunction "7_7") (pintype "passive"))
      (node (ref "X2") (pin "3") (pinfunction "S_3") (pintype "passive"))
    )
    (net (code "310") (name "Net-(X2K-S)") (class "Default")
      (node (ref "J10") (pin "7") (pinfunction "7_7") (pintype "passive"))
      (node (ref "X2") (pin "4") (pinfunction "S_4") (pintype "passive"))
    )
    (net (code "311") (name "Net-(X2L-S)") (class "Default")
      (node (ref "J13") (pin "6") (pinfunction "6_6") (pintype "passive"))
      (node (ref "X2") (pin "5") (pinfunction "S_5") (pintype "passive"))
    )
    (net (code "312") (name "Net-(X2M-S)") (class "Default")
      (node (ref "J10") (pin "6") (pinfunction "6_6") (pintype "passive"))
      (node (ref "X2") (pin "6") (pinfunction "S_6") (pintype "passive"))
    )
    (net (code "313") (name "Net-(X2N-S)") (class "Default")
      (node (ref "J13") (pin "5") (pinfunction "5_5") (pintype "passive"))
      (node (ref "X2") (pin "7") (pinfunction "S_7") (pintype "passive"))
    )
    (net (code "314") (name "Net-(X2O-S)") (class "Default")
      (node (ref "J10") (pin "5") (pinfunction "5_5") (pintype "passive"))
      (node (ref "X2") (pin "8") (pinfunction "S_8") (pintype "passive"))
    )
    (net (code "315") (name "Net-(X2P-S)") (class "Default")
      (node (ref "J13") (pin "4") (pinfunction "4_4") (pintype "passive"))
      (node (ref "X2") (pin "9") (pinfunction "S_9") (pintype "passive"))
    )
    (net (code "316") (name "unconnected-(J19A-MSV-Pad1-A1)") (class "Default")
      (node (ref "J19") (pin "1-A1") (pinfunction "MSV_1-A1") (pintype "passive"))
    )
    (net (code "317") (name "unconnected-(J19AA-MS-Pad1-A4)") (class "Default")
      (node (ref "J19") (pin "1-A4") (pinfunction "MS_1-A4") (pintype "passive"))
    )
    (net (code "318") (name "unconnected-(J19AB-MS-Pad1-A5)") (class "Default")
      (node (ref "J19") (pin "1-A5") (pinfunction "MS_1-A5") (pintype "passive"))
    )
    (net (code "319") (name "unconnected-(J19AC-MS-Pad1-A6)") (class "Default")
      (node (ref "J19") (pin "1-A6") (pinfunction "MS_1-A6") (pintype "passive"))
    )
    (net (code "320") (name "unconnected-(J19AD-MS-Pad1-A7)") (class "Default")
      (node (ref "J19") (pin "1-A7") (pinfunction "MS_1-A7") (pintype "passive"))
    )
    (net (code "321") (name "unconnected-(J19AE-MS-Pad1-A8)") (class "Default")
      (node (ref "J19") (pin "1-A8") (pinfunction "MS_1-A8") (pintype "passive"))
    )
    (net (code "322") (name "unconnected-(J19AG-MSV-Pad1-C1)") (class "Default")
      (node (ref "J19") (pin "1-C1") (pinfunction "MSV_1-C1") (pintype "passive"))
    )
    (net (code "323") (name "unconnected-(J19AH-MS-Pad1-C10)") (class "Default")
      (node (ref "J19") (pin "1-C10") (pinfunction "MS_1-C10") (pintype "passive"))
    )
    (net (code "324") (name "unconnected-(J19AI-MS-Pad1-C11)") (class "Default")
      (node (ref "J19") (pin "1-C11") (pinfunction "MS_1-C11") (pintype "passive"))
    )
    (net (code "325") (name "unconnected-(J19AJ-MS-Pad1-C12)") (class "Default")
      (node (ref "J19") (pin "1-C12") (pinfunction "MS_1-C12") (pintype "passive"))
    )
    (net (code "326") (name "unconnected-(J19AK-MS-Pad1-C13)") (class "Default")
      (node (ref "J19") (pin "1-C13") (pinfunction "MS_1-C13") (pintype "passive"))
    )
    (net (code "327") (name "unconnected-(J19AL-MS-Pad1-C14)") (class "Default")
      (node (ref "J19") (pin "1-C14") (pinfunction "MS_1-C14") (pintype "passive"))
    )
    (net (code "328") (name "unconnected-(J19AM-MS-Pad1-C15)") (class "Default")
      (node (ref "J19") (pin "1-C15") (pinfunction "MS_1-C15") (pintype "passive"))
    )
    (net (code "329") (name "unconnected-(J19AN-MS-Pad1-C16)") (class "Default")
      (node (ref "J19") (pin "1-C16") (pinfunction "MS_1-C16") (pintype "passive"))
    )
    (net (code "330") (name "unconnected-(J19AO-MS-Pad1-C17)") (class "Default")
      (node (ref "J19") (pin "1-C17") (pinfunction "MS_1-C17") (pintype "passive"))
    )
    (net (code "331") (name "unconnected-(J19AP-MS-Pad1-C18)") (class "Default")
      (node (ref "J19") (pin "1-C18") (pinfunction "MS_1-C18") (pintype "passive"))
    )
    (net (code "332") (name "unconnected-(J19AQ-MS-Pad1-C19)") (class "Default")
      (node (ref "J19") (pin "1-C19") (pinfunction "MS_1-C19") (pintype "passive"))
    )
    (net (code "333") (name "unconnected-(J19AR-MS-Pad1-C2)") (class "Default")
      (node (ref "J19") (pin "1-C2") (pinfunction "MS_1-C2") (pintype "passive"))
    )
    (net (code "334") (name "unconnected-(J19AS-MS-Pad1-C20)") (class "Default")
      (node (ref "J19") (pin "1-C20") (pinfunction "MS_1-C20") (pintype "passive"))
    )
    (net (code "335") (name "unconnected-(J19AT-MS-Pad1-C21)") (class "Default")
      (node (ref "J19") (pin "1-C21") (pinfunction "MS_1-C21") (pintype "passive"))
    )
    (net (code "336") (name "unconnected-(J19AU-MS-Pad1-C22)") (class "Default")
      (node (ref "J19") (pin "1-C22") (pinfunction "MS_1-C22") (pintype "passive"))
    )
    (net (code "337") (name "unconnected-(J19AV-MS-Pad1-C23)") (class "Default")
      (node (ref "J19") (pin "1-C23") (pinfunction "MS_1-C23") (pintype "passive"))
    )
    (net (code "338") (name "unconnected-(J19AW-MS-Pad1-C24)") (class "Default")
      (node (ref "J19") (pin "1-C24") (pinfunction "MS_1-C24") (pintype "passive"))
    )
    (net (code "339") (name "unconnected-(J19AX-MS-Pad1-C25)") (class "Default")
      (node (ref "J19") (pin "1-C25") (pinfunction "MS_1-C25") (pintype "passive"))
    )
    (net (code "340") (name "unconnected-(J19AY-MS-Pad1-C26)") (class "Default")
      (node (ref "J19") (pin "1-C26") (pinfunction "MS_1-C26") (pintype "passive"))
    )
    (net (code "341") (name "unconnected-(J19AZ-MS-Pad1-C27)") (class "Default")
      (node (ref "J19") (pin "1-C27") (pinfunction "MS_1-C27") (pintype "passive"))
    )
    (net (code "342") (name "unconnected-(J19B-MS-Pad1-A10)") (class "Default")
      (node (ref "J19") (pin "1-A10") (pinfunction "MS_1-A10") (pintype "passive"))
    )
    (net (code "343") (name "unconnected-(J19BA-MS-Pad1-C28)") (class "Default")
      (node (ref "J19") (pin "1-C28") (pinfunction "MS_1-C28") (pintype "passive"))
    )
    (net (code "344") (name "unconnected-(J19BB-MS-Pad1-C29)") (class "Default")
      (node (ref "J19") (pin "1-C29") (pinfunction "MS_1-C29") (pintype "passive"))
    )
    (net (code "345") (name "unconnected-(J19BC-MS-Pad1-C3)") (class "Default")
      (node (ref "J19") (pin "1-C3") (pinfunction "MS_1-C3") (pintype "passive"))
    )
    (net (code "346") (name "unconnected-(J19BD-MS-Pad1-C30)") (class "Default")
      (node (ref "J19") (pin "1-C30") (pinfunction "MS_1-C30") (pintype "passive"))
    )
    (net (code "347") (name "unconnected-(J19BG-MS-Pad1-C4)") (class "Default")
      (node (ref "J19") (pin "1-C4") (pinfunction "MS_1-C4") (pintype "passive"))
    )
    (net (code "348") (name "unconnected-(J19BH-MS-Pad1-C5)") (class "Default")
      (node (ref "J19") (pin "1-C5") (pinfunction "MS_1-C5") (pintype "passive"))
    )
    (net (code "349") (name "unconnected-(J19BI-MS-Pad1-C6)") (class "Default")
      (node (ref "J19") (pin "1-C6") (pinfunction "MS_1-C6") (pintype "passive"))
    )
    (net (code "350") (name "unconnected-(J19BJ-MS-Pad1-C7)") (class "Default")
      (node (ref "J19") (pin "1-C7") (pinfunction "MS_1-C7") (pintype "passive"))
    )
    (net (code "351") (name "unconnected-(J19BK-MS-Pad1-C8)") (class "Default")
      (node (ref "J19") (pin "1-C8") (pinfunction "MS_1-C8") (pintype "passive"))
    )
    (net (code "352") (name "unconnected-(J19BM-MSV-Pad2-A1)") (class "Default")
      (node (ref "J19") (pin "2-A1") (pinfunction "MSV_2-A1") (pintype "passive"))
    )
    (net (code "353") (name "unconnected-(J19BN-MS-Pad2-A10)") (class "Default")
      (node (ref "J19") (pin "2-A10") (pinfunction "MS_2-A10") (pintype "passive"))
    )
    (net (code "354") (name "unconnected-(J19BO-MS-Pad2-A11)") (class "Default")
      (node (ref "J19") (pin "2-A11") (pinfunction "MS_2-A11") (pintype "passive"))
    )
    (net (code "355") (name "unconnected-(J19BP-MS-Pad2-A12)") (class "Default")
      (node (ref "J19") (pin "2-A12") (pinfunction "MS_2-A12") (pintype "passive"))
    )
    (net (code "356") (name "unconnected-(J19BQ-MS-Pad2-A13)") (class "Default")
      (node (ref "J19") (pin "2-A13") (pinfunction "MS_2-A13") (pintype "passive"))
    )
    (net (code "357") (name "unconnected-(J19BR-MS-Pad2-A14)") (class "Default")
      (node (ref "J19") (pin "2-A14") (pinfunction "MS_2-A14") (pintype "passive"))
    )
    (net (code "358") (name "unconnected-(J19BS-MS-Pad2-A15)") (class "Default")
      (node (ref "J19") (pin "2-A15") (pinfunction "MS_2-A15") (pintype "passive"))
    )
    (net (code "359") (name "unconnected-(J19BT-MS-Pad2-A16)") (class "Default")
      (node (ref "J19") (pin "2-A16") (pinfunction "MS_2-A16") (pintype "passive"))
    )
    (net (code "360") (name "unconnected-(J19BU-MS-Pad2-A17)") (class "Default")
      (node (ref "J19") (pin "2-A17") (pinfunction "MS_2-A17") (pintype "passive"))
    )
    (net (code "361") (name "unconnected-(J19BV-MS-Pad2-A18)") (class "Default")
      (node (ref "J19") (pin "2-A18") (pinfunction "MS_2-A18") (pintype "passive"))
    )
    (net (code "362") (name "unconnected-(J19BW-MS-Pad2-A19)") (class "Default")
      (node (ref "J19") (pin "2-A19") (pinfunction "MS_2-A19") (pintype "passive"))
    )
    (net (code "363") (name "unconnected-(J19BX-MS-Pad2-A2)") (class "Default")
      (node (ref "J19") (pin "2-A2") (pinfunction "MS_2-A2") (pintype "passive"))
    )
    (net (code "364") (name "unconnected-(J19BY-MS-Pad2-A20)") (class "Default")
      (node (ref "J19") (pin "2-A20") (pinfunction "MS_2-A20") (pintype "passive"))
    )
    (net (code "365") (name "unconnected-(J19BZ-MS-Pad2-A21)") (class "Default")
      (node (ref "J19") (pin "2-A21") (pinfunction "MS_2-A21") (pintype "passive"))
    )
    (net (code "366") (name "unconnected-(J19C-MS-Pad1-A11)") (class "Default")
      (node (ref "J19") (pin "1-A11") (pinfunction "MS_1-A11") (pintype "passive"))
    )
    (net (code "367") (name "unconnected-(J19CA-MS-Pad2-A22)") (class "Default")
      (node (ref "J19") (pin "2-A22") (pinfunction "MS_2-A22") (pintype "passive"))
    )
    (net (code "368") (name "unconnected-(J19CB-MS-Pad2-A23)") (class "Default")
      (node (ref "J19") (pin "2-A23") (pinfunction "MS_2-A23") (pintype "passive"))
    )
    (net (code "369") (name "unconnected-(J19CC-MS-Pad2-A24)") (class "Default")
      (node (ref "J19") (pin "2-A24") (pinfunction "MS_2-A24") (pintype "passive"))
    )
    (net (code "370") (name "unconnected-(J19CD-MS-Pad2-A25)") (class "Default")
      (node (ref "J19") (pin "2-A25") (pinfunction "MS_2-A25") (pintype "passive"))
    )
    (net (code "371") (name "unconnected-(J19CE-MS-Pad2-A26)") (class "Default")
      (node (ref "J19") (pin "2-A26") (pinfunction "MS_2-A26") (pintype "passive"))
    )
    (net (code "372") (name "unconnected-(J19CF-MS-Pad2-A27)") (class "Default")
      (node (ref "J19") (pin "2-A27") (pinfunction "MS_2-A27") (pintype "passive"))
    )
    (net (code "373") (name "unconnected-(J19CG-MS-Pad2-A28)") (class "Default")
      (node (ref "J19") (pin "2-A28") (pinfunction "MS_2-A28") (pintype "passive"))
    )
    (net (code "374") (name "unconnected-(J19CH-MS-Pad2-A29)") (class "Default")
      (node (ref "J19") (pin "2-A29") (pinfunction "MS_2-A29") (pintype "passive"))
    )
    (net (code "375") (name "unconnected-(J19CI-MS-Pad2-A3)") (class "Default")
      (node (ref "J19") (pin "2-A3") (pinfunction "MS_2-A3") (pintype "passive"))
    )
    (net (code "376") (name "unconnected-(J19CJ-MS-Pad2-A30)") (class "Default")
      (node (ref "J19") (pin "2-A30") (pinfunction "MS_2-A30") (pintype "passive"))
    )
    (net (code "377") (name "unconnected-(J19CK-MS-Pad2-A31)") (class "Default")
      (node (ref "J19") (pin "2-A31") (pinfunction "MS_2-A31") (pintype "passive"))
    )
    (net (code "378") (name "unconnected-(J19CL-MS-Pad2-A32)") (class "Default")
      (node (ref "J19") (pin "2-A32") (pinfunction "MS_2-A32") (pintype "passive"))
    )
    (net (code "379") (name "unconnected-(J19CM-MS-Pad2-A4)") (class "Default")
      (node (ref "J19") (pin "2-A4") (pinfunction "MS_2-A4") (pintype "passive"))
    )
    (net (code "380") (name "unconnected-(J19CN-MS-Pad2-A5)") (class "Default")
      (node (ref "J19") (pin "2-A5") (pinfunction "MS_2-A5") (pintype "passive"))
    )
    (net (code "381") (name "unconnected-(J19CO-MS-Pad2-A6)") (class "Default")
      (node (ref "J19") (pin "2-A6") (pinfunction "MS_2-A6") (pintype "passive"))
    )
    (net (code "382") (name "unconnected-(J19CP-MS-Pad2-A7)") (class "Default")
      (node (ref "J19") (pin "2-A7") (pinfunction "MS_2-A7") (pintype "passive"))
    )
    (net (code "383") (name "unconnected-(J19CQ-MS-Pad2-A8)") (class "Default")
      (node (ref "J19") (pin "2-A8") (pinfunction "MS_2-A8") (pintype "passive"))
    )
    (net (code "384") (name "unconnected-(J19CR-MS-Pad2-A9)") (class "Default")
      (node (ref "J19") (pin "2-A9") (pinfunction "MS_2-A9") (pintype "passive"))
    )
    (net (code "385") (name "unconnected-(J19CS-MSV-Pad2-C1)") (class "Default")
      (node (ref "J19") (pin "2-C1") (pinfunction "MSV_2-C1") (pintype "passive"))
    )
    (net (code "386") (name "unconnected-(J19CT-MS-Pad2-C10)") (class "Default")
      (node (ref "J19") (pin "2-C10") (pinfunction "MS_2-C10") (pintype "passive"))
    )
    (net (code "387") (name "unconnected-(J19CU-MS-Pad2-C11)") (class "Default")
      (node (ref "J19") (pin "2-C11") (pinfunction "MS_2-C11") (pintype "passive"))
    )
    (net (code "388") (name "unconnected-(J19CV-MS-Pad2-C12)") (class "Default")
      (node (ref "J19") (pin "2-C12") (pinfunction "MS_2-C12") (pintype "passive"))
    )
    (net (code "389") (name "unconnected-(J19CW-MS-Pad2-C13)") (class "Default")
      (node (ref "J19") (pin "2-C13") (pinfunction "MS_2-C13") (pintype "passive"))
    )
    (net (code "390") (name "unconnected-(J19CX-MS-Pad2-C14)") (class "Default")
      (node (ref "J19") (pin "2-C14") (pinfunction "MS_2-C14") (pintype "passive"))
    )
    (net (code "391") (name "unconnected-(J19CY-MS-Pad2-C15)") (class "Default")
      (node (ref "J19") (pin "2-C15") (pinfunction "MS_2-C15") (pintype "passive"))
    )
    (net (code "392") (name "unconnected-(J19CZ-MS-Pad2-C16)") (class "Default")
      (node (ref "J19") (pin "2-C16") (pinfunction "MS_2-C16") (pintype "passive"))
    )
    (net (code "393") (name "unconnected-(J19D-MS-Pad1-A12)") (class "Default")
      (node (ref "J19") (pin "1-A12") (pinfunction "MS_1-A12") (pintype "passive"))
    )
    (net (code "394") (name "unconnected-(J19DA-MS-Pad2-C17)") (class "Default")
      (node (ref "J19") (pin "2-C17") (pinfunction "MS_2-C17") (pintype "passive"))
    )
    (net (code "395") (name "unconnected-(J19DB-MS-Pad2-C18)") (class "Default")
      (node (ref "J19") (pin "2-C18") (pinfunction "MS_2-C18") (pintype "passive"))
    )
    (net (code "396") (name "unconnected-(J19DC-MS-Pad2-C19)") (class "Default")
      (node (ref "J19") (pin "2-C19") (pinfunction "MS_2-C19") (pintype "passive"))
    )
    (net (code "397") (name "unconnected-(J19DD-MS-Pad2-C2)") (class "Default")
      (node (ref "J19") (pin "2-C2") (pinfunction "MS_2-C2") (pintype "passive"))
    )
    (net (code "398") (name "unconnected-(J19DE-MS-Pad2-C20)") (class "Default")
      (node (ref "J19") (pin "2-C20") (pinfunction "MS_2-C20") (pintype "passive"))
    )
    (net (code "399") (name "unconnected-(J19DF-MS-Pad2-C21)") (class "Default")
      (node (ref "J19") (pin "2-C21") (pinfunction "MS_2-C21") (pintype "passive"))
    )
    (net (code "400") (name "unconnected-(J19DG-MS-Pad2-C22)") (class "Default")
      (node (ref "J19") (pin "2-C22") (pinfunction "MS_2-C22") (pintype "passive"))
    )
    (net (code "401") (name "unconnected-(J19DH-MS-Pad2-C23)") (class "Default")
      (node (ref "J19") (pin "2-C23") (pinfunction "MS_2-C23") (pintype "passive"))
    )
    (net (code "402") (name "unconnected-(J19DI-MS-Pad2-C24)") (class "Default")
      (node (ref "J19") (pin "2-C24") (pinfunction "MS_2-C24") (pintype "passive"))
    )
    (net (code "403") (name "unconnected-(J19DJ-MS-Pad2-C25)") (class "Default")
      (node (ref "J19") (pin "2-C25") (pinfunction "MS_2-C25") (pintype "passive"))
    )
    (net (code "404") (name "unconnected-(J19DK-MS-Pad2-C26)") (class "Default")
      (node (ref "J19") (pin "2-C26") (pinfunction "MS_2-C26") (pintype "passive"))
    )
    (net (code "405") (name "unconnected-(J19DL-MS-Pad2-C27)") (class "Default")
      (node (ref "J19") (pin "2-C27") (pinfunction "MS_2-C27") (pintype "passive"))
    )
    (net (code "406") (name "unconnected-(J19DM-MS-Pad2-C28)") (class "Default")
      (node (ref "J19") (pin "2-C28") (pinfunction "MS_2-C28") (pintype "passive"))
    )
    (net (code "407") (name "unconnected-(J19DN-MS-Pad2-C29)") (class "Default")
      (node (ref "J19") (pin "2-C29") (pinfunction "MS_2-C29") (pintype "passive"))
    )
    (net (code "408") (name "unconnected-(J19DO-MS-Pad2-C3)") (class "Default")
      (node (ref "J19") (pin "2-C3") (pinfunction "MS_2-C3") (pintype "passive"))
    )
    (net (code "409") (name "unconnected-(J19DP-MS-Pad2-C30)") (class "Default")
      (node (ref "J19") (pin "2-C30") (pinfunction "MS_2-C30") (pintype "passive"))
    )
    (net (code "410") (name "unconnected-(J19DQ-MS-Pad2-C31)") (class "Default")
      (node (ref "J19") (pin "2-C31") (pinfunction "MS_2-C31") (pintype "passive"))
    )
    (net (code "411") (name "unconnected-(J19DR-MS-Pad2-C32)") (class "Default")
      (node (ref "J19") (pin "2-C32") (pinfunction "MS_2-C32") (pintype "passive"))
    )
    (net (code "412") (name "unconnected-(J19DS-MS-Pad2-C4)") (class "Default")
      (node (ref "J19") (pin "2-C4") (pinfunction "MS_2-C4") (pintype "passive"))
    )
    (net (code "413") (name "unconnected-(J19DT-MS-Pad2-C5)") (class "Default")
      (node (ref "J19") (pin "2-C5") (pinfunction "MS_2-C5") (pintype "passive"))
    )
    (net (code "414") (name "unconnected-(J19DU-MS-Pad2-C6)") (class "Default")
      (node (ref "J19") (pin "2-C6") (pinfunction "MS_2-C6") (pintype "passive"))
    )
    (net (code "415") (name "unconnected-(J19DV-MS-Pad2-C7)") (class "Default")
      (node (ref "J19") (pin "2-C7") (pinfunction "MS_2-C7") (pintype "passive"))
    )
    (net (code "416") (name "unconnected-(J19DW-MS-Pad2-C8)") (class "Default")
      (node (ref "J19") (pin "2-C8") (pinfunction "MS_2-C8") (pintype "passive"))
    )
    (net (code "417") (name "unconnected-(J19DX-MS-Pad2-C9)") (class "Default")
      (node (ref "J19") (pin "2-C9") (pinfunction "MS_2-C9") (pintype "passive"))
    )
    (net (code "418") (name "unconnected-(J19E-MS-Pad1-A13)") (class "Default")
      (node (ref "J19") (pin "1-A13") (pinfunction "MS_1-A13") (pintype "passive"))
    )
    (net (code "419") (name "unconnected-(J19F-MS-Pad1-A14)") (class "Default")
      (node (ref "J19") (pin "1-A14") (pinfunction "MS_1-A14") (pintype "passive"))
    )
    (net (code "420") (name "unconnected-(J19G-MS-Pad1-A15)") (class "Default")
      (node (ref "J19") (pin "1-A15") (pinfunction "MS_1-A15") (pintype "passive"))
    )
    (net (code "421") (name "unconnected-(J19H-MS-Pad1-A16)") (class "Default")
      (node (ref "J19") (pin "1-A16") (pinfunction "MS_1-A16") (pintype "passive"))
    )
    (net (code "422") (name "unconnected-(J19I-MS-Pad1-A17)") (class "Default")
      (node (ref "J19") (pin "1-A17") (pinfunction "MS_1-A17") (pintype "passive"))
    )
    (net (code "423") (name "unconnected-(J19J-MS-Pad1-A18)") (class "Default")
      (node (ref "J19") (pin "1-A18") (pinfunction "MS_1-A18") (pintype "passive"))
    )
    (net (code "424") (name "unconnected-(J19K-MS-Pad1-A19)") (class "Default")
      (node (ref "J19") (pin "1-A19") (pinfunction "MS_1-A19") (pintype "passive"))
    )
    (net (code "425") (name "unconnected-(J19L-MS-Pad1-A2)") (class "Default")
      (node (ref "J19") (pin "1-A2") (pinfunction "MS_1-A2") (pintype "passive"))
    )
    (net (code "426") (name "unconnected-(J19M-MS-Pad1-A20)") (class "Default")
      (node (ref "J19") (pin "1-A20") (pinfunction "MS_1-A20") (pintype "passive"))
    )
    (net (code "427") (name "unconnected-(J19N-MS-Pad1-A21)") (class "Default")
      (node (ref "J19") (pin "1-A21") (pinfunction "MS_1-A21") (pintype "passive"))
    )
    (net (code "428") (name "unconnected-(J19O-MS-Pad1-A22)") (class "Default")
      (node (ref "J19") (pin "1-A22") (pinfunction "MS_1-A22") (pintype "passive"))
    )
    (net (code "429") (name "unconnected-(J19P-MS-Pad1-A23)") (class "Default")
      (node (ref "J19") (pin "1-A23") (pinfunction "MS_1-A23") (pintype "passive"))
    )
    (net (code "430") (name "unconnected-(J19Q-MS-Pad1-A24)") (class "Default")
      (node (ref "J19") (pin "1-A24") (pinfunction "MS_1-A24") (pintype "passive"))
    )
    (net (code "431") (name "unconnected-(J19R-MS-Pad1-A25)") (class "Default")
      (node (ref "J19") (pin "1-A25") (pinfunction "MS_1-A25") (pintype "passive"))
    )
    (net (code "432") (name "unconnected-(J19S-MS-Pad1-A26)") (class "Default")
      (node (ref "J19") (pin "1-A26") (pinfunction "MS_1-A26") (pintype "passive"))
    )
    (net (code "433") (name "unconnected-(J19T-MS-Pad1-A27)") (class "Default")
      (node (ref "J19") (pin "1-A27") (pinfunction "MS_1-A27") (pintype "passive"))
    )
    (net (code "434") (name "unconnected-(J19U-MS-Pad1-A28)") (class "Default")
      (node (ref "J19") (pin "1-A28") (pinfunction "MS_1-A28") (pintype "passive"))
    )
    (net (code "435") (name "unconnected-(J19V-MS-Pad1-A29)") (class "Default")
      (node (ref "J19") (pin "1-A29") (pinfunction "MS_1-A29") (pintype "passive"))
    )
    (net (code "436") (name "unconnected-(J19W-MS-Pad1-A3)") (class "Default")
      (node (ref "J19") (pin "1-A3") (pinfunction "MS_1-A3") (pintype "passive"))
    )
    (net (code "437") (name "unconnected-(J19X-MS-Pad1-A30)") (class "Default")
      (node (ref "J19") (pin "1-A30") (pinfunction "MS_1-A30") (pintype "passive"))
    )
  )
)
